# Open-Source_Control_V3_R0.net
KiCad netlist of a schematic drawn in EAGLE
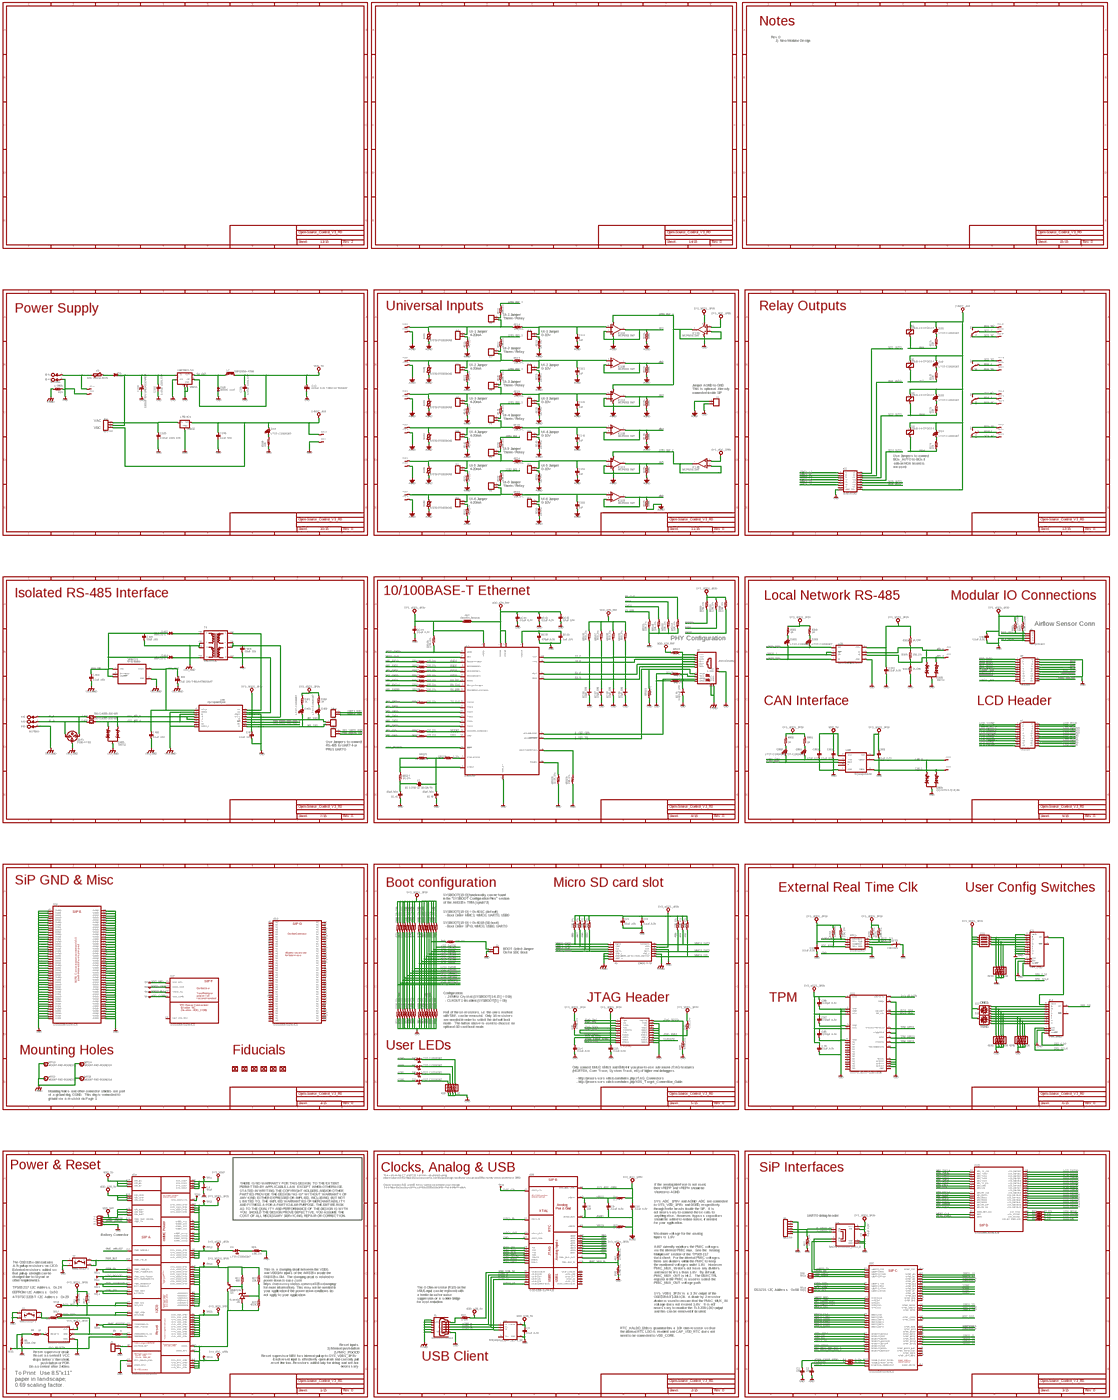
[diagram p0: schematic, sheet 1, overview]
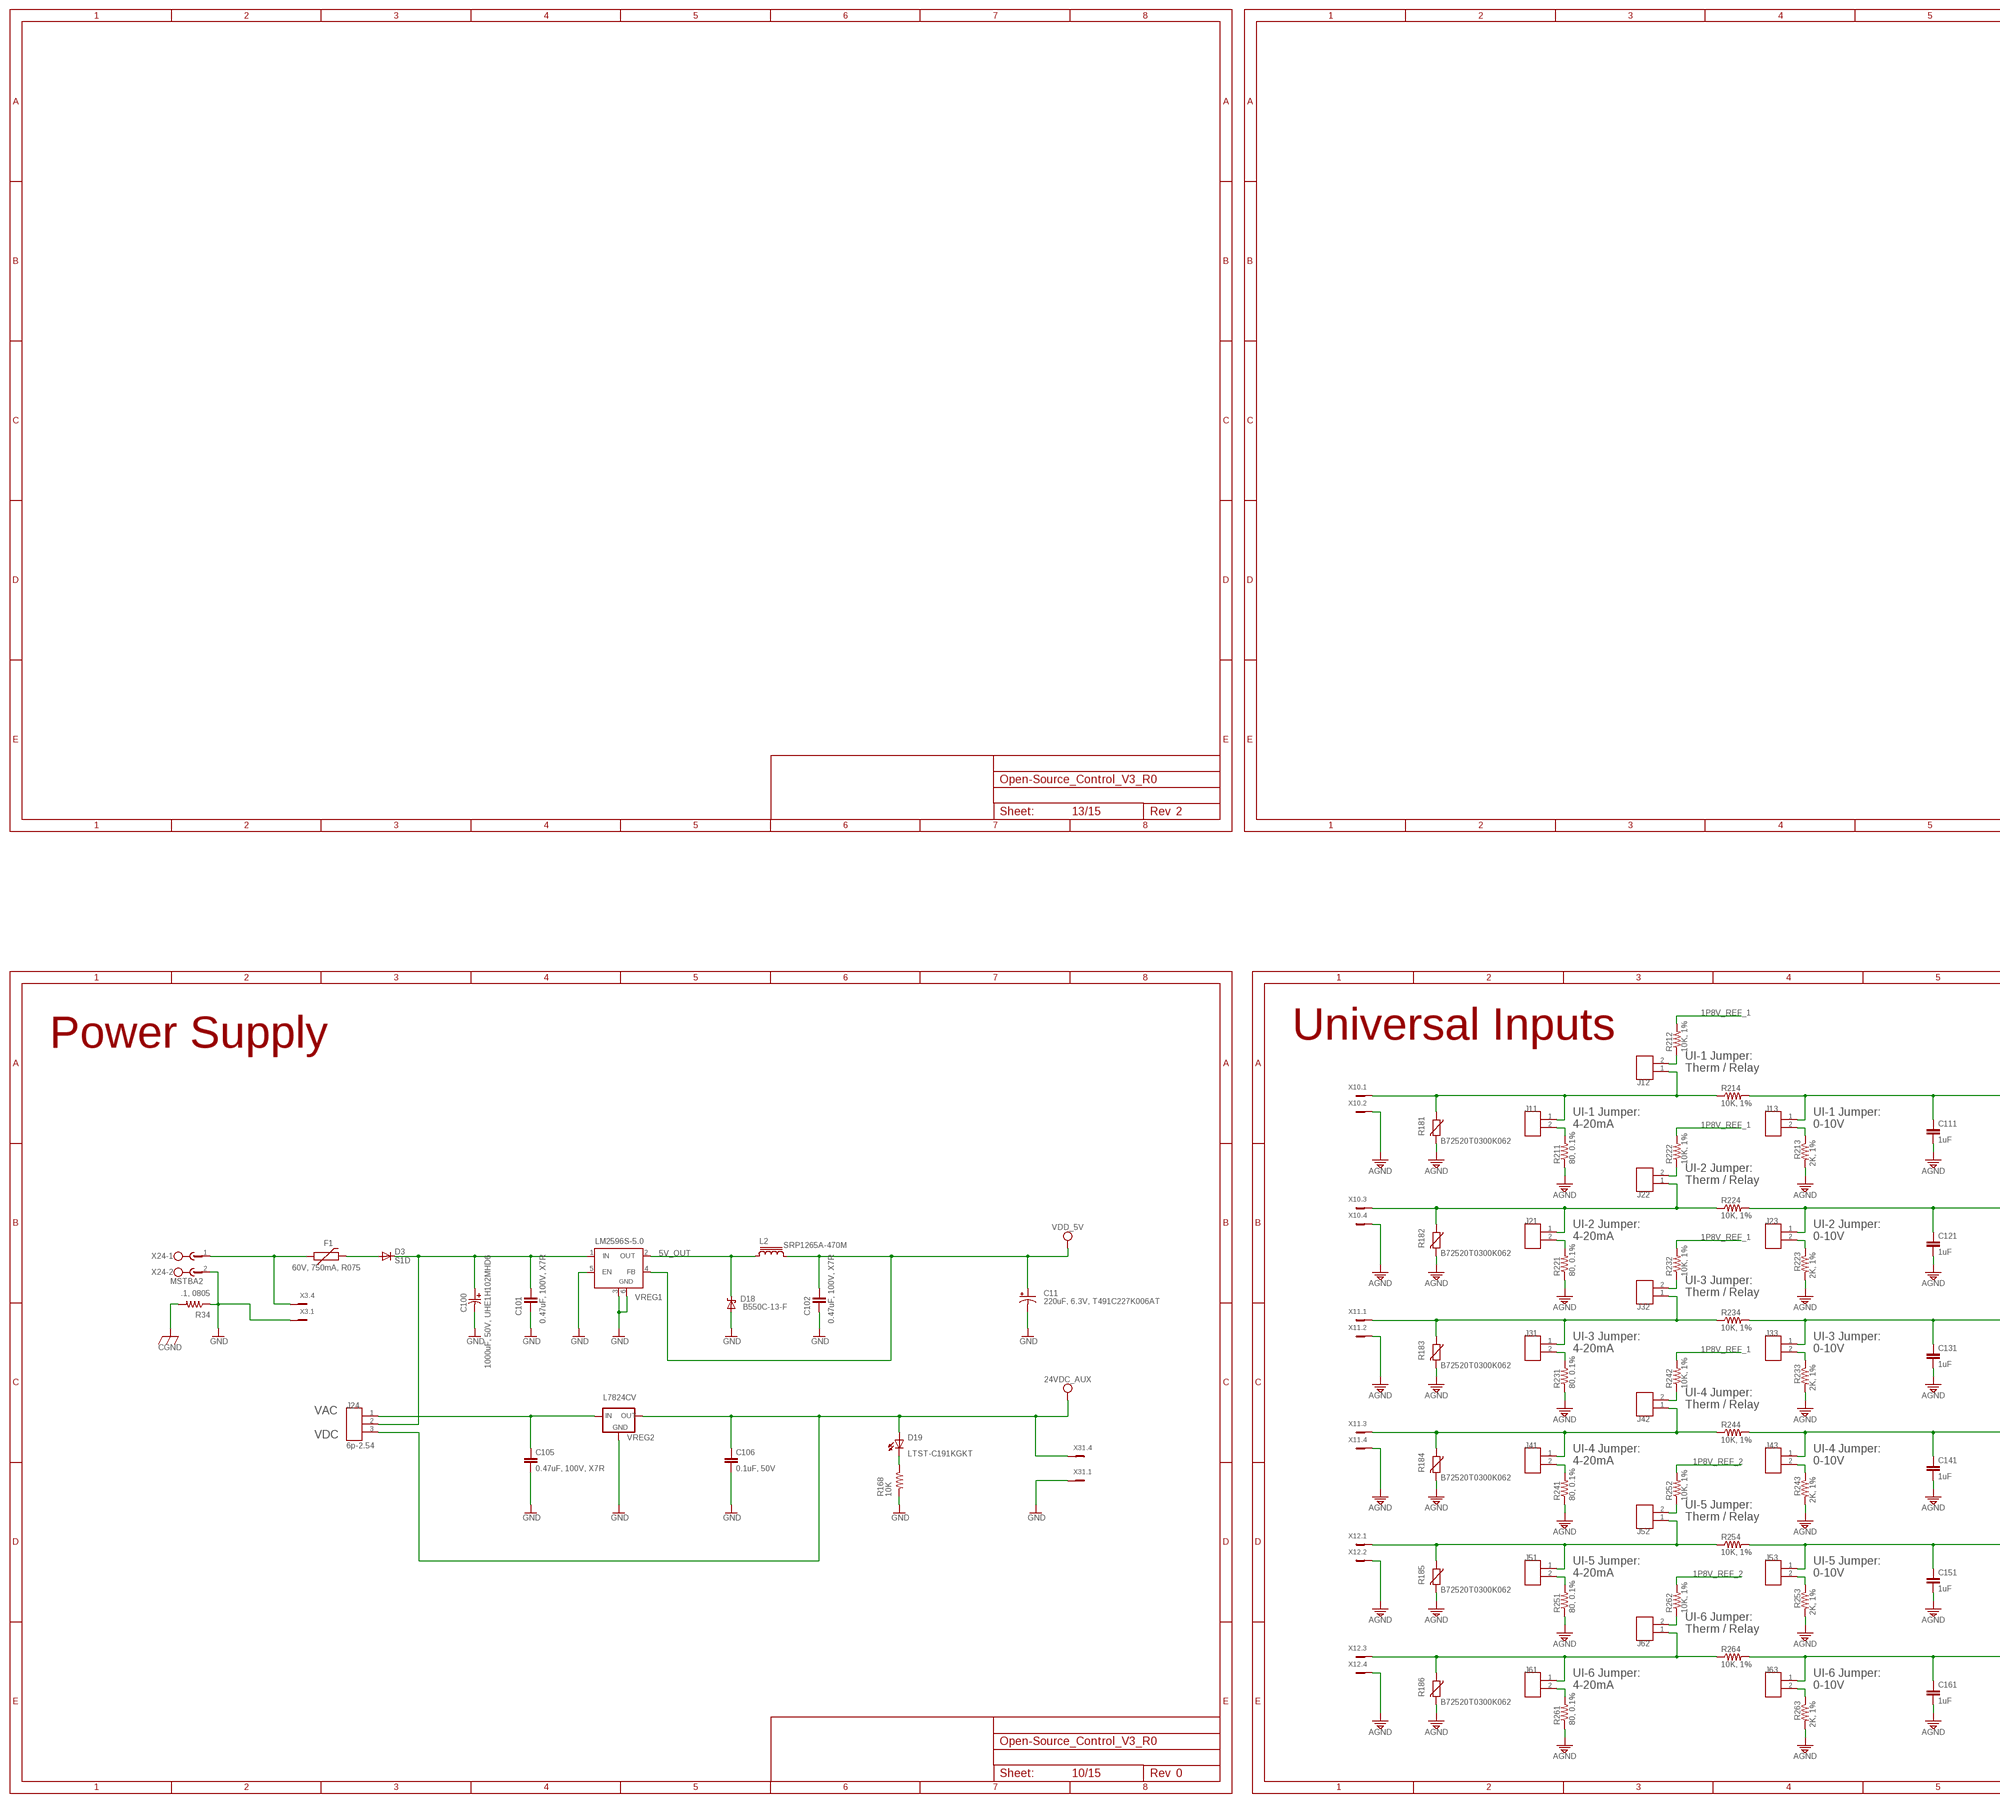
[diagram p1: schematic, sheet 1, part 1 of 6]
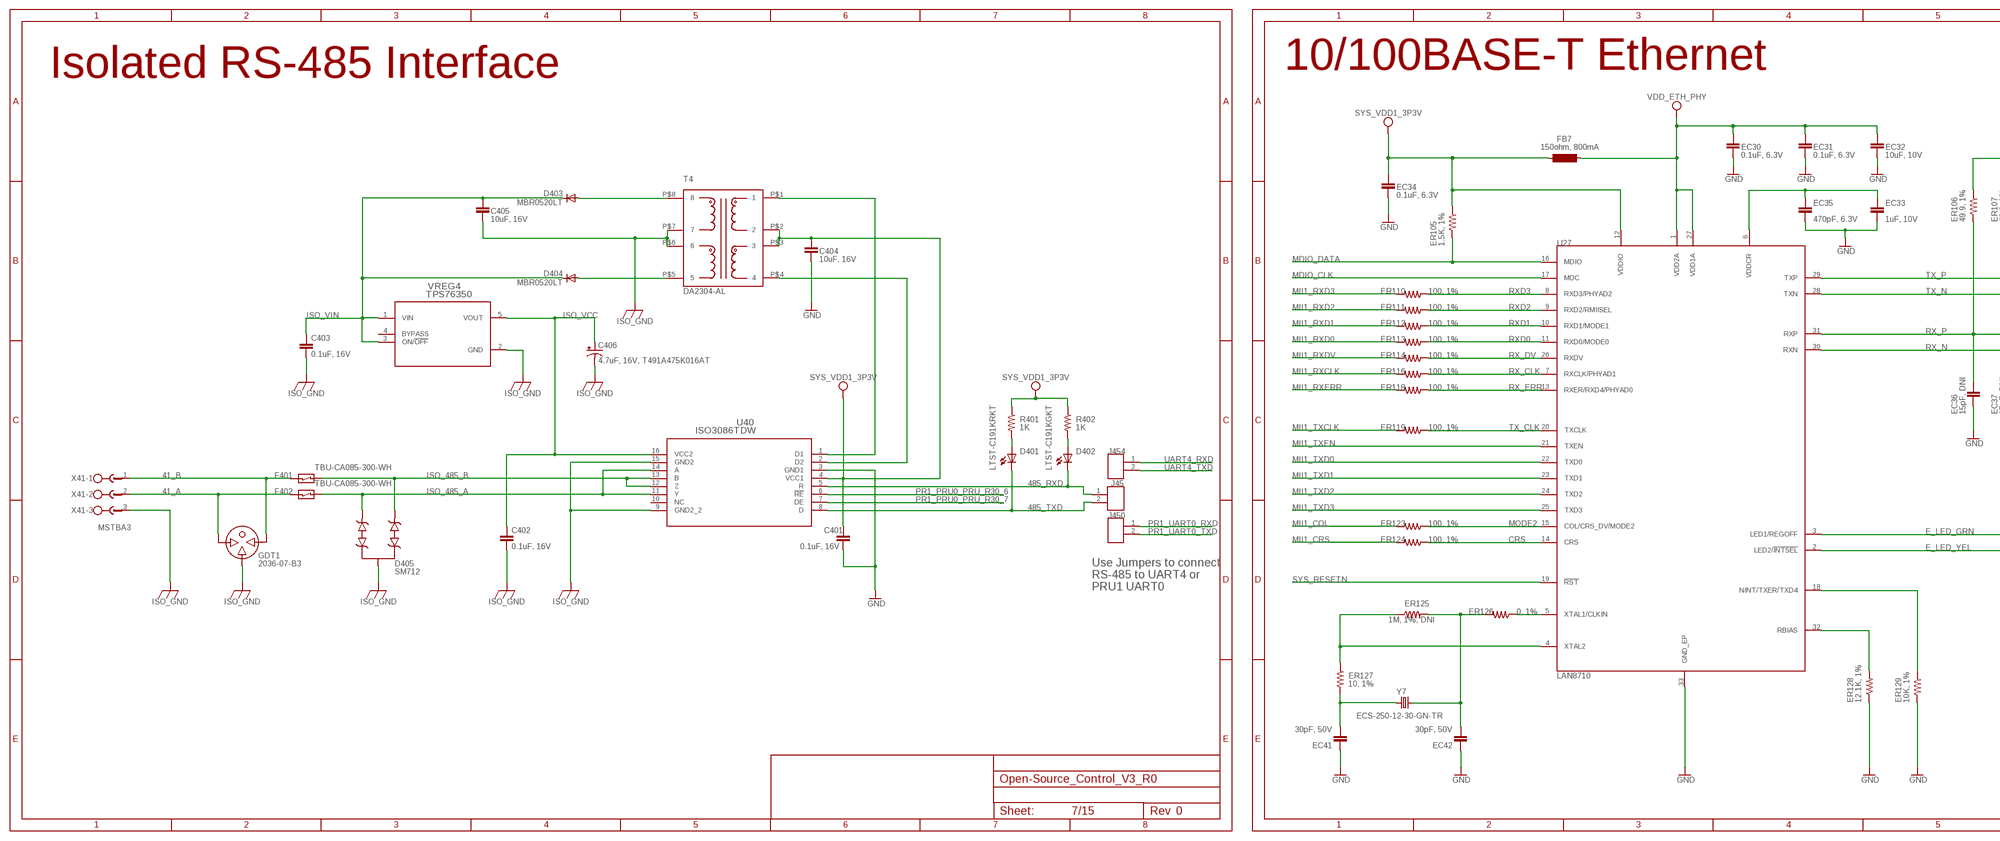
[diagram p2: schematic, sheet 1, part 2 of 6]
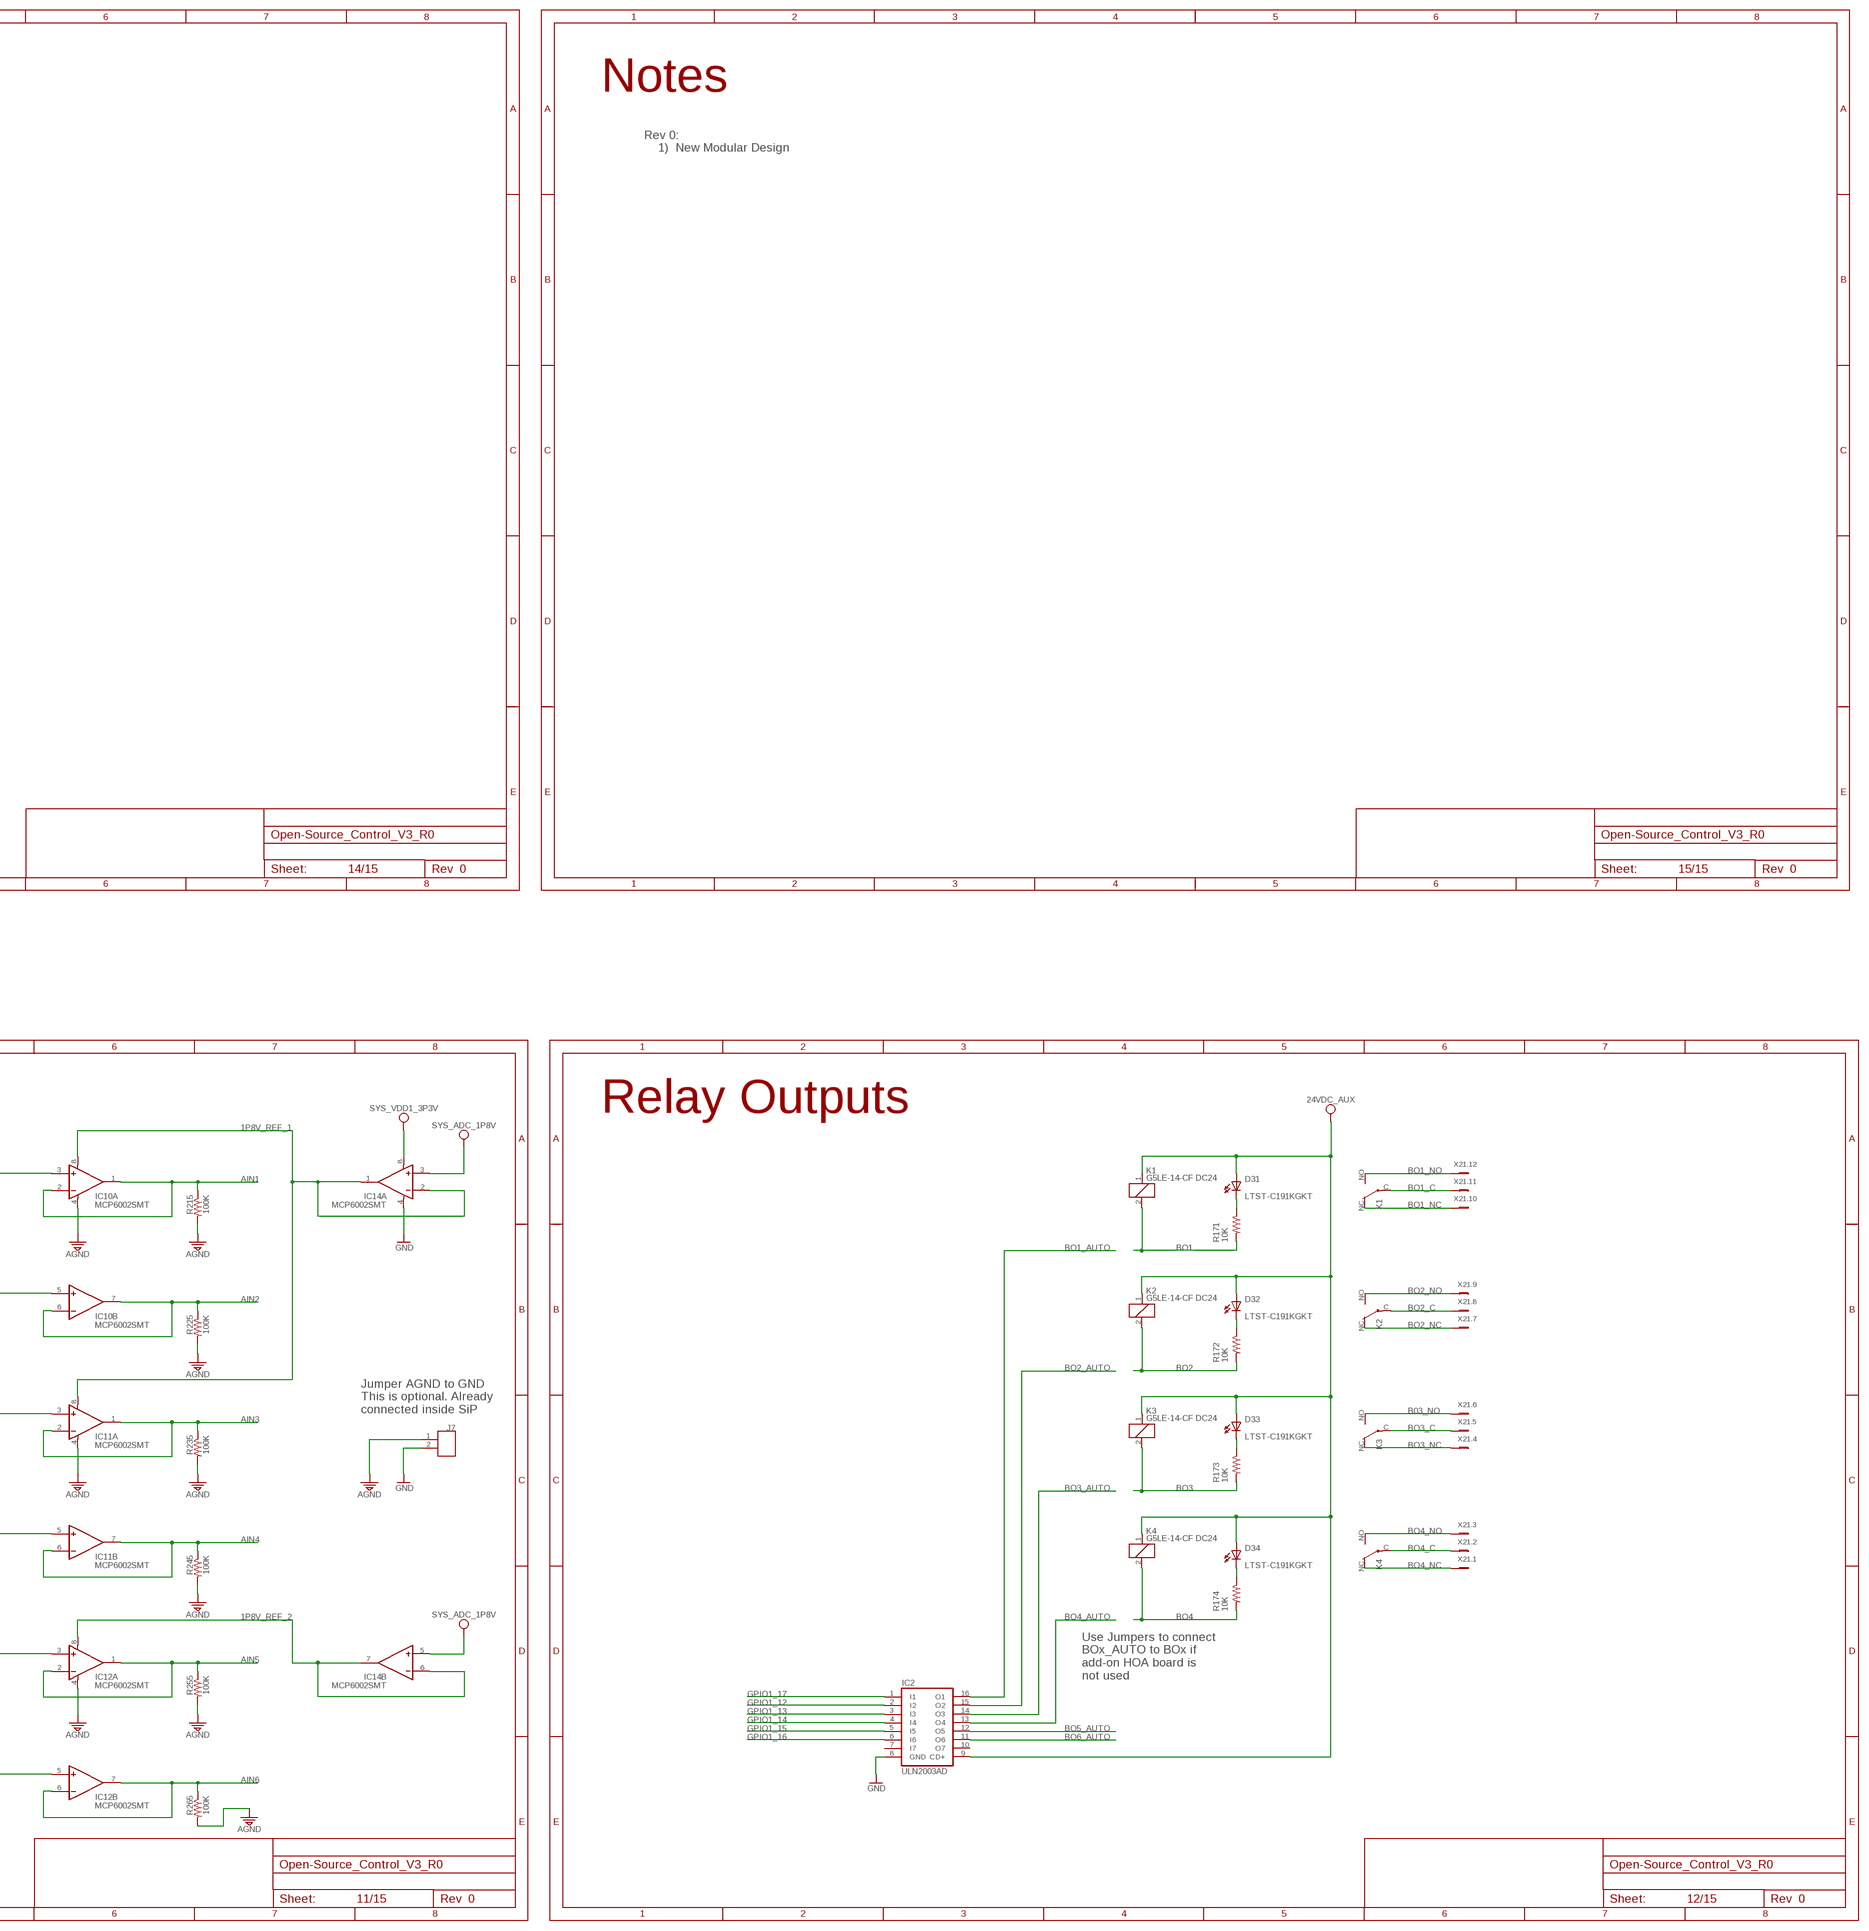
[diagram p3: schematic, sheet 1, part 3 of 6]
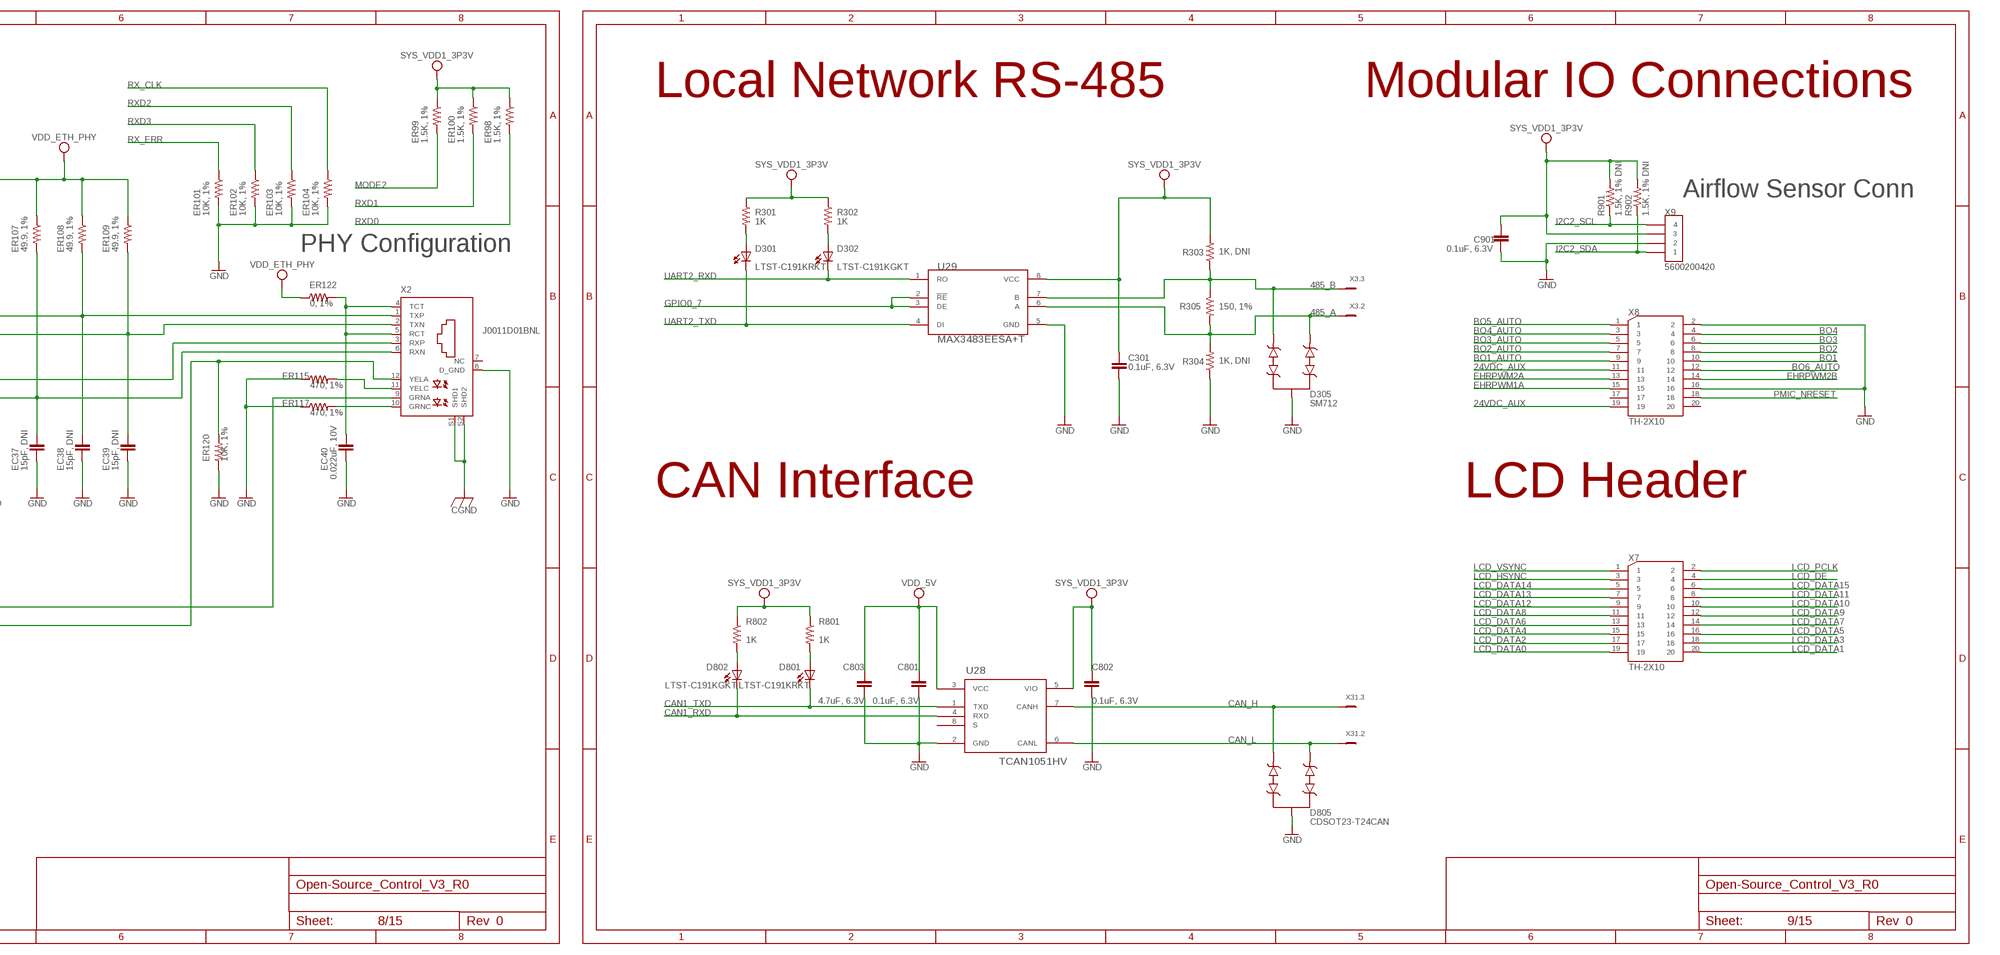
[diagram p4: schematic, sheet 1, part 4 of 6]
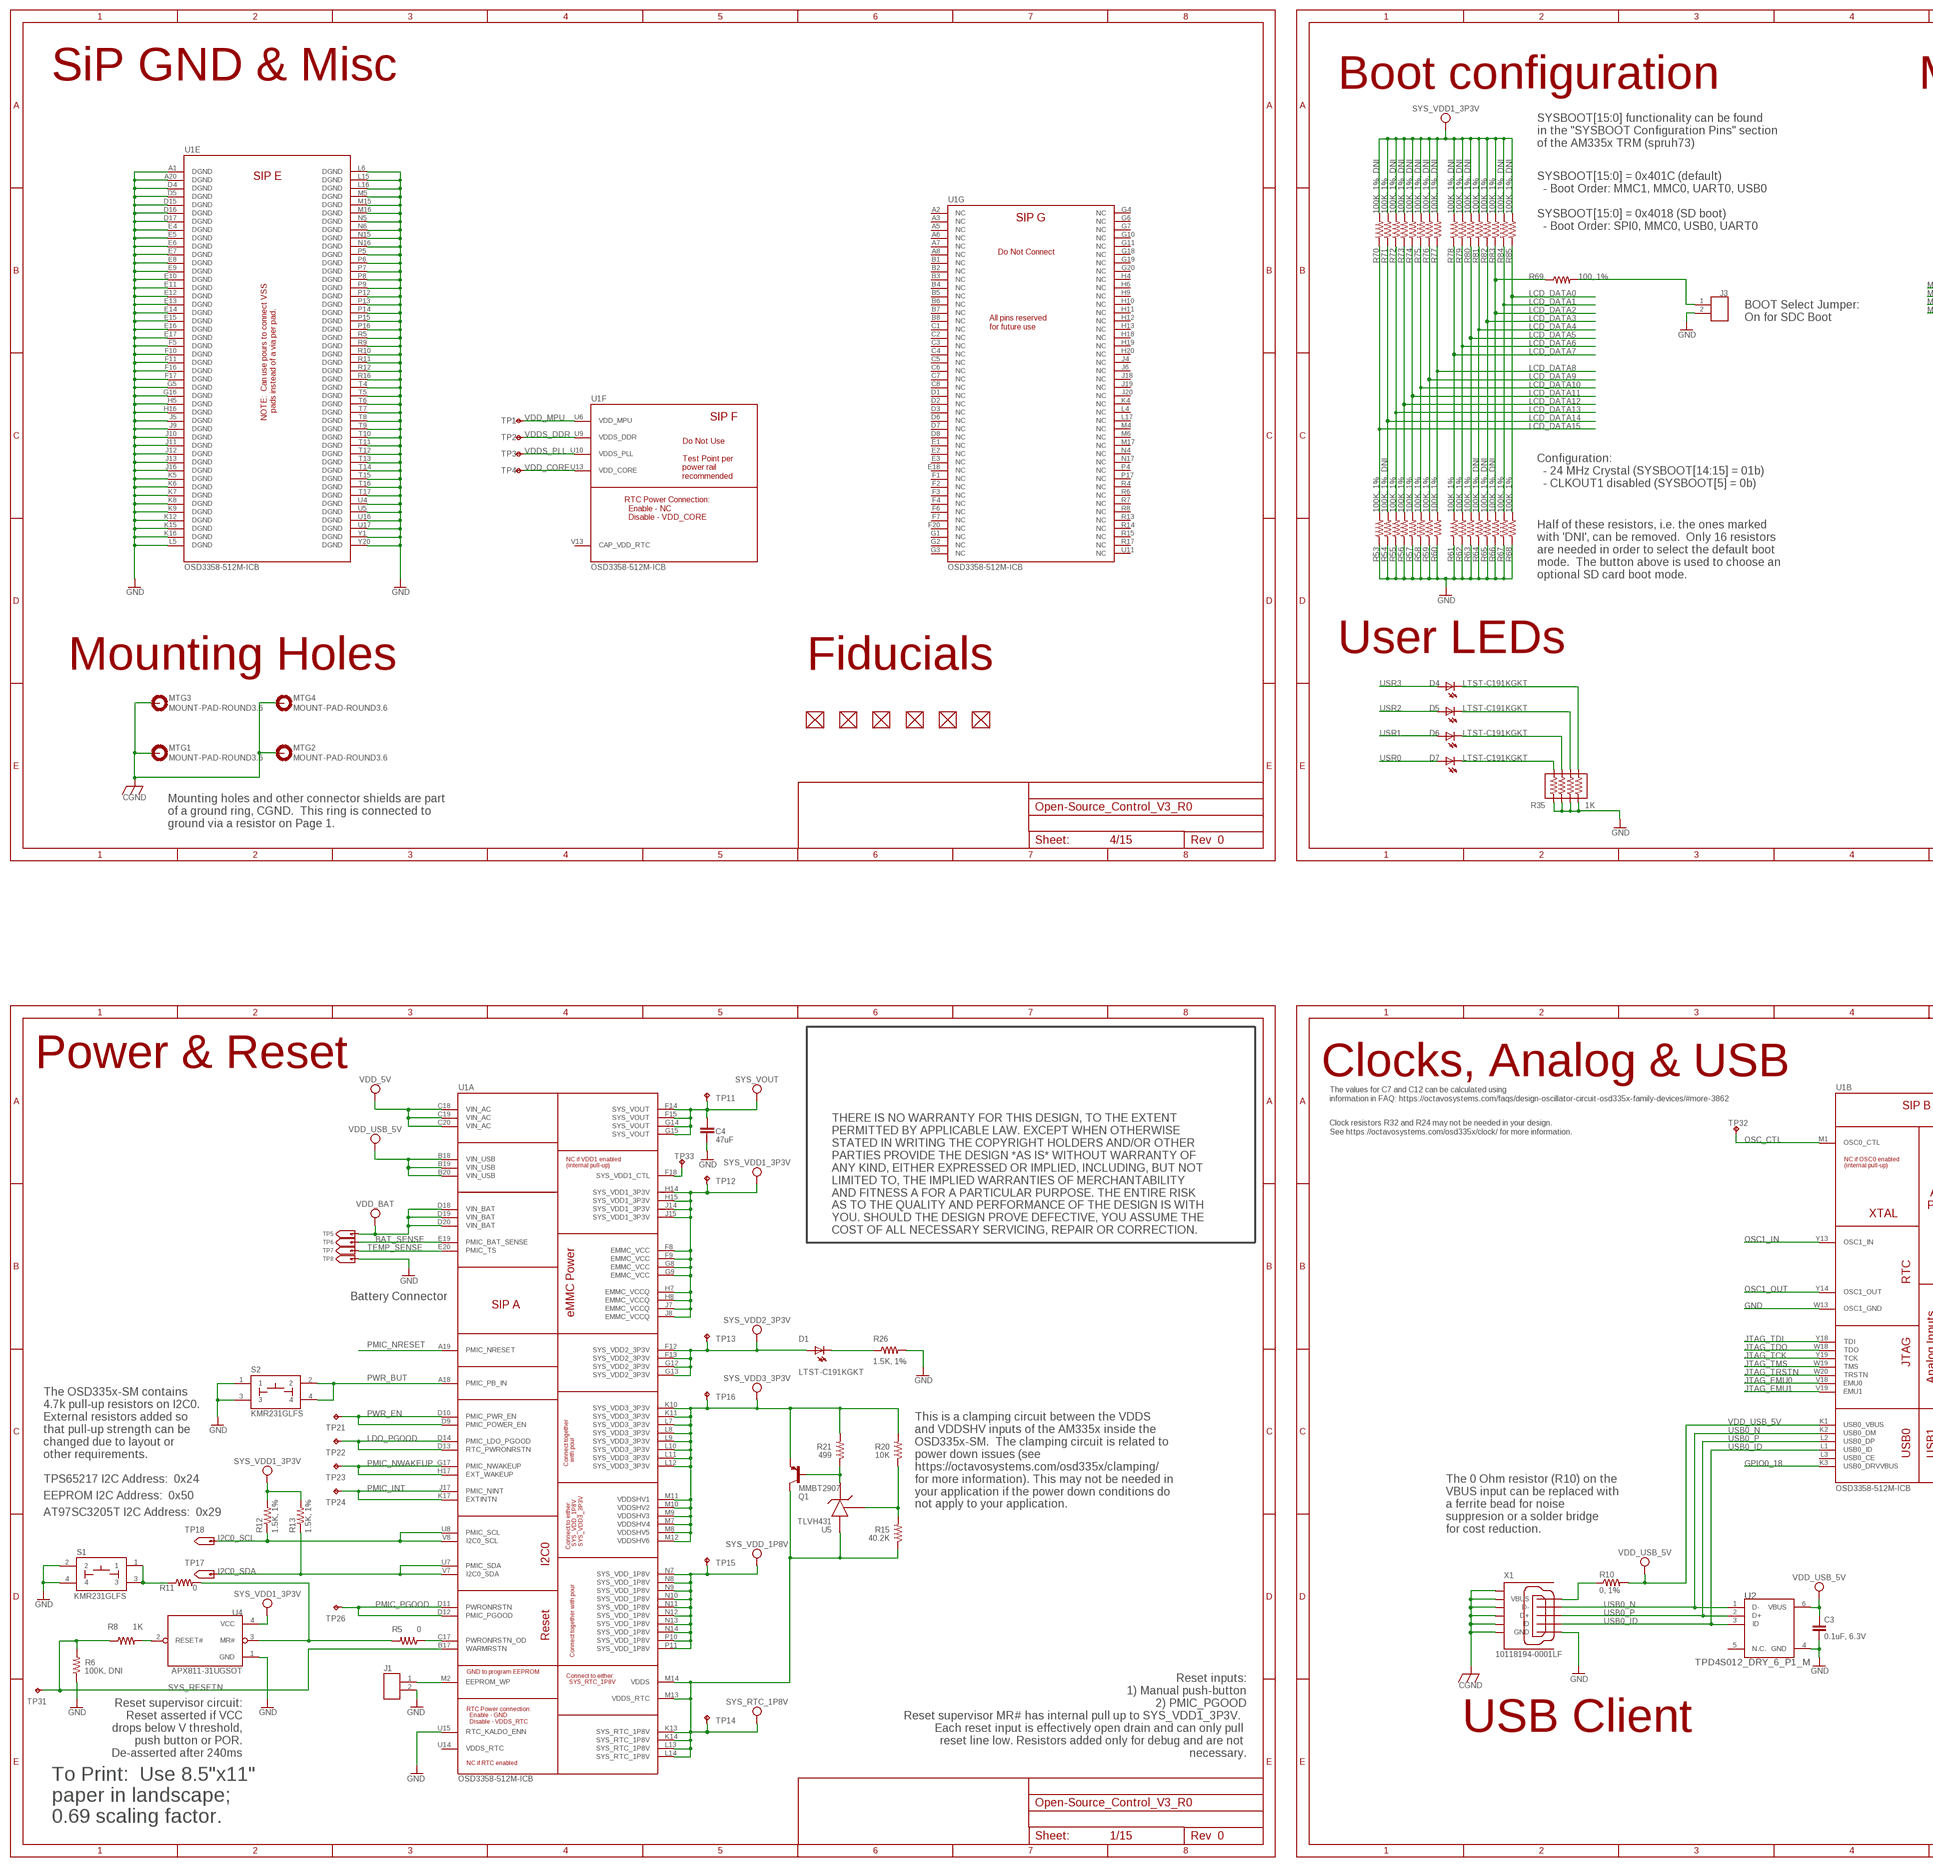
[diagram p5: schematic, sheet 1, part 5 of 6]
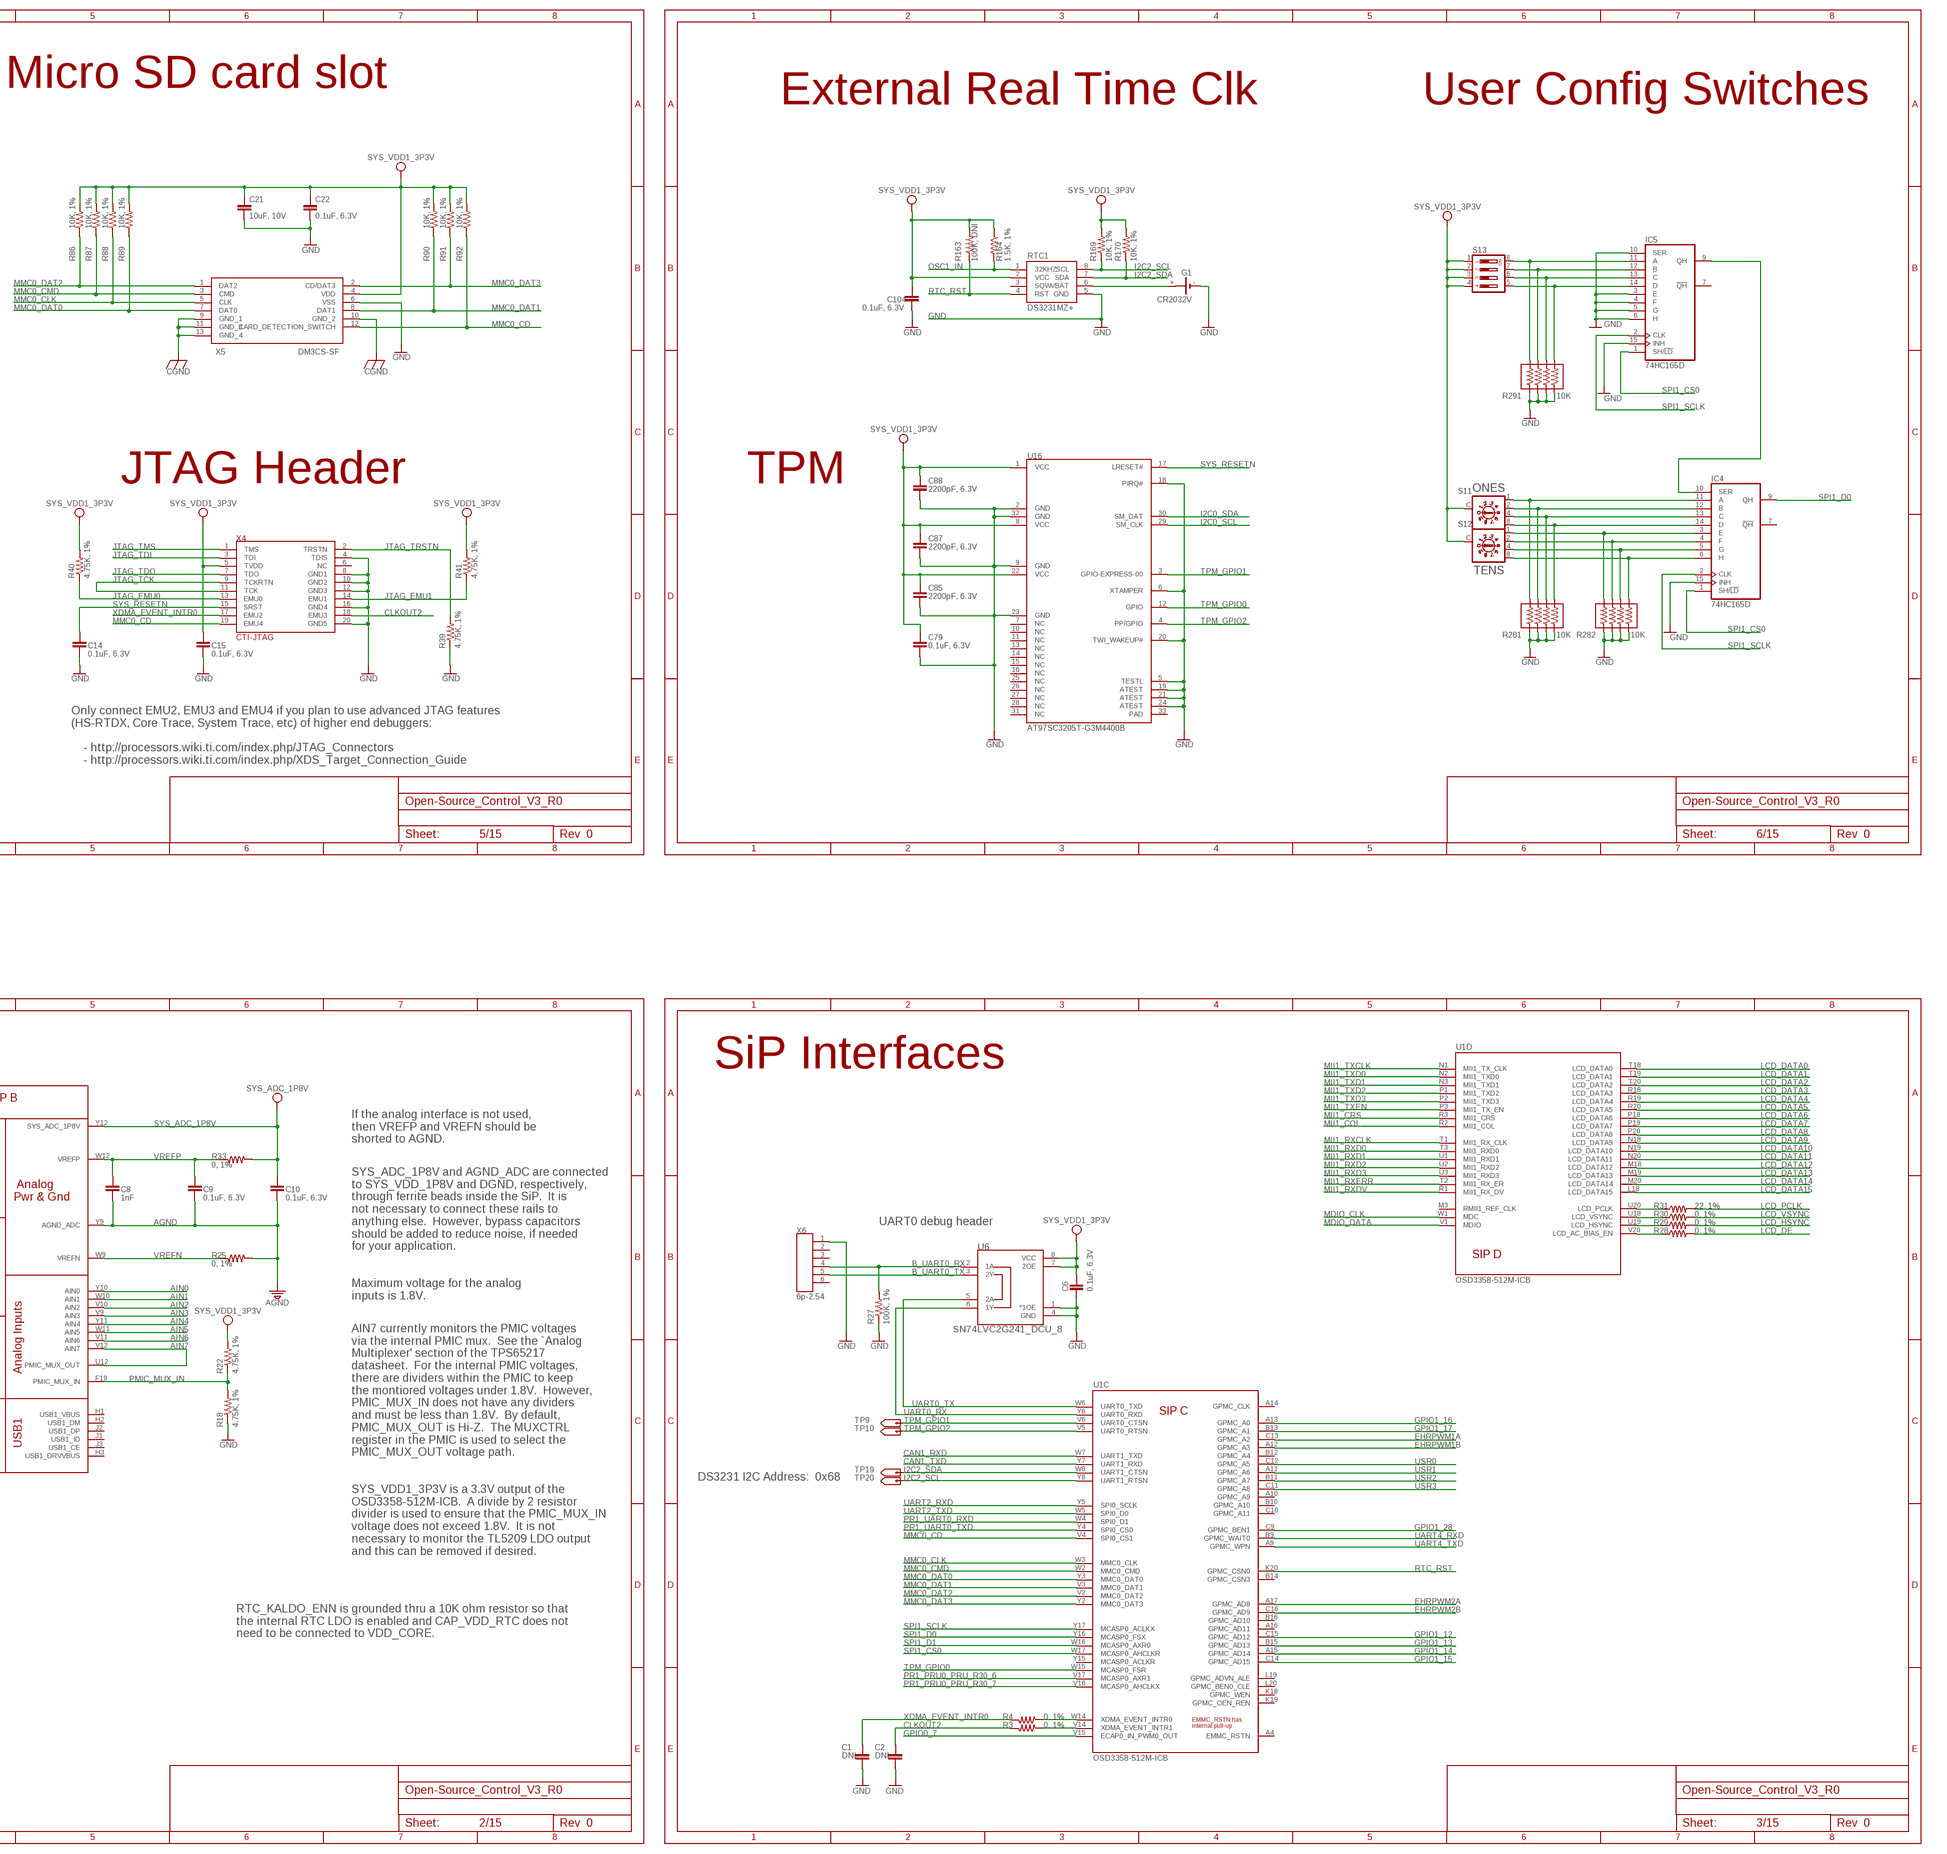
[diagram p6: schematic, sheet 1, part 6 of 6]

(export (version "E")
  (design (tool "Eeschema 10.0.6"))
  (components
    (comp (ref "C1")
      (value "DNI")
      (footprint "eagle-import:C0603")
      (libsource (lib "eagle-import") (part "CC0603"))
    )
    (comp (ref "C2")
      (value "DNI")
      (footprint "eagle-import:C0603")
      (libsource (lib "eagle-import") (part "CC0603"))
    )
    (comp (ref "C3")
      (value "0.1uF, 6.3V")
      (footprint "eagle-import:C0402")
      (libsource (lib "eagle-import") (part "CC0402"))
    )
    (comp (ref "C4")
      (value "47uF")
      (footprint "eagle-import:C0805")
      (libsource (lib "eagle-import") (part "CC0805"))
    )
    (comp (ref "C6")
      (value "0.1uF, 6.3V")
      (footprint "eagle-import:C0402")
      (libsource (lib "eagle-import") (part "CC0402"))
    )
    (comp (ref "C8")
      (value "1nF")
      (footprint "eagle-import:C0402")
      (libsource (lib "eagle-import") (part "CC0402"))
    )
    (comp (ref "C9")
      (value "0.1uF, 6.3V")
      (footprint "eagle-import:C0402")
      (libsource (lib "eagle-import") (part "CC0402"))
    )
    (comp (ref "C10")
      (value "0.1uF, 6.3V")
      (footprint "eagle-import:C0402")
      (libsource (lib "eagle-import") (part "CC0402"))
    )
    (comp (ref "C11")
      (value "220uF, 6.3V, T491C227K006AT")
      (footprint "eagle-import:C_6032-28R")
      (libsource (lib "eagle-import") (part "CPOL-USC/6032-28R"))
    )
    (comp (ref "C14")
      (value "0.1uF, 6.3V")
      (footprint "eagle-import:C0402")
      (libsource (lib "eagle-import") (part "CC0402"))
    )
    (comp (ref "C15")
      (value "0.1uF, 6.3V")
      (footprint "eagle-import:C0402")
      (libsource (lib "eagle-import") (part "CC0402"))
    )
    (comp (ref "C21")
      (value "10uF, 10V")
      (footprint "eagle-import:C0805")
      (libsource (lib "eagle-import") (part "CC0805"))
    )
    (comp (ref "C22")
      (value "0.1uF, 6.3V")
      (footprint "eagle-import:C0402")
      (libsource (lib "eagle-import") (part "CC0402"))
    )
    (comp (ref "C79")
      (value "0.1uF, 6.3V")
      (footprint "eagle-import:C0402")
      (libsource (lib "eagle-import") (part "CC0402"))
    )
    (comp (ref "C85")
      (value "2200pF, 6.3V")
      (footprint "eagle-import:C0402")
      (libsource (lib "eagle-import") (part "CC0402"))
    )
    (comp (ref "C87")
      (value "2200pF, 6.3V")
      (footprint "eagle-import:C0402")
      (libsource (lib "eagle-import") (part "CC0402"))
    )
    (comp (ref "C88")
      (value "2200pF, 6.3V")
      (footprint "eagle-import:C0402")
      (libsource (lib "eagle-import") (part "CC0402"))
    )
    (comp (ref "C100")
      (value "1000uF, 50V, UHE1H102MHD6")
      (footprint "eagle-import:PCAP_16X25-THRU-ELECT")
      (fields (field (name "MANUFACTURER_PART_NUMBER") "UHE1H102MHD6"))
      (libsource (lib "eagle-import") (part "UHE1H102MHD6"))
    )
    (comp (ref "C101")
      (value "0.47uF, 100V, X7R")
      (footprint "eagle-import:1206")
      (libsource (lib "eagle-import") (part "4.7UF-1206-16V-(+80/-20%)"))
    )
    (comp (ref "C102")
      (value "0.47uF, 100V, X7R")
      (footprint "eagle-import:1206")
      (libsource (lib "eagle-import") (part "4.7UF-1206-16V-(+80/-20%)"))
    )
    (comp (ref "C104")
      (value "0.1uF, 6.3V")
      (footprint "eagle-import:C0402")
      (libsource (lib "eagle-import") (part "CC0402"))
    )
    (comp (ref "C105")
      (value "0.47uF, 100V, X7R")
      (footprint "eagle-import:1206")
      (libsource (lib "eagle-import") (part "4.7UF-1206-16V-(+80/-20%)"))
    )
    (comp (ref "C106")
      (value "0.1uF, 50V")
      (footprint "eagle-import:1206")
      (libsource (lib "eagle-import") (part "4.7UF-1206-16V-(+80/-20%)"))
    )
    (comp (ref "C111")
      (value "1uF")
      (footprint "eagle-import:C0805")
      (libsource (lib "eagle-import") (part "CC0805"))
    )
    (comp (ref "C121")
      (value "1uF")
      (footprint "eagle-import:C0805")
      (libsource (lib "eagle-import") (part "CC0805"))
    )
    (comp (ref "C131")
      (value "1uF")
      (footprint "eagle-import:C0805")
      (libsource (lib "eagle-import") (part "CC0805"))
    )
    (comp (ref "C141")
      (value "1uF")
      (footprint "eagle-import:C0805")
      (libsource (lib "eagle-import") (part "CC0805"))
    )
    (comp (ref "C151")
      (value "1uF")
      (footprint "eagle-import:C0805")
      (libsource (lib "eagle-import") (part "CC0805"))
    )
    (comp (ref "C161")
      (value "1uF")
      (footprint "eagle-import:C0805")
      (libsource (lib "eagle-import") (part "CC0805"))
    )
    (comp (ref "C301")
      (value "0.1uF, 6.3V")
      (footprint "eagle-import:C0402")
      (libsource (lib "eagle-import") (part "CC0402"))
    )
    (comp (ref "C401")
      (value "0.1uF, 16V")
      (footprint "eagle-import:C0402")
      (libsource (lib "eagle-import") (part "CC0402"))
    )
    (comp (ref "C402")
      (value "0.1uF, 16V")
      (footprint "eagle-import:C0402")
      (libsource (lib "eagle-import") (part "CC0402"))
    )
    (comp (ref "C403")
      (value "0.1uF, 16V")
      (footprint "eagle-import:C0402")
      (libsource (lib "eagle-import") (part "CC0402"))
    )
    (comp (ref "C404")
      (value "10uF, 16V")
      (footprint "eagle-import:C0805")
      (libsource (lib "eagle-import") (part "CC0805"))
    )
    (comp (ref "C405")
      (value "10uF, 16V")
      (footprint "eagle-import:C0805")
      (libsource (lib "eagle-import") (part "CC0805"))
    )
    (comp (ref "C406")
      (value "4.7uF, 16V, T491A475K016AT")
      (footprint "eagle-import:A_3216-18R")
      (libsource (lib "eagle-import") (part "CPOL-USA/3216-18R"))
    )
    (comp (ref "C801")
      (value "0.1uF, 6.3V")
      (footprint "eagle-import:C0402")
      (libsource (lib "eagle-import") (part "CC0402"))
    )
    (comp (ref "C802")
      (value "0.1uF, 6.3V")
      (footprint "eagle-import:C0402")
      (libsource (lib "eagle-import") (part "CC0402"))
    )
    (comp (ref "C803")
      (value "4.7uF, 6.3V")
      (footprint "eagle-import:C0402")
      (libsource (lib "eagle-import") (part "CC0402"))
    )
    (comp (ref "C901")
      (value "0.1uF, 6.3V")
      (footprint "eagle-import:C0402")
      (libsource (lib "eagle-import") (part "CC0402"))
    )
    (comp (ref "D1")
      (value "LTST-C191KGKT")
      (footprint "eagle-import:EIA-STD")
      (libsource (lib "eagle-import") (part "Open-Source_Control_V2_R2_LTST-C191KGKTLED_EIA-STD"))
    )
    (comp (ref "D3")
      (value "S1D")
      (footprint "eagle-import:SMA")
      (libsource (lib "eagle-import") (part "S1M"))
    )
    (comp (ref "D4")
      (value "LTST-C191KGKT")
      (footprint "eagle-import:EIA-STD")
      (libsource (lib "eagle-import") (part "LTST-C191KGKTLED_EIA-STD"))
    )
    (comp (ref "D5")
      (value "LTST-C191KGKT")
      (footprint "eagle-import:EIA-STD")
      (libsource (lib "eagle-import") (part "LTST-C191KGKTLED_EIA-STD"))
    )
    (comp (ref "D6")
      (value "LTST-C191KGKT")
      (footprint "eagle-import:EIA-STD")
      (libsource (lib "eagle-import") (part "LTST-C191KGKTLED_EIA-STD"))
    )
    (comp (ref "D7")
      (value "LTST-C191KGKT")
      (footprint "eagle-import:EIA-STD")
      (libsource (lib "eagle-import") (part "LTST-C191KGKTLED_EIA-STD"))
    )
    (comp (ref "D18")
      (value "B550C-13-F")
      (footprint "eagle-import:SMC")
      (libsource (lib "eagle-import") (part "B520C-13-F"))
    )
    (comp (ref "D19")
      (value "LTST-C191KGKT")
      (footprint "eagle-import:EIA-STD")
      (libsource (lib "eagle-import") (part "Open-Source_Control_V2_R2_LTST-C191KGKTLED_EIA-STD"))
    )
    (comp (ref "D31")
      (value "LTST-C191KGKT")
      (footprint "eagle-import:EIA-STD")
      (libsource (lib "eagle-import") (part "LTST-C191KGKTLED_EIA-STD"))
    )
    (comp (ref "D32")
      (value "LTST-C191KGKT")
      (footprint "eagle-import:EIA-STD")
      (libsource (lib "eagle-import") (part "LTST-C191KGKTLED_EIA-STD"))
    )
    (comp (ref "D33")
      (value "LTST-C191KGKT")
      (footprint "eagle-import:EIA-STD")
      (libsource (lib "eagle-import") (part "LTST-C191KGKTLED_EIA-STD"))
    )
    (comp (ref "D34")
      (value "LTST-C191KGKT")
      (footprint "eagle-import:EIA-STD")
      (libsource (lib "eagle-import") (part "LTST-C191KGKTLED_EIA-STD"))
    )
    (comp (ref "D301")
      (value "LTST-C191KRKT")
      (footprint "eagle-import:EIA-STD")
      (libsource (lib "eagle-import") (part "LTST-C191KGKTLED_EIA-STD"))
    )
    (comp (ref "D302")
      (value "LTST-C191KGKT")
      (footprint "eagle-import:EIA-STD")
      (libsource (lib "eagle-import") (part "LTST-C191KRKTLED_EIA-STD"))
    )
    (comp (ref "D305")
      (value "SM712")
      (footprint "eagle-import:SOT23-3")
      (libsource (lib "eagle-import") (part "SM712"))
    )
    (comp (ref "D401")
      (value "LTST-C191KRKT")
      (footprint "eagle-import:EIA-STD")
      (libsource (lib "eagle-import") (part "LTST-C191KRKTLED_EIA-STD"))
    )
    (comp (ref "D402")
      (value "LTST-C191KGKT")
      (footprint "eagle-import:EIA-STD")
      (libsource (lib "eagle-import") (part "LTST-C191KGKTLED_EIA-STD"))
    )
    (comp (ref "D403")
      (value "MBR0520LT")
      (footprint "eagle-import:SOD123")
      (libsource (lib "eagle-import") (part "MBR0520LT"))
    )
    (comp (ref "D404")
      (value "MBR0520LT")
      (footprint "eagle-import:SOD123")
      (libsource (lib "eagle-import") (part "MBR0520LT"))
    )
    (comp (ref "D405")
      (value "SM712")
      (footprint "eagle-import:SOT23-3")
      (libsource (lib "eagle-import") (part "SM712"))
    )
    (comp (ref "D801")
      (value "LTST-C191KRKT")
      (footprint "eagle-import:EIA-STD")
      (libsource (lib "eagle-import") (part "LTST-C191KRKTLED_EIA-STD"))
    )
    (comp (ref "D802")
      (value "LTST-C191KGKT")
      (footprint "eagle-import:EIA-STD")
      (libsource (lib "eagle-import") (part "LTST-C191KGKTLED_EIA-STD"))
    )
    (comp (ref "D805")
      (value "CDSOT23-T24CAN")
      (footprint "eagle-import:SOT23-3")
      (libsource (lib "eagle-import") (part "CDSOT23-T24CAN"))
    )
    (comp (ref "EC30")
      (value "0.1uF, 6.3V")
      (footprint "eagle-import:C0402")
      (libsource (lib "eagle-import") (part "CC0402"))
    )
    (comp (ref "EC31")
      (value "0.1uF, 6.3V")
      (footprint "eagle-import:C0402")
      (libsource (lib "eagle-import") (part "CC0402"))
    )
    (comp (ref "EC32")
      (value "10uF, 10V")
      (footprint "eagle-import:C0805")
      (libsource (lib "eagle-import") (part "CC0805"))
    )
    (comp (ref "EC33")
      (value "1uF, 10V")
      (footprint "eagle-import:C0402")
      (libsource (lib "eagle-import") (part "CC0402"))
    )
    (comp (ref "EC34")
      (value "0.1uF, 6.3V")
      (footprint "eagle-import:C0402")
      (libsource (lib "eagle-import") (part "CC0402"))
    )
    (comp (ref "EC35")
      (value "470pF, 6.3V")
      (footprint "eagle-import:C0402")
      (libsource (lib "eagle-import") (part "CC0402"))
    )
    (comp (ref "EC36")
      (value "15pF, DNI")
      (footprint "eagle-import:C0402")
      (libsource (lib "eagle-import") (part "CC0402"))
    )
    (comp (ref "EC37")
      (value "15pF, DNI")
      (footprint "eagle-import:C0402")
      (libsource (lib "eagle-import") (part "CC0402"))
    )
    (comp (ref "EC38")
      (value "15pF, DNI")
      (footprint "eagle-import:C0402")
      (libsource (lib "eagle-import") (part "CC0402"))
    )
    (comp (ref "EC39")
      (value "15pF, DNI")
      (footprint "eagle-import:C0402")
      (libsource (lib "eagle-import") (part "CC0402"))
    )
    (comp (ref "EC40")
      (value "0.022uF, 10V")
      (footprint "eagle-import:C0402")
      (libsource (lib "eagle-import") (part "CC0402"))
    )
    (comp (ref "EC41")
      (value "30pF, 50V")
      (footprint "eagle-import:C0402")
      (libsource (lib "eagle-import") (part "CC0402"))
    )
    (comp (ref "EC42")
      (value "30pF, 50V")
      (footprint "eagle-import:C0402")
      (libsource (lib "eagle-import") (part "CC0402"))
    )
    (comp (ref "ER98")
      (value "1.5K, 1%")
      (footprint "eagle-import:R0402")
      (libsource (lib "eagle-import") (part "OSD3358-SM-RED Platform_R-US_R0402"))
    )
    (comp (ref "ER99")
      (value "1.5K, 1%")
      (footprint "eagle-import:R0402")
      (libsource (lib "eagle-import") (part "OSD3358-SM-RED Platform_R-US_R0402"))
    )
    (comp (ref "ER100")
      (value "1.5K, 1%")
      (footprint "eagle-import:R0402")
      (libsource (lib "eagle-import") (part "OSD3358-SM-RED Platform_R-US_R0402"))
    )
    (comp (ref "ER101")
      (value "10K, 1%")
      (footprint "eagle-import:R0402")
      (libsource (lib "eagle-import") (part "OSD3358-SM-RED Platform_R-US_R0402"))
    )
    (comp (ref "ER102")
      (value "10K, 1%")
      (footprint "eagle-import:R0402")
      (libsource (lib "eagle-import") (part "OSD3358-SM-RED Platform_R-US_R0402"))
    )
    (comp (ref "ER103")
      (value "10K, 1%")
      (footprint "eagle-import:R0402")
      (libsource (lib "eagle-import") (part "OSD3358-SM-RED Platform_R-US_R0402"))
    )
    (comp (ref "ER104")
      (value "10K, 1%")
      (footprint "eagle-import:R0402")
      (libsource (lib "eagle-import") (part "OSD3358-SM-RED Platform_R-US_R0402"))
    )
    (comp (ref "ER105")
      (value "1.5K, 1%")
      (footprint "eagle-import:R0402")
      (libsource (lib "eagle-import") (part "OSD3358-SM-RED Platform_R-US_R0402"))
    )
    (comp (ref "ER106")
      (value "49.9, 1%")
      (footprint "eagle-import:R0402")
      (libsource (lib "eagle-import") (part "OSD3358-SM-RED Platform_R-US_R0402"))
    )
    (comp (ref "ER107")
      (value "49.9, 1%")
      (footprint "eagle-import:R0402")
      (libsource (lib "eagle-import") (part "OSD3358-SM-RED Platform_R-US_R0402"))
    )
    (comp (ref "ER108")
      (value "49.9, 1%")
      (footprint "eagle-import:R0402")
      (libsource (lib "eagle-import") (part "OSD3358-SM-RED Platform_R-US_R0402"))
    )
    (comp (ref "ER109")
      (value "49.9, 1%")
      (footprint "eagle-import:R0402")
      (libsource (lib "eagle-import") (part "OSD3358-SM-RED Platform_R-US_R0402"))
    )
    (comp (ref "ER110")
      (value "100, 1%")
      (footprint "eagle-import:R0402")
      (libsource (lib "eagle-import") (part "OSD3358-SM-RED Platform_R-US_R0402"))
    )
    (comp (ref "ER111")
      (value "100, 1%")
      (footprint "eagle-import:R0402")
      (libsource (lib "eagle-import") (part "OSD3358-SM-RED Platform_R-US_R0402"))
    )
    (comp (ref "ER112")
      (value "100, 1%")
      (footprint "eagle-import:R0402")
      (libsource (lib "eagle-import") (part "OSD3358-SM-RED Platform_R-US_R0402"))
    )
    (comp (ref "ER113")
      (value "100, 1%")
      (footprint "eagle-import:R0402")
      (libsource (lib "eagle-import") (part "OSD3358-SM-RED Platform_R-US_R0402"))
    )
    (comp (ref "ER114")
      (value "100, 1%")
      (footprint "eagle-import:R0402")
      (libsource (lib "eagle-import") (part "OSD3358-SM-RED Platform_R-US_R0402"))
    )
    (comp (ref "ER115")
      (value "470, 1%")
      (footprint "eagle-import:R0402")
      (libsource (lib "eagle-import") (part "OSD3358-SM-RED Platform_R-US_R0402"))
    )
    (comp (ref "ER116")
      (value "100, 1%")
      (footprint "eagle-import:R0402")
      (libsource (lib "eagle-import") (part "OSD3358-SM-RED Platform_R-US_R0402"))
    )
    (comp (ref "ER117")
      (value "470, 1%")
      (footprint "eagle-import:R0402")
      (libsource (lib "eagle-import") (part "OSD3358-SM-RED Platform_R-US_R0402"))
    )
    (comp (ref "ER118")
      (value "100, 1%")
      (footprint "eagle-import:R0402")
      (libsource (lib "eagle-import") (part "OSD3358-SM-RED Platform_R-US_R0402"))
    )
    (comp (ref "ER119")
      (value "100, 1%")
      (footprint "eagle-import:R0402")
      (libsource (lib "eagle-import") (part "OSD3358-SM-RED Platform_R-US_R0402"))
    )
    (comp (ref "ER120")
      (value "10K, 1%")
      (footprint "eagle-import:R0402")
      (libsource (lib "eagle-import") (part "OSD3358-SM-RED Platform_R-US_R0402"))
    )
    (comp (ref "ER122")
      (value "0, 1%")
      (footprint "eagle-import:R0402")
      (libsource (lib "eagle-import") (part "OSD3358-SM-RED Platform_R-US_R0402"))
    )
    (comp (ref "ER123")
      (value "100, 1%")
      (footprint "eagle-import:R0402")
      (libsource (lib "eagle-import") (part "OSD3358-SM-RED Platform_R-US_R0402"))
    )
    (comp (ref "ER124")
      (value "100, 1%")
      (footprint "eagle-import:R0402")
      (libsource (lib "eagle-import") (part "OSD3358-SM-RED Platform_R-US_R0402"))
    )
    (comp (ref "ER125")
      (value "1M, 1%, DNI")
      (footprint "eagle-import:R0402")
      (libsource (lib "eagle-import") (part "OSD3358-SM-RED Platform_R-US_R0402"))
    )
    (comp (ref "ER126")
      (value "0, 1%")
      (footprint "eagle-import:R0402")
      (libsource (lib "eagle-import") (part "OSD3358-SM-RED Platform_R-US_R0402"))
    )
    (comp (ref "ER127")
      (value "10, 1%")
      (footprint "eagle-import:R0402")
      (libsource (lib "eagle-import") (part "OSD3358-SM-RED Platform_R-US_R0402"))
    )
    (comp (ref "ER128")
      (value "12.1K, 1%")
      (footprint "eagle-import:R0402")
      (libsource (lib "eagle-import") (part "OSD3358-SM-RED Platform_R-US_R0402"))
    )
    (comp (ref "ER129")
      (value "10K, 1%")
      (footprint "eagle-import:R0402")
      (libsource (lib "eagle-import") (part "OSD3358-SM-RED Platform_R-US_R0402"))
    )
    (comp (ref "F1")
      (value "60V, 750mA, R075")
      (footprint "eagle-import:PTH")
      (libsource (lib "eagle-import") (part "PPTC_PTH"))
    )
    (comp (ref "F401")
      (value "TBU-CA085-300-WH")
      (footprint "eagle-import:TBU-CA")
      (libsource (lib "eagle-import") (part "TBU-CA085-300-WH"))
    )
    (comp (ref "F402")
      (value "TBU-CA085-300-WH")
      (footprint "eagle-import:TBU-CA")
      (libsource (lib "eagle-import") (part "TBU-CA085-300-WH"))
    )
    (comp (ref "FB7")
      (value "150ohm, 800mA")
      (footprint "eagle-import:C0805")
      (libsource (lib "eagle-import") (part "BLM21AG151SN1DFB_0805"))
    )
    (comp (ref "FUD1")
      (value "FIDUCIAL")
      (footprint "eagle-import:FIDUCIAL_40MIL")
      (libsource (lib "eagle-import") (part "FIDUCIAL"))
    )
    (comp (ref "FUD2")
      (value "FIDUCIAL")
      (footprint "eagle-import:FIDUCIAL_40MIL")
      (libsource (lib "eagle-import") (part "FIDUCIAL"))
    )
    (comp (ref "FUD3")
      (value "FIDUCIAL")
      (footprint "eagle-import:FIDUCIAL_40MIL")
      (libsource (lib "eagle-import") (part "FIDUCIAL"))
    )
    (comp (ref "FUD4")
      (value "FIDUCIAL")
      (footprint "eagle-import:FIDUCIAL_40MIL")
      (libsource (lib "eagle-import") (part "FIDUCIAL"))
    )
    (comp (ref "FUD5")
      (value "FIDUCIAL")
      (footprint "eagle-import:FIDUCIAL_40MIL")
      (libsource (lib "eagle-import") (part "FIDUCIAL"))
    )
    (comp (ref "FUD6")
      (value "FIDUCIAL")
      (footprint "eagle-import:FIDUCIAL_40MIL")
      (libsource (lib "eagle-import") (part "FIDUCIAL"))
    )
    (comp (ref "G1")
      (value "CR2032V")
      (footprint "eagle-import:CR2032V")
      (libsource (lib "eagle-import") (part "CR2032V"))
    )
    (comp (ref "GDT1")
      (value "2036-07-B3")
      (footprint "eagle-import:2036-XX-B3")
      (libsource (lib "eagle-import") (part "2036-09-B3"))
    )
    (comp (ref "IC2")
      (value "ULN2003AD")
      (footprint "eagle-import:SO16")
      (libsource (lib "eagle-import") (part "ULN2003AD"))
    )
    (comp (ref "IC4")
      (value "74HC165D")
      (footprint "eagle-import:SO16")
      (libsource (lib "eagle-import") (part "74165DHC"))
    )
    (comp (ref "IC5")
      (value "74HC165D")
      (footprint "eagle-import:SO16")
      (libsource (lib "eagle-import") (part "74165DHC"))
    )
    (comp (ref "IC10")
      (value "MCP6002SMT")
      (footprint "eagle-import:SOIC8")
      (libsource (lib "eagle-import") (part "MCP6002SMT"))
    )
    (comp (ref "IC11")
      (value "MCP6002SMT")
      (footprint "eagle-import:SOIC8")
      (libsource (lib "eagle-import") (part "MCP6002SMT"))
    )
    (comp (ref "IC12")
      (value "MCP6002SMT")
      (footprint "eagle-import:SOIC8")
      (libsource (lib "eagle-import") (part "MCP6002SMT"))
    )
    (comp (ref "IC14")
      (value "MCP6002SMT")
      (footprint "eagle-import:SOIC8")
      (libsource (lib "eagle-import") (part "MCP6002SMT"))
    )
    (comp (ref "J1")
      (value "826646-2")
      (footprint "eagle-import:H2-2.54")
      (libsource (lib "eagle-import") (part "826646-2"))
    )
    (comp (ref "J3")
      (value "826646-2")
      (footprint "eagle-import:H2-2.54")
      (libsource (lib "eagle-import") (part "OSD3358-SM-RED Platform_826646-2"))
    )
    (comp (ref "J7")
      (value "826646-2")
      (footprint "eagle-import:H2-2.54")
      (libsource (lib "eagle-import") (part "OSD3358-SM-RED Platform_826646-2"))
    )
    (comp (ref "J11")
      (value "826646-2")
      (footprint "eagle-import:H2-2.54")
      (libsource (lib "eagle-import") (part "OSD3358-SM-RED Platform_826646-2"))
    )
    (comp (ref "J12")
      (value "826646-2")
      (footprint "eagle-import:H2-2.54")
      (libsource (lib "eagle-import") (part "OSD3358-SM-RED Platform_826646-2"))
    )
    (comp (ref "J13")
      (value "826646-2")
      (footprint "eagle-import:H2-2.54")
      (libsource (lib "eagle-import") (part "OSD3358-SM-RED Platform_826646-2"))
    )
    (comp (ref "J21")
      (value "826646-2")
      (footprint "eagle-import:H2-2.54")
      (libsource (lib "eagle-import") (part "OSD3358-SM-RED Platform_826646-2"))
    )
    (comp (ref "J22")
      (value "826646-2")
      (footprint "eagle-import:H2-2.54")
      (libsource (lib "eagle-import") (part "OSD3358-SM-RED Platform_826646-2"))
    )
    (comp (ref "J23")
      (value "826646-2")
      (footprint "eagle-import:H2-2.54")
      (libsource (lib "eagle-import") (part "OSD3358-SM-RED Platform_826646-2"))
    )
    (comp (ref "J24")
      (value "6p-2.54")
      (footprint "eagle-import:H3-2.54")
      (fields (field (name "MPN") "P125-1106A1BS116A1"))
      (libsource (lib "eagle-import") (part "826646-3"))
    )
    (comp (ref "J31")
      (value "826646-2")
      (footprint "eagle-import:H2-2.54")
      (libsource (lib "eagle-import") (part "OSD3358-SM-RED Platform_826646-2"))
    )
    (comp (ref "J32")
      (value "826646-2")
      (footprint "eagle-import:H2-2.54")
      (libsource (lib "eagle-import") (part "OSD3358-SM-RED Platform_826646-2"))
    )
    (comp (ref "J33")
      (value "826646-2")
      (footprint "eagle-import:H2-2.54")
      (libsource (lib "eagle-import") (part "OSD3358-SM-RED Platform_826646-2"))
    )
    (comp (ref "J41")
      (value "826646-2")
      (footprint "eagle-import:H2-2.54")
      (libsource (lib "eagle-import") (part "OSD3358-SM-RED Platform_826646-2"))
    )
    (comp (ref "J42")
      (value "826646-2")
      (footprint "eagle-import:H2-2.54")
      (libsource (lib "eagle-import") (part "OSD3358-SM-RED Platform_826646-2"))
    )
    (comp (ref "J43")
      (value "826646-2")
      (footprint "eagle-import:H2-2.54")
      (libsource (lib "eagle-import") (part "OSD3358-SM-RED Platform_826646-2"))
    )
    (comp (ref "J45")
      (value "826646-2")
      (footprint "eagle-import:H2-2.54")
      (libsource (lib "eagle-import") (part "OSD3358-SM-RED Platform_826646-2"))
    )
    (comp (ref "J51")
      (value "826646-2")
      (footprint "eagle-import:H2-2.54")
      (libsource (lib "eagle-import") (part "OSD3358-SM-RED Platform_826646-2"))
    )
    (comp (ref "J52")
      (value "826646-2")
      (footprint "eagle-import:H2-2.54")
      (libsource (lib "eagle-import") (part "OSD3358-SM-RED Platform_826646-2"))
    )
    (comp (ref "J53")
      (value "826646-2")
      (footprint "eagle-import:H2-2.54")
      (libsource (lib "eagle-import") (part "OSD3358-SM-RED Platform_826646-2"))
    )
    (comp (ref "J61")
      (value "826646-2")
      (footprint "eagle-import:H2-2.54")
      (libsource (lib "eagle-import") (part "OSD3358-SM-RED Platform_826646-2"))
    )
    (comp (ref "J62")
      (value "826646-2")
      (footprint "eagle-import:H2-2.54")
      (libsource (lib "eagle-import") (part "OSD3358-SM-RED Platform_826646-2"))
    )
    (comp (ref "J63")
      (value "826646-2")
      (footprint "eagle-import:H2-2.54")
      (libsource (lib "eagle-import") (part "OSD3358-SM-RED Platform_826646-2"))
    )
    (comp (ref "J450")
      (value "826646-2")
      (footprint "eagle-import:H2-2.54")
      (libsource (lib "eagle-import") (part "OSD3358-SM-RED Platform_826646-2"))
    )
    (comp (ref "J454")
      (value "826646-2")
      (footprint "eagle-import:H2-2.54")
      (libsource (lib "eagle-import") (part "OSD3358-SM-RED Platform_826646-2"))
    )
    (comp (ref "K1")
      (value "G5LE-14-CF DC24")
      (footprint "eagle-import:JS-M")
      (libsource (lib "eagle-import") (part "G5LE-14-CF"))
    )
    (comp (ref "K2")
      (value "G5LE-14-CF DC24")
      (footprint "eagle-import:JS-M")
      (libsource (lib "eagle-import") (part "G5LE-14-CF"))
    )
    (comp (ref "K3")
      (value "G5LE-14-CF DC24")
      (footprint "eagle-import:JS-M")
      (libsource (lib "eagle-import") (part "G5LE-14-CF"))
    )
    (comp (ref "K4")
      (value "G5LE-14-CF DC24")
      (footprint "eagle-import:JS-M")
      (libsource (lib "eagle-import") (part "G5LE-14-CF"))
    )
    (comp (ref "L2")
      (value "SRP1265A-470M")
      (footprint "eagle-import:SRP1265")
      (libsource (lib "eagle-import") (part "SRP1265"))
    )
    (comp (ref "MTG1")
      (value "MOUNT-PAD-ROUND3.6")
      (footprint "eagle-import:3,6-PAD")
      (libsource (lib "eagle-import") (part "MOUNT-PAD-ROUND3.6"))
    )
    (comp (ref "MTG2")
      (value "MOUNT-PAD-ROUND3.6")
      (footprint "eagle-import:3,6-PAD")
      (libsource (lib "eagle-import") (part "MOUNT-PAD-ROUND3.6"))
    )
    (comp (ref "MTG3")
      (value "MOUNT-PAD-ROUND3.6")
      (footprint "eagle-import:3,6-PAD")
      (libsource (lib "eagle-import") (part "MOUNT-PAD-ROUND3.6"))
    )
    (comp (ref "MTG4")
      (value "MOUNT-PAD-ROUND3.6")
      (footprint "eagle-import:3,6-PAD")
      (libsource (lib "eagle-import") (part "MOUNT-PAD-ROUND3.6"))
    )
    (comp (ref "Q1")
      (value "MMBT2907")
      (footprint "eagle-import:SOT23-BEC")
      (libsource (lib "eagle-import") (part "MMBT2907SMD"))
    )
    (comp (ref "R3")
      (value "0, 1%")
      (footprint "eagle-import:R0402")
      (libsource (lib "eagle-import") (part "OSD3358-SM-RED Platform_R-US_R0402"))
    )
    (comp (ref "R4")
      (value "0, 1%")
      (footprint "eagle-import:R0402")
      (libsource (lib "eagle-import") (part "OSD3358-SM-RED Platform_R-US_R0402"))
    )
    (comp (ref "R5")
      (value "0")
      (footprint "eagle-import:R0402")
      (libsource (lib "eagle-import") (part "R-US_R0402"))
    )
    (comp (ref "R6")
      (value "100K, DNI")
      (footprint "eagle-import:R0402")
      (libsource (lib "eagle-import") (part "R-US_R0402"))
    )
    (comp (ref "R8")
      (value "1K")
      (footprint "eagle-import:R0402")
      (libsource (lib "eagle-import") (part "R-US_R0402"))
    )
    (comp (ref "R10")
      (value "0, 1%")
      (footprint "eagle-import:R0805")
      (libsource (lib "eagle-import") (part "OSD3358-SM-RED Platform_R-US_R0805"))
    )
    (comp (ref "R11")
      (value "0")
      (footprint "eagle-import:R0402")
      (libsource (lib "eagle-import") (part "R-US_R0402"))
    )
    (comp (ref "R12")
      (value "1.5K, 1%")
      (footprint "eagle-import:R0402")
      (libsource (lib "eagle-import") (part "OSD3358-SM-RED Platform_R-US_R0402"))
    )
    (comp (ref "R13")
      (value "1.5K, 1%")
      (footprint "eagle-import:R0402")
      (libsource (lib "eagle-import") (part "OSD3358-SM-RED Platform_R-US_R0402"))
    )
    (comp (ref "R15")
      (value "40.2K")
      (footprint "eagle-import:R0402")
      (libsource (lib "eagle-import") (part "R-US_R0402"))
    )
    (comp (ref "R18")
      (value "4.75K, 1%")
      (footprint "eagle-import:R0402")
      (libsource (lib "eagle-import") (part "OSD3358-SM-RED Platform_R-US_R0402"))
    )
    (comp (ref "R20")
      (value "10K")
      (footprint "eagle-import:R0402")
      (libsource (lib "eagle-import") (part "R-US_R0402"))
    )
    (comp (ref "R21")
      (value "499")
      (footprint "eagle-import:R0402")
      (libsource (lib "eagle-import") (part "R-US_R0402"))
    )
    (comp (ref "R22")
      (value "4.75K, 1%")
      (footprint "eagle-import:R0402")
      (libsource (lib "eagle-import") (part "OSD3358-SM-RED Platform_R-US_R0402"))
    )
    (comp (ref "R25")
      (value "0, 1%")
      (footprint "eagle-import:R0402")
      (libsource (lib "eagle-import") (part "OSD3358-SM-RED Platform_R-US_R0402"))
    )
    (comp (ref "R26")
      (value "1.5K, 1%")
      (footprint "eagle-import:R0402")
      (libsource (lib "eagle-import") (part "OSD3358-SM-RED Platform_R-US_R0402"))
    )
    (comp (ref "R27")
      (value "100K, 1%")
      (footprint "eagle-import:R0402")
      (libsource (lib "eagle-import") (part "OSD3358-SM-RED Platform_R-US_R0402"))
    )
    (comp (ref "R28")
      (value "0, 1%")
      (footprint "eagle-import:R0402")
      (libsource (lib "eagle-import") (part "OSD3358-SM-RED Platform_R-US_R0402"))
    )
    (comp (ref "R29")
      (value "0, 1%")
      (footprint "eagle-import:R0402")
      (libsource (lib "eagle-import") (part "OSD3358-SM-RED Platform_R-US_R0402"))
    )
    (comp (ref "R30")
      (value "0, 1%")
      (footprint "eagle-import:R0402")
      (libsource (lib "eagle-import") (part "OSD3358-SM-RED Platform_R-US_R0402"))
    )
    (comp (ref "R31")
      (value "22, 1%")
      (footprint "eagle-import:R0402")
      (libsource (lib "eagle-import") (part "OSD3358-SM-RED Platform_R-US_R0402"))
    )
    (comp (ref "R33")
      (value "0, 1%")
      (footprint "eagle-import:R0402")
      (libsource (lib "eagle-import") (part "OSD3358-SM-RED Platform_R-US_R0402"))
    )
    (comp (ref "R34")
      (value ".1, 0805")
      (footprint "eagle-import:R0805")
      (libsource (lib "eagle-import") (part "OSD3358-SM-RED Platform_R-US_R0805"))
    )
    (comp (ref "R35")
      (value "1K")
      (footprint "eagle-import:RN0804")
      (libsource (lib "eagle-import") (part "RESISTOR.NETWORK-(4)"))
    )
    (comp (ref "R39")
      (value "4.75K, 1%")
      (footprint "eagle-import:R0402")
      (libsource (lib "eagle-import") (part "OSD3358-SM-RED Platform_R-US_R0402"))
    )
    (comp (ref "R40")
      (value "4.75K, 1%")
      (footprint "eagle-import:R0402")
      (libsource (lib "eagle-import") (part "OSD3358-SM-RED Platform_R-US_R0402"))
    )
    (comp (ref "R41")
      (value "4.75K, 1%")
      (footprint "eagle-import:R0402")
      (libsource (lib "eagle-import") (part "OSD3358-SM-RED Platform_R-US_R0402"))
    )
    (comp (ref "R53")
      (value "100K, 1%")
      (footprint "eagle-import:R0402")
      (libsource (lib "eagle-import") (part "OSD3358-SM-RED Platform_R-US_R0402"))
    )
    (comp (ref "R54")
      (value "100K, 1%, DNI")
      (footprint "eagle-import:R0402")
      (libsource (lib "eagle-import") (part "OSD3358-SM-RED Platform_R-US_R0402"))
    )
    (comp (ref "R55")
      (value "100K, 1%")
      (footprint "eagle-import:R0402")
      (libsource (lib "eagle-import") (part "OSD3358-SM-RED Platform_R-US_R0402"))
    )
    (comp (ref "R56")
      (value "100K, 1%")
      (footprint "eagle-import:R0402")
      (libsource (lib "eagle-import") (part "OSD3358-SM-RED Platform_R-US_R0402"))
    )
    (comp (ref "R57")
      (value "100K, 1%")
      (footprint "eagle-import:R0402")
      (libsource (lib "eagle-import") (part "OSD3358-SM-RED Platform_R-US_R0402"))
    )
    (comp (ref "R58")
      (value "100K, 1%")
      (footprint "eagle-import:R0402")
      (libsource (lib "eagle-import") (part "OSD3358-SM-RED Platform_R-US_R0402"))
    )
    (comp (ref "R59")
      (value "100K, 1%")
      (footprint "eagle-import:R0402")
      (libsource (lib "eagle-import") (part "OSD3358-SM-RED Platform_R-US_R0402"))
    )
    (comp (ref "R60")
      (value "100K, 1%")
      (footprint "eagle-import:R0402")
      (libsource (lib "eagle-import") (part "OSD3358-SM-RED Platform_R-US_R0402"))
    )
    (comp (ref "R61")
      (value "100K, 1%")
      (footprint "eagle-import:R0402")
      (libsource (lib "eagle-import") (part "OSD3358-SM-RED Platform_R-US_R0402"))
    )
    (comp (ref "R62")
      (value "100K, 1%")
      (footprint "eagle-import:R0402")
      (libsource (lib "eagle-import") (part "OSD3358-SM-RED Platform_R-US_R0402"))
    )
    (comp (ref "R63")
      (value "100K, 1%")
      (footprint "eagle-import:R0402")
      (libsource (lib "eagle-import") (part "OSD3358-SM-RED Platform_R-US_R0402"))
    )
    (comp (ref "R64")
      (value "100K, 1%, DNI")
      (footprint "eagle-import:R0402")
      (libsource (lib "eagle-import") (part "OSD3358-SM-RED Platform_R-US_R0402"))
    )
    (comp (ref "R65")
      (value "100K, 1%, DNI")
      (footprint "eagle-import:R0402")
      (libsource (lib "eagle-import") (part "OSD3358-SM-RED Platform_R-US_R0402"))
    )
    (comp (ref "R66")
      (value "100K, 1%, DNI")
      (footprint "eagle-import:R0402")
      (libsource (lib "eagle-import") (part "OSD3358-SM-RED Platform_R-US_R0402"))
    )
    (comp (ref "R67")
      (value "100K, 1%")
      (footprint "eagle-import:R0402")
      (libsource (lib "eagle-import") (part "OSD3358-SM-RED Platform_R-US_R0402"))
    )
    (comp (ref "R68")
      (value "100K, 1%")
      (footprint "eagle-import:R0402")
      (libsource (lib "eagle-import") (part "OSD3358-SM-RED Platform_R-US_R0402"))
    )
    (comp (ref "R69")
      (value "100, 1%")
      (footprint "eagle-import:R0402")
      (libsource (lib "eagle-import") (part "OSD3358-SM-RED Platform_R-US_R0402"))
    )
    (comp (ref "R70")
      (value "100K, 1%, DNI")
      (footprint "eagle-import:R0402")
      (libsource (lib "eagle-import") (part "OSD3358-SM-RED Platform_R-US_R0402"))
    )
    (comp (ref "R71")
      (value "100K, 1%")
      (footprint "eagle-import:R0402")
      (libsource (lib "eagle-import") (part "OSD3358-SM-RED Platform_R-US_R0402"))
    )
    (comp (ref "R72")
      (value "100K, 1%, DNI")
      (footprint "eagle-import:R0402")
      (libsource (lib "eagle-import") (part "OSD3358-SM-RED Platform_R-US_R0402"))
    )
    (comp (ref "R73")
      (value "100K, 1%, DNI")
      (footprint "eagle-import:R0402")
      (libsource (lib "eagle-import") (part "OSD3358-SM-RED Platform_R-US_R0402"))
    )
    (comp (ref "R74")
      (value "100K, 1%, DNI")
      (footprint "eagle-import:R0402")
      (libsource (lib "eagle-import") (part "OSD3358-SM-RED Platform_R-US_R0402"))
    )
    (comp (ref "R75")
      (value "100K, 1%, DNI")
      (footprint "eagle-import:R0402")
      (libsource (lib "eagle-import") (part "OSD3358-SM-RED Platform_R-US_R0402"))
    )
    (comp (ref "R76")
      (value "100K, 1%, DNI")
      (footprint "eagle-import:R0402")
      (libsource (lib "eagle-import") (part "OSD3358-SM-RED Platform_R-US_R0402"))
    )
    (comp (ref "R77")
      (value "100K, 1%, DNI")
      (footprint "eagle-import:R0402")
      (libsource (lib "eagle-import") (part "OSD3358-SM-RED Platform_R-US_R0402"))
    )
    (comp (ref "R78")
      (value "100K, 1%, DNI")
      (footprint "eagle-import:R0402")
      (libsource (lib "eagle-import") (part "OSD3358-SM-RED Platform_R-US_R0402"))
    )
    (comp (ref "R79")
      (value "100K, 1%, DNI")
      (footprint "eagle-import:R0402")
      (libsource (lib "eagle-import") (part "OSD3358-SM-RED Platform_R-US_R0402"))
    )
    (comp (ref "R80")
      (value "100K, 1%, DNI")
      (footprint "eagle-import:R0402")
      (libsource (lib "eagle-import") (part "OSD3358-SM-RED Platform_R-US_R0402"))
    )
    (comp (ref "R81")
      (value "100K, 1%")
      (footprint "eagle-import:R0402")
      (libsource (lib "eagle-import") (part "OSD3358-SM-RED Platform_R-US_R0402"))
    )
    (comp (ref "R82")
      (value "100K, 1%")
      (footprint "eagle-import:R0402")
      (libsource (lib "eagle-import") (part "OSD3358-SM-RED Platform_R-US_R0402"))
    )
    (comp (ref "R83")
      (value "100K, 1%")
      (footprint "eagle-import:R0402")
      (libsource (lib "eagle-import") (part "OSD3358-SM-RED Platform_R-US_R0402"))
    )
    (comp (ref "R84")
      (value "100K, 1%, DNI")
      (footprint "eagle-import:R0402")
      (libsource (lib "eagle-import") (part "OSD3358-SM-RED Platform_R-US_R0402"))
    )
    (comp (ref "R85")
      (value "100K, 1%, DNI")
      (footprint "eagle-import:R0402")
      (libsource (lib "eagle-import") (part "OSD3358-SM-RED Platform_R-US_R0402"))
    )
    (comp (ref "R86")
      (value "10K, 1%")
      (footprint "eagle-import:R0402")
      (libsource (lib "eagle-import") (part "OSD3358-SM-RED Platform_R-US_R0402"))
    )
    (comp (ref "R87")
      (value "10K, 1%")
      (footprint "eagle-import:R0402")
      (libsource (lib "eagle-import") (part "OSD3358-SM-RED Platform_R-US_R0402"))
    )
    (comp (ref "R88")
      (value "10K, 1%")
      (footprint "eagle-import:R0402")
      (libsource (lib "eagle-import") (part "OSD3358-SM-RED Platform_R-US_R0402"))
    )
    (comp (ref "R89")
      (value "10K, 1%")
      (footprint "eagle-import:R0402")
      (libsource (lib "eagle-import") (part "OSD3358-SM-RED Platform_R-US_R0402"))
    )
    (comp (ref "R90")
      (value "10K, 1%")
      (footprint "eagle-import:R0402")
      (libsource (lib "eagle-import") (part "OSD3358-SM-RED Platform_R-US_R0402"))
    )
    (comp (ref "R91")
      (value "10K, 1%")
      (footprint "eagle-import:R0402")
      (libsource (lib "eagle-import") (part "OSD3358-SM-RED Platform_R-US_R0402"))
    )
    (comp (ref "R92")
      (value "10K, 1%")
      (footprint "eagle-import:R0402")
      (libsource (lib "eagle-import") (part "OSD3358-SM-RED Platform_R-US_R0402"))
    )
    (comp (ref "R163")
      (value "100K, DNI")
      (footprint "eagle-import:R0402")
      (libsource (lib "eagle-import") (part "OSD3358-SM-RED Platform_R-US_R0402"))
    )
    (comp (ref "R164")
      (value "1.5K, 1%")
      (footprint "eagle-import:R0402")
      (libsource (lib "eagle-import") (part "OSD3358-SM-RED Platform_R-US_R0402"))
    )
    (comp (ref "R168")
      (value "10K")
      (footprint "eagle-import:R0402")
      (libsource (lib "eagle-import") (part "OSD3358-SM-RED Platform_R-US_R0402"))
    )
    (comp (ref "R169")
      (value "10K, 1%")
      (footprint "eagle-import:R0402")
      (libsource (lib "eagle-import") (part "OSD3358-SM-RED Platform_R-US_R0402"))
    )
    (comp (ref "R170")
      (value "10K, 1%")
      (footprint "eagle-import:R0402")
      (libsource (lib "eagle-import") (part "OSD3358-SM-RED Platform_R-US_R0402"))
    )
    (comp (ref "R171")
      (value "10K")
      (footprint "eagle-import:R0402")
      (libsource (lib "eagle-import") (part "OSD3358-SM-RED Platform_R-US_R0402"))
    )
    (comp (ref "R172")
      (value "10K")
      (footprint "eagle-import:R0402")
      (libsource (lib "eagle-import") (part "OSD3358-SM-RED Platform_R-US_R0402"))
    )
    (comp (ref "R173")
      (value "10K")
      (footprint "eagle-import:R0402")
      (libsource (lib "eagle-import") (part "OSD3358-SM-RED Platform_R-US_R0402"))
    )
    (comp (ref "R174")
      (value "10K")
      (footprint "eagle-import:R0402")
      (libsource (lib "eagle-import") (part "OSD3358-SM-RED Platform_R-US_R0402"))
    )
    (comp (ref "R181")
      (value "B72520T0300K062")
      (footprint "eagle-import:CT_CN1206")
      (libsource (lib "eagle-import") (part "VARISTORCN1206"))
    )
    (comp (ref "R182")
      (value "B72520T0300K062")
      (footprint "eagle-import:CT_CN1206")
      (libsource (lib "eagle-import") (part "VARISTORCN1206"))
    )
    (comp (ref "R183")
      (value "B72520T0300K062")
      (footprint "eagle-import:CT_CN1206")
      (libsource (lib "eagle-import") (part "VARISTORCN1206"))
    )
    (comp (ref "R184")
      (value "B72520T0300K062")
      (footprint "eagle-import:CT_CN1206")
      (libsource (lib "eagle-import") (part "VARISTORCN1206"))
    )
    (comp (ref "R185")
      (value "B72520T0300K062")
      (footprint "eagle-import:CT_CN1206")
      (libsource (lib "eagle-import") (part "VARISTORCN1206"))
    )
    (comp (ref "R186")
      (value "B72520T0300K062")
      (footprint "eagle-import:CT_CN1206")
      (libsource (lib "eagle-import") (part "VARISTORCN1206"))
    )
    (comp (ref "R211")
      (value "80, 0.1%")
      (footprint "eagle-import:0309_12")
      (libsource (lib "eagle-import") (part "resistor_348_R-US_0309/12"))
    )
    (comp (ref "R212")
      (value "10K, 1%")
      (footprint "eagle-import:R0805")
      (libsource (lib "eagle-import") (part "OSD3358-SM-RED Platform_R-US_R0805"))
    )
    (comp (ref "R213")
      (value "2K, 1%")
      (footprint "eagle-import:R0805")
      (libsource (lib "eagle-import") (part "OSD3358-SM-RED Platform_R-US_R0805"))
    )
    (comp (ref "R214")
      (value "10K, 1%")
      (footprint "eagle-import:R0805")
      (libsource (lib "eagle-import") (part "OSD3358-SM-RED Platform_R-US_R0805"))
    )
    (comp (ref "R215")
      (value "100K")
      (footprint "eagle-import:R0805")
      (libsource (lib "eagle-import") (part "OSD3358-SM-RED Platform_R-US_R0805"))
    )
    (comp (ref "R221")
      (value "80, 0.1%")
      (footprint "eagle-import:0309_12")
      (libsource (lib "eagle-import") (part "resistor_348_R-US_0309/12"))
    )
    (comp (ref "R222")
      (value "10K, 1%")
      (footprint "eagle-import:R0805")
      (libsource (lib "eagle-import") (part "OSD3358-SM-RED Platform_R-US_R0805"))
    )
    (comp (ref "R223")
      (value "2K, 1%")
      (footprint "eagle-import:R0805")
      (libsource (lib "eagle-import") (part "OSD3358-SM-RED Platform_R-US_R0805"))
    )
    (comp (ref "R224")
      (value "10K, 1%")
      (footprint "eagle-import:R0805")
      (libsource (lib "eagle-import") (part "OSD3358-SM-RED Platform_R-US_R0805"))
    )
    (comp (ref "R225")
      (value "100K")
      (footprint "eagle-import:R0805")
      (libsource (lib "eagle-import") (part "OSD3358-SM-RED Platform_R-US_R0805"))
    )
    (comp (ref "R231")
      (value "80, 0.1%")
      (footprint "eagle-import:0309_12")
      (libsource (lib "eagle-import") (part "resistor_348_R-US_0309/12"))
    )
    (comp (ref "R232")
      (value "10K, 1%")
      (footprint "eagle-import:R0805")
      (libsource (lib "eagle-import") (part "OSD3358-SM-RED Platform_R-US_R0805"))
    )
    (comp (ref "R233")
      (value "2K, 1%")
      (footprint "eagle-import:R0805")
      (libsource (lib "eagle-import") (part "OSD3358-SM-RED Platform_R-US_R0805"))
    )
    (comp (ref "R234")
      (value "10K, 1%")
      (footprint "eagle-import:R0805")
      (libsource (lib "eagle-import") (part "OSD3358-SM-RED Platform_R-US_R0805"))
    )
    (comp (ref "R235")
      (value "100K")
      (footprint "eagle-import:R0805")
      (libsource (lib "eagle-import") (part "OSD3358-SM-RED Platform_R-US_R0805"))
    )
    (comp (ref "R241")
      (value "80, 0.1%")
      (footprint "eagle-import:0309_12")
      (libsource (lib "eagle-import") (part "resistor_348_R-US_0309/12"))
    )
    (comp (ref "R242")
      (value "10K, 1%")
      (footprint "eagle-import:R0805")
      (libsource (lib "eagle-import") (part "OSD3358-SM-RED Platform_R-US_R0805"))
    )
    (comp (ref "R243")
      (value "2K, 1%")
      (footprint "eagle-import:R0805")
      (libsource (lib "eagle-import") (part "OSD3358-SM-RED Platform_R-US_R0805"))
    )
    (comp (ref "R244")
      (value "10K, 1%")
      (footprint "eagle-import:R0805")
      (libsource (lib "eagle-import") (part "OSD3358-SM-RED Platform_R-US_R0805"))
    )
    (comp (ref "R245")
      (value "100K")
      (footprint "eagle-import:R0805")
      (libsource (lib "eagle-import") (part "OSD3358-SM-RED Platform_R-US_R0805"))
    )
    (comp (ref "R251")
      (value "80, 0.1%")
      (footprint "eagle-import:0309_12")
      (libsource (lib "eagle-import") (part "resistor_348_R-US_0309/12"))
    )
    (comp (ref "R252")
      (value "10K, 1%")
      (footprint "eagle-import:R0805")
      (libsource (lib "eagle-import") (part "OSD3358-SM-RED Platform_R-US_R0805"))
    )
    (comp (ref "R253")
      (value "2K, 1%")
      (footprint "eagle-import:R0805")
      (libsource (lib "eagle-import") (part "OSD3358-SM-RED Platform_R-US_R0805"))
    )
    (comp (ref "R254")
      (value "10K, 1%")
      (footprint "eagle-import:R0805")
      (libsource (lib "eagle-import") (part "OSD3358-SM-RED Platform_R-US_R0805"))
    )
    (comp (ref "R255")
      (value "100K")
      (footprint "eagle-import:R0805")
      (libsource (lib "eagle-import") (part "OSD3358-SM-RED Platform_R-US_R0805"))
    )
    (comp (ref "R261")
      (value "80, 0.1%")
      (footprint "eagle-import:0309_12")
      (libsource (lib "eagle-import") (part "resistor_348_R-US_0309/12"))
    )
    (comp (ref "R262")
      (value "10K, 1%")
      (footprint "eagle-import:R0805")
      (libsource (lib "eagle-import") (part "OSD3358-SM-RED Platform_R-US_R0805"))
    )
    (comp (ref "R263")
      (value "2K, 1%")
      (footprint "eagle-import:R0805")
      (libsource (lib "eagle-import") (part "OSD3358-SM-RED Platform_R-US_R0805"))
    )
    (comp (ref "R264")
      (value "10K, 1%")
      (footprint "eagle-import:R0805")
      (libsource (lib "eagle-import") (part "OSD3358-SM-RED Platform_R-US_R0805"))
    )
    (comp (ref "R265")
      (value "100K")
      (footprint "eagle-import:R0805")
      (libsource (lib "eagle-import") (part "OSD3358-SM-RED Platform_R-US_R0805"))
    )
    (comp (ref "R281")
      (value "10K")
      (footprint "eagle-import:RN0804")
      (libsource (lib "eagle-import") (part "RESISTOR.NETWORK-(4)"))
    )
    (comp (ref "R282")
      (value "10K")
      (footprint "eagle-import:RN0804")
      (libsource (lib "eagle-import") (part "RESISTOR.NETWORK-(4)"))
    )
    (comp (ref "R291")
      (value "10K")
      (footprint "eagle-import:RN0804")
      (libsource (lib "eagle-import") (part "RESISTOR.NETWORK-(4)"))
    )
    (comp (ref "R301")
      (value "1K")
      (footprint "eagle-import:R0402")
      (libsource (lib "eagle-import") (part "OSD3358-SM-RED Platform_R-US_R0402"))
    )
    (comp (ref "R302")
      (value "1K")
      (footprint "eagle-import:R0402")
      (libsource (lib "eagle-import") (part "OSD3358-SM-RED Platform_R-US_R0402"))
    )
    (comp (ref "R303")
      (value "1K, DNI")
      (footprint "eagle-import:R0402")
      (libsource (lib "eagle-import") (part "OSD3358-SM-RED Platform_R-US_R0402"))
    )
    (comp (ref "R304")
      (value "1K, DNI")
      (footprint "eagle-import:R0402")
      (libsource (lib "eagle-import") (part "OSD3358-SM-RED Platform_R-US_R0402"))
    )
    (comp (ref "R305")
      (value "150, 1%")
      (footprint "eagle-import:R0805")
      (libsource (lib "eagle-import") (part "OSD3358-SM-RED Platform_R-US_R0805"))
    )
    (comp (ref "R401")
      (value "1K")
      (footprint "eagle-import:R0402")
      (libsource (lib "eagle-import") (part "OSD3358-SM-RED Platform_R-US_R0402"))
    )
    (comp (ref "R402")
      (value "1K")
      (footprint "eagle-import:R0402")
      (libsource (lib "eagle-import") (part "OSD3358-SM-RED Platform_R-US_R0402"))
    )
    (comp (ref "R801")
      (value "1K")
      (footprint "eagle-import:R0402")
      (libsource (lib "eagle-import") (part "OSD3358-SM-RED Platform_R-US_R0402"))
    )
    (comp (ref "R802")
      (value "1K")
      (footprint "eagle-import:R0402")
      (libsource (lib "eagle-import") (part "OSD3358-SM-RED Platform_R-US_R0402"))
    )
    (comp (ref "R901")
      (value "1.5K, 1% DNI")
      (footprint "eagle-import:R0402")
      (libsource (lib "eagle-import") (part "OSD3358-SM-RED Platform_R-US_R0402"))
    )
    (comp (ref "R902")
      (value "1.5K, 1% DNI")
      (footprint "eagle-import:R0402")
      (libsource (lib "eagle-import") (part "OSD3358-SM-RED Platform_R-US_R0402"))
    )
    (comp (ref "RTC1")
      (value "DS3231MZ+")
      (footprint "eagle-import:SO08")
      (libsource (lib "eagle-import") (part "DS3231M"))
    )
    (comp (ref "S1")
      (value "KMR231GLFS")
      (footprint "eagle-import:SW4SMD_63X161LS")
      (libsource (lib "eagle-import") (part "KMR231GLFS"))
    )
    (comp (ref "S2")
      (value "KMR231GLFS")
      (footprint "eagle-import:SW4SMD_63X161LS")
      (libsource (lib "eagle-import") (part "OSD3358-SM-RED Platform_KMR231GLFS"))
    )
    (comp (ref "S11")
      (value "P101")
      (footprint "eagle-import:P101")
      (libsource (lib "eagle-import") (part "P101"))
    )
    (comp (ref "S12")
      (value "P101")
      (footprint "eagle-import:P101")
      (libsource (lib "eagle-import") (part "P101"))
    )
    (comp (ref "S13")
      (value "DS04")
      (footprint "eagle-import:DS-04")
      (libsource (lib "eagle-import") (part "DS04"))
    )
    (comp (ref "T4")
      (value "DA2304-AL")
      (footprint "eagle-import:DA230X-AL")
      (libsource (lib "eagle-import") (part "DA2304-AL"))
    )
    (comp (ref "TP1")
      (value "TPB0,65")
      (footprint "eagle-import:TP_B0,65")
      (libsource (lib "eagle-import") (part "OSD3358-SM-RED Platform_TPB0,65"))
    )
    (comp (ref "TP2")
      (value "TPB0,65")
      (footprint "eagle-import:TP_B0,65")
      (libsource (lib "eagle-import") (part "OSD3358-SM-RED Platform_TPB0,65"))
    )
    (comp (ref "TP3")
      (value "TPB0,65")
      (footprint "eagle-import:TP_B0,65")
      (libsource (lib "eagle-import") (part "OSD3358-SM-RED Platform_TPB0,65"))
    )
    (comp (ref "TP4")
      (value "TPB0,65")
      (footprint "eagle-import:TP_B0,65")
      (libsource (lib "eagle-import") (part "OSD3358-SM-RED Platform_TPB0,65"))
    )
    (comp (ref "TP5")
      (value "TESTPAD/W_HOLE_1X1")
      (footprint "eagle-import:TESTPAD_W_HOLE_1X1")
      (libsource (lib "eagle-import") (part "TESTPAD/W_HOLE_1X1"))
    )
    (comp (ref "TP6")
      (value "TESTPAD/W_HOLE_1X1")
      (footprint "eagle-import:TESTPAD_W_HOLE_1X1")
      (libsource (lib "eagle-import") (part "TESTPAD/W_HOLE_1X1"))
    )
    (comp (ref "TP7")
      (value "TESTPAD/W_HOLE_1X1")
      (footprint "eagle-import:TESTPAD_W_HOLE_1X1")
      (libsource (lib "eagle-import") (part "TESTPAD/W_HOLE_1X1"))
    )
    (comp (ref "TP8")
      (value "TESTPAD/W_HOLE_1X1")
      (footprint "eagle-import:TESTPAD_W_HOLE_1X1")
      (libsource (lib "eagle-import") (part "TESTPAD/W_HOLE_1X1"))
    )
    (comp (ref "TP9")
      (value "TESTPAD/W_HOLE_1X1")
      (footprint "eagle-import:TESTPAD_W_HOLE_1X1")
      (libsource (lib "eagle-import") (part "TESTPAD/W_HOLE_1X1"))
    )
    (comp (ref "TP10")
      (value "TESTPAD/W_HOLE_1X1")
      (footprint "eagle-import:TESTPAD_W_HOLE_1X1")
      (libsource (lib "eagle-import") (part "TESTPAD/W_HOLE_1X1"))
    )
    (comp (ref "TP11")
      (value "TPB0,65")
      (footprint "eagle-import:TP_B0,65")
      (libsource (lib "eagle-import") (part "OSD3358-SM-RED Platform_TPB0,65"))
    )
    (comp (ref "TP12")
      (value "TPB0,65")
      (footprint "eagle-import:TP_B0,65")
      (libsource (lib "eagle-import") (part "OSD3358-SM-RED Platform_TPB0,65"))
    )
    (comp (ref "TP13")
      (value "TPB0,65")
      (footprint "eagle-import:TP_B0,65")
      (libsource (lib "eagle-import") (part "OSD3358-SM-RED Platform_TPB0,65"))
    )
    (comp (ref "TP14")
      (value "TPB0,65")
      (footprint "eagle-import:TP_B0,65")
      (libsource (lib "eagle-import") (part "OSD3358-SM-RED Platform_TPB0,65"))
    )
    (comp (ref "TP15")
      (value "TPB0,65")
      (footprint "eagle-import:TP_B0,65")
      (libsource (lib "eagle-import") (part "OSD3358-SM-RED Platform_TPB0,65"))
    )
    (comp (ref "TP16")
      (value "TPB0,65")
      (footprint "eagle-import:TP_B0,65")
      (libsource (lib "eagle-import") (part "OSD3358-SM-RED Platform_TPB0,65"))
    )
    (comp (ref "TP17")
      (value "TESTPAD/W_HOLE_1X1")
      (footprint "eagle-import:TESTPAD_W_HOLE_1X1")
      (libsource (lib "eagle-import") (part "TESTPAD/W_HOLE_1X1"))
    )
    (comp (ref "TP18")
      (value "TESTPAD/W_HOLE_1X1")
      (footprint "eagle-import:TESTPAD_W_HOLE_1X1")
      (libsource (lib "eagle-import") (part "TESTPAD/W_HOLE_1X1"))
    )
    (comp (ref "TP19")
      (value "TESTPAD/W_HOLE_1X1")
      (footprint "eagle-import:TESTPAD_W_HOLE_1X1")
      (libsource (lib "eagle-import") (part "TESTPAD/W_HOLE_1X1"))
    )
    (comp (ref "TP20")
      (value "TESTPAD/W_HOLE_1X1")
      (footprint "eagle-import:TESTPAD_W_HOLE_1X1")
      (libsource (lib "eagle-import") (part "TESTPAD/W_HOLE_1X1"))
    )
    (comp (ref "TP21")
      (value "TPB0,65")
      (footprint "eagle-import:TP_B0,65")
      (libsource (lib "eagle-import") (part "OSD3358-SM-RED Platform_TPB0,65"))
    )
    (comp (ref "TP22")
      (value "TPB0,65")
      (footprint "eagle-import:TP_B0,65")
      (libsource (lib "eagle-import") (part "OSD3358-SM-RED Platform_TPB0,65"))
    )
    (comp (ref "TP23")
      (value "TPB0,65")
      (footprint "eagle-import:TP_B0,65")
      (libsource (lib "eagle-import") (part "OSD3358-SM-RED Platform_TPB0,65"))
    )
    (comp (ref "TP24")
      (value "TPB0,65")
      (footprint "eagle-import:TP_B0,65")
      (libsource (lib "eagle-import") (part "OSD3358-SM-RED Platform_TPB0,65"))
    )
    (comp (ref "TP26")
      (value "TPB0,65")
      (footprint "eagle-import:TP_B0,65")
      (libsource (lib "eagle-import") (part "TPB0,65"))
    )
    (comp (ref "TP31")
      (value "TPB0,65")
      (footprint "eagle-import:TP_B0,65")
      (libsource (lib "eagle-import") (part "TPB0,65"))
    )
    (comp (ref "TP32")
      (value "TPB0,65")
      (footprint "eagle-import:TP_B0,65")
      (libsource (lib "eagle-import") (part "OSD3358-SM-RED Platform_TPB0,65"))
    )
    (comp (ref "TP33")
      (value "TPB0,65")
      (footprint "eagle-import:TP_B0,65")
      (libsource (lib "eagle-import") (part "OSD3358-SM-RED Platform_TPB0,65"))
    )
    (comp (ref "U1")
      (value "OSD3358-512M-ICB")
      (footprint "eagle-import:OSD335X-BGA-400")
      (libsource (lib "eagle-import") (part "OSD3358-512M-ICB"))
    )
    (comp (ref "U2")
      (value "TPD4S012_DRY_6_P1_M")
      (footprint "eagle-import:DRY6")
      (fields
        (field (name "GENERIC_PART_NUMBER") "TPD4S012")
        (field (name "MANUFACTURER") "Texas Instruments")
        (field (name "MANUFACTURER_PART_NUMBER") "tpd4s012_dry_6")
      )
      (libsource (lib "eagle-import") (part "TPD4S012_DRY_6_P1_M"))
    )
    (comp (ref "U4")
      (value "APX811-31UGSOT")
      (footprint "eagle-import:SOT143-R")
      (libsource (lib "eagle-import") (part "APX811-31UGSOT"))
    )
    (comp (ref "U5")
      (value "TLVH431")
      (footprint "eagle-import:SOT23-3")
      (libsource (lib "eagle-import") (part "TLVH431"))
    )
    (comp (ref "U6")
      (value "SN74LVC2G241_DCU_8")
      (footprint "eagle-import:DCU8")
      (fields
        (field (name "GENERIC_PART_NUMBER") "SN74LVC2G241")
        (field (name "MANUFACTURER") "Texas Instruments")
        (field (name "MANUFACTURER_PART_NUMBER") "sn74lvc2g241_dcu_8")
      )
      (libsource (lib "eagle-import") (part "SN74LVC2G241_DCU_8"))
    )
    (comp (ref "U16")
      (value "AT97SC3205T-G3M4400B")
      (footprint "eagle-import:QFN32-0.4-4X4MM")
      (libsource (lib "eagle-import") (part "AT97SC3205T-G3M4400B"))
    )
    (comp (ref "U27")
      (value "LAN8710")
      (footprint "eagle-import:LAN8710A-QFN32")
      (libsource (lib "eagle-import") (part "LAN8710"))
    )
    (comp (ref "U28")
      (value "TCAN1051HV")
      (footprint "eagle-import:BEAGLEBONE_BLUE_D8")
      (fields
        (field (name "MANUFACTURER") "Texas Instruments")
        (field (name "MANUFACTURER_PART_NUMBER") "TCAN1051HVD")
      )
      (libsource (lib "eagle-import") (part "TCAN1051HV"))
    )
    (comp (ref "U29")
      (value "MAX3483EESA+T")
      (footprint "eagle-import:21-0041B_8")
      (libsource (lib "eagle-import") (part "MAX3483EESA+T"))
    )
    (comp (ref "U40")
      (value "ISO3086TDW")
      (footprint "eagle-import:DW16")
      (libsource (lib "eagle-import") (part "ISO3086TDW"))
    )
    (comp (ref "VREG1")
      (value "LM2596S-5.0")
      (footprint "eagle-import:TO263-5")
      (libsource (lib "eagle-import") (part "LM2596S"))
    )
    (comp (ref "VREG2")
      (value "L7824CV")
      (footprint "eagle-import:78XXL")
      (libsource (lib "eagle-import") (part "78XXL"))
    )
    (comp (ref "VREG4")
      (value "TPS76350")
      (footprint "eagle-import:DBV5")
      (fields (field (name "MANUFACTURER_PART_NUMBER") "LP2985A33DBVR"))
      (libsource (lib "eagle-import") (part "LP2985A-33DBVR"))
    )
    (comp (ref "X1")
      (value "10118194-0001LF")
      (footprint "eagle-import:10118194-0001LF(MICRO-USB-B-AMPHENOL-FCI)")
      (libsource (lib "eagle-import") (part "10118194-0001LF"))
    )
    (comp (ref "X2")
      (value "J0011D01BNL")
      (footprint "eagle-import:J0011D01BNL")
      (libsource (lib "eagle-import") (part "J0011D01BNL"))
    )
    (comp (ref "X3")
      (value "MC4")
      (footprint "eagle-import:MC4")
      (libsource (lib "eagle-import") (part "MC4"))
    )
    (comp (ref "X4")
      (value "CTI-JTAG")
      (footprint "eagle-import:CTI-JTAG")
      (libsource (lib "eagle-import") (part "CTI-JTAG"))
    )
    (comp (ref "X5")
      (value "DM3CS-SF")
      (footprint "eagle-import:DM3CS-SF")
      (fields (field (name "MOUSER_PART_NUMBER") "798-DM3CSSF"))
      (libsource (lib "eagle-import") (part "DM3CS-SF"))
    )
    (comp (ref "X6")
      (value "6p-2.54")
      (footprint "eagle-import:H6-2.54")
      (fields (field (name "MPN") "P125-1106A1BS116A1"))
      (libsource (lib "eagle-import") (part "826646-6"))
    )
    (comp (ref "X7")
      (value "TH-2X10")
      (footprint "eagle-import:H2X10-2.54")
      (libsource (lib "eagle-import") (part "TH-2X10"))
    )
    (comp (ref "X8")
      (value "TH-2X10")
      (footprint "eagle-import:H2X10-2.54")
      (libsource (lib "eagle-import") (part "TH-2X10"))
    )
    (comp (ref "X9")
      (value "5600200420")
      (footprint "eagle-import:5600200420")
      (libsource (lib "eagle-import") (part "5600200420"))
    )
    (comp (ref "X10")
      (value "MC4")
      (footprint "eagle-import:MC4")
      (libsource (lib "eagle-import") (part "MC4"))
    )
    (comp (ref "X11")
      (value "MC4")
      (footprint "eagle-import:MC4")
      (libsource (lib "eagle-import") (part "MC4"))
    )
    (comp (ref "X12")
      (value "MC4")
      (footprint "eagle-import:MC4")
      (libsource (lib "eagle-import") (part "MC4"))
    )
    (comp (ref "X21")
      (value "MC12")
      (footprint "eagle-import:MC12")
      (libsource (lib "eagle-import") (part "MC12"))
    )
    (comp (ref "X24")
      (value "MSTBA2")
      (footprint "eagle-import:MSTBA2")
      (fields (field (name "MF") "FARNELL") (field (name "MPN") "1757242"))
      (libsource (lib "eagle-import") (part "MSTBA2"))
    )
    (comp (ref "X31")
      (value "MC4")
      (footprint "eagle-import:MC4")
      (libsource (lib "eagle-import") (part "MC4"))
    )
    (comp (ref "X41")
      (value "MSTBA3")
      (footprint "eagle-import:MSTBA3")
      (fields (field (name "MF") "FARNELL") (field (name "MPN") "1757255"))
      (libsource (lib "eagle-import") (part "MSTBA3"))
    )
    (comp (ref "Y7")
      (value "ECS-250-12-30-GN-TR")
      (footprint "eagle-import:XTAL_2-SMD(5X3.2MM)")
      (libsource (lib "eagle-import") (part "CRYSTAL-2-SMD"))
    )
  )
  (nets
    (net (code "1") (name "/1P8V_REF_1") (class "Default")
      (node (ref "IC10") (pin "8") (pinfunction "V+_8") (pintype "power_in"))
      (node (ref "IC11") (pin "8") (pinfunction "V+_8") (pintype "power_in"))
      (node (ref "IC14") (pin "1") (pinfunction "OUT_1") (pintype "output"))
      (node (ref "IC14") (pin "2") (pinfunction "-IN_2") (pintype "input"))
      (node (ref "R212") (pin "2") (pinfunction "2_2") (pintype "passive"))
      (node (ref "R222") (pin "2") (pinfunction "2_2") (pintype "passive"))
      (node (ref "R232") (pin "2") (pinfunction "2_2") (pintype "passive"))
      (node (ref "R242") (pin "2") (pinfunction "2_2") (pintype "passive"))
    )
    (net (code "2") (name "/1P8V_REF_2") (class "Default")
      (node (ref "IC12") (pin "8") (pinfunction "V+_8") (pintype "power_in"))
      (node (ref "IC14") (pin "6") (pinfunction "-IN_6") (pintype "input"))
      (node (ref "IC14") (pin "7") (pinfunction "OUT_7") (pintype "output"))
      (node (ref "R252") (pin "2") (pinfunction "2_2") (pintype "passive"))
      (node (ref "R262") (pin "2") (pinfunction "2_2") (pintype "passive"))
    )
    (net (code "3") (name "/5V_OUT") (class "Default")
      (node (ref "D18") (pin "C") (pinfunction "C_C") (pintype "passive"))
      (node (ref "L2") (pin "1") (pinfunction "1_1") (pintype "passive"))
      (node (ref "VREG1") (pin "2") (pinfunction "OUT_2") (pintype "output"))
    )
    (net (code "4") (name "/41_A") (class "Default")
      (node (ref "F402") (pin "1") (pinfunction "1_1") (pintype "passive"))
      (node (ref "GDT1") (pin "1") (pinfunction "1_1") (pintype "passive"))
      (node (ref "X41") (pin "2") (pinfunction "1_2") (pintype "passive"))
    )
    (net (code "5") (name "/41_B") (class "Default")
      (node (ref "F401") (pin "1") (pinfunction "1_1") (pintype "passive"))
      (node (ref "GDT1") (pin "2") (pinfunction "2_2") (pintype "passive"))
      (node (ref "X41") (pin "1") (pinfunction "1_1") (pintype "passive"))
    )
    (net (code "6") (name "/485_A") (class "Default")
      (node (ref "D305") (pin "1") (pinfunction "1_1") (pintype "passive"))
      (node (ref "R304") (pin "2") (pinfunction "2_2") (pintype "passive"))
      (node (ref "R305") (pin "2") (pinfunction "2_2") (pintype "passive"))
      (node (ref "U29") (pin "6") (pinfunction "A_6") (pintype "bidirectional"))
      (node (ref "X3") (pin "2") (pinfunction "SK_2") (pintype "passive"))
    )
    (net (code "7") (name "/485_B") (class "Default")
      (node (ref "D305") (pin "2") (pinfunction "2_2") (pintype "passive"))
      (node (ref "R303") (pin "1") (pinfunction "1_1") (pintype "passive"))
      (node (ref "R305") (pin "1") (pinfunction "1_1") (pintype "passive"))
      (node (ref "U29") (pin "7") (pinfunction "B_7") (pintype "bidirectional"))
      (node (ref "X3") (pin "3") (pinfunction "SK_3") (pintype "passive"))
    )
    (net (code "8") (name "/485_RXD") (class "Default")
      (node (ref "D402") (pin "2") (pinfunction "C_2") (pintype "passive"))
      (node (ref "J45") (pin "1") (pinfunction "1_1") (pintype "bidirectional"))
      (node (ref "U40") (pin "5") (pinfunction "R_5") (pintype "passive"))
    )
    (net (code "9") (name "/485_TXD") (class "Default")
      (node (ref "D401") (pin "2") (pinfunction "C_2") (pintype "passive"))
      (node (ref "J45") (pin "2") (pinfunction "2_2") (pintype "bidirectional"))
      (node (ref "U40") (pin "8") (pinfunction "D_8") (pintype "passive"))
    )
    (net (code "10") (name "/AIN0") (class "Default")
      (node (ref "U1") (pin "Y10") (pinfunction "AIN0_Y10") (pintype "bidirectional"))
    )
    (net (code "11") (name "/AIN1") (class "Default")
      (node (ref "IC10") (pin "1") (pinfunction "OUT_1") (pintype "output"))
      (node (ref "IC10") (pin "2") (pinfunction "-IN_2") (pintype "input"))
      (node (ref "R215") (pin "1") (pinfunction "1_1") (pintype "passive"))
      (node (ref "U1") (pin "W10") (pinfunction "AIN1_W10") (pintype "bidirectional"))
    )
    (net (code "12") (name "/AIN2") (class "Default")
      (node (ref "IC10") (pin "6") (pinfunction "-IN_6") (pintype "input"))
      (node (ref "IC10") (pin "7") (pinfunction "OUT_7") (pintype "output"))
      (node (ref "R225") (pin "1") (pinfunction "1_1") (pintype "passive"))
      (node (ref "U1") (pin "V10") (pinfunction "AIN2_V10") (pintype "bidirectional"))
    )
    (net (code "13") (name "/AIN3") (class "Default")
      (node (ref "IC11") (pin "1") (pinfunction "OUT_1") (pintype "output"))
      (node (ref "IC11") (pin "2") (pinfunction "-IN_2") (pintype "input"))
      (node (ref "R235") (pin "1") (pinfunction "1_1") (pintype "passive"))
      (node (ref "U1") (pin "V9") (pinfunction "AIN3_V9") (pintype "bidirectional"))
    )
    (net (code "14") (name "/AIN4") (class "Default")
      (node (ref "IC11") (pin "6") (pinfunction "-IN_6") (pintype "input"))
      (node (ref "IC11") (pin "7") (pinfunction "OUT_7") (pintype "output"))
      (node (ref "R245") (pin "1") (pinfunction "1_1") (pintype "passive"))
      (node (ref "U1") (pin "Y11") (pinfunction "AIN4_Y11") (pintype "bidirectional"))
    )
    (net (code "15") (name "/AIN5") (class "Default")
      (node (ref "IC12") (pin "1") (pinfunction "OUT_1") (pintype "output"))
      (node (ref "IC12") (pin "2") (pinfunction "-IN_2") (pintype "input"))
      (node (ref "R255") (pin "1") (pinfunction "1_1") (pintype "passive"))
      (node (ref "U1") (pin "W11") (pinfunction "AIN5_W11") (pintype "bidirectional"))
    )
    (net (code "16") (name "/AIN6") (class "Default")
      (node (ref "IC12") (pin "6") (pinfunction "-IN_6") (pintype "input"))
      (node (ref "IC12") (pin "7") (pinfunction "OUT_7") (pintype "output"))
      (node (ref "R265") (pin "1") (pinfunction "1_1") (pintype "passive"))
      (node (ref "U1") (pin "V11") (pinfunction "AIN6_V11") (pintype "bidirectional"))
    )
    (net (code "17") (name "/AIN7") (class "Default")
      (node (ref "U1") (pin "U12") (pinfunction "PMIC_MUX_OUT_U12") (pintype "bidirectional"))
      (node (ref "U1") (pin "V12") (pinfunction "AIN7_V12") (pintype "bidirectional"))
    )
    (net (code "18") (name "/B03_NO") (class "Default")
      (node (ref "K3") (pin "NO") (pinfunction "S_NO") (pintype "passive"))
      (node (ref "X21") (pin "6") (pinfunction "SK_6") (pintype "passive"))
    )
    (net (code "19") (name "/BAT_SENSE") (class "Default")
      (node (ref "TP6") (pin "P$1") (pinfunction "TP_P$1") (pintype "bidirectional"))
      (node (ref "U1") (pin "E19") (pinfunction "PMIC_BAT_SENSE_E19") (pintype "bidirectional"))
    )
    (net (code "20") (name "/BO1") (class "Default")
      (node (ref "K1") (pin "2") (pinfunction "2_2") (pintype "passive"))
      (node (ref "R171") (pin "2") (pinfunction "2_2") (pintype "passive"))
      (node (ref "X8") (pin "10") (pinfunction "10_10") (pintype "bidirectional"))
    )
    (net (code "21") (name "/BO1_AUTO") (class "Default")
      (node (ref "IC2") (pin "16") (pinfunction "O1_16") (pintype "open_collector"))
      (node (ref "X8") (pin "9") (pinfunction "9_9") (pintype "bidirectional"))
    )
    (net (code "22") (name "/BO1_C") (class "Default")
      (node (ref "K1") (pin "C") (pinfunction "P_C") (pintype "passive"))
      (node (ref "X21") (pin "11") (pinfunction "SK_11") (pintype "passive"))
    )
    (net (code "23") (name "/BO1_NC") (class "Default")
      (node (ref "K1") (pin "NC") (pinfunction "O_NC") (pintype "passive"))
      (node (ref "X21") (pin "10") (pinfunction "SK_10") (pintype "passive"))
    )
    (net (code "24") (name "/BO1_NO") (class "Default")
      (node (ref "K1") (pin "NO") (pinfunction "S_NO") (pintype "passive"))
      (node (ref "X21") (pin "12") (pinfunction "SK_12") (pintype "passive"))
    )
    (net (code "25") (name "/BO2") (class "Default")
      (node (ref "K2") (pin "2") (pinfunction "2_2") (pintype "passive"))
      (node (ref "R172") (pin "2") (pinfunction "2_2") (pintype "passive"))
      (node (ref "X8") (pin "8") (pinfunction "8_8") (pintype "bidirectional"))
    )
    (net (code "26") (name "/BO2_AUTO") (class "Default")
      (node (ref "IC2") (pin "15") (pinfunction "O2_15") (pintype "open_collector"))
      (node (ref "X8") (pin "7") (pinfunction "7_7") (pintype "bidirectional"))
    )
    (net (code "27") (name "/BO2_C") (class "Default")
      (node (ref "K2") (pin "C") (pinfunction "P_C") (pintype "passive"))
      (node (ref "X21") (pin "8") (pinfunction "SK_8") (pintype "passive"))
    )
    (net (code "28") (name "/BO2_NC") (class "Default")
      (node (ref "K2") (pin "NC") (pinfunction "O_NC") (pintype "passive"))
      (node (ref "X21") (pin "7") (pinfunction "SK_7") (pintype "passive"))
    )
    (net (code "29") (name "/BO2_NO") (class "Default")
      (node (ref "K2") (pin "NO") (pinfunction "S_NO") (pintype "passive"))
      (node (ref "X21") (pin "9") (pinfunction "SK_9") (pintype "passive"))
    )
    (net (code "30") (name "/BO3") (class "Default")
      (node (ref "K3") (pin "2") (pinfunction "2_2") (pintype "passive"))
      (node (ref "R173") (pin "2") (pinfunction "2_2") (pintype "passive"))
      (node (ref "X8") (pin "6") (pinfunction "6_6") (pintype "bidirectional"))
    )
    (net (code "31") (name "/BO3_AUTO") (class "Default")
      (node (ref "IC2") (pin "14") (pinfunction "O3_14") (pintype "open_collector"))
      (node (ref "X8") (pin "5") (pinfunction "5_5") (pintype "bidirectional"))
    )
    (net (code "32") (name "/BO3_C") (class "Default")
      (node (ref "K3") (pin "C") (pinfunction "P_C") (pintype "passive"))
      (node (ref "X21") (pin "5") (pinfunction "SK_5") (pintype "passive"))
    )
    (net (code "33") (name "/BO3_NC") (class "Default")
      (node (ref "K3") (pin "NC") (pinfunction "O_NC") (pintype "passive"))
      (node (ref "X21") (pin "4") (pinfunction "SK_4") (pintype "passive"))
    )
    (net (code "34") (name "/BO4") (class "Default")
      (node (ref "K4") (pin "2") (pinfunction "2_2") (pintype "passive"))
      (node (ref "R174") (pin "2") (pinfunction "2_2") (pintype "passive"))
      (node (ref "X8") (pin "4") (pinfunction "4_4") (pintype "bidirectional"))
    )
    (net (code "35") (name "/BO4_AUTO") (class "Default")
      (node (ref "IC2") (pin "13") (pinfunction "O4_13") (pintype "open_collector"))
      (node (ref "X8") (pin "3") (pinfunction "3_3") (pintype "bidirectional"))
    )
    (net (code "36") (name "/BO4_C") (class "Default")
      (node (ref "K4") (pin "C") (pinfunction "P_C") (pintype "passive"))
      (node (ref "X21") (pin "2") (pinfunction "SK_2") (pintype "passive"))
    )
    (net (code "37") (name "/BO4_NC") (class "Default")
      (node (ref "K4") (pin "NC") (pinfunction "O_NC") (pintype "passive"))
      (node (ref "X21") (pin "1") (pinfunction "SK_1") (pintype "passive"))
    )
    (net (code "38") (name "/BO4_NO") (class "Default")
      (node (ref "K4") (pin "NO") (pinfunction "S_NO") (pintype "passive"))
      (node (ref "X21") (pin "3") (pinfunction "SK_3") (pintype "passive"))
    )
    (net (code "39") (name "/BO5_AUTO") (class "Default")
      (node (ref "IC2") (pin "12") (pinfunction "O5_12") (pintype "open_collector"))
      (node (ref "X8") (pin "1") (pinfunction "1_1") (pintype "bidirectional"))
    )
    (net (code "40") (name "/BO6_AUTO") (class "Default")
      (node (ref "IC2") (pin "11") (pinfunction "O6_11") (pintype "open_collector"))
      (node (ref "X8") (pin "12") (pinfunction "12_12") (pintype "bidirectional"))
    )
    (net (code "41") (name "/B_UART0_RX") (class "Default")
      (node (ref "R27") (pin "2") (pinfunction "2_2") (pintype "passive"))
      (node (ref "U6") (pin "2") (pinfunction "1A_2") (pintype "input"))
      (node (ref "X6") (pin "4") (pinfunction "4_4") (pintype "bidirectional"))
    )
    (net (code "42") (name "/B_UART0_TX") (class "Default")
      (node (ref "U6") (pin "3") (pinfunction "2Y_3") (pintype "output"))
      (node (ref "X6") (pin "5") (pinfunction "5_5") (pintype "bidirectional"))
    )
    (net (code "43") (name "/CAN1_RXD") (class "Default")
      (node (ref "D802") (pin "2") (pinfunction "C_2") (pintype "passive"))
      (node (ref "U1") (pin "W7") (pinfunction "UART1_TXD_W7") (pintype "bidirectional"))
      (node (ref "U28") (pin "4") (pinfunction "RXD_4") (pintype "output"))
    )
    (net (code "44") (name "/CAN1_TXD") (class "Default")
      (node (ref "D801") (pin "2") (pinfunction "C_2") (pintype "passive"))
      (node (ref "U1") (pin "Y7") (pinfunction "UART1_RXD_Y7") (pintype "bidirectional"))
      (node (ref "U28") (pin "1") (pinfunction "TXD_1") (pintype "input"))
    )
    (net (code "45") (name "/CAN_H") (class "Default")
      (node (ref "D805") (pin "2") (pinfunction "2_2") (pintype "passive"))
      (node (ref "U28") (pin "7") (pinfunction "CANH_7") (pintype "bidirectional"))
      (node (ref "X31") (pin "3") (pinfunction "SK_3") (pintype "passive"))
    )
    (net (code "46") (name "/CAN_L") (class "Default")
      (node (ref "D805") (pin "1") (pinfunction "1_1") (pintype "passive"))
      (node (ref "U28") (pin "6") (pinfunction "CANL_6") (pintype "bidirectional"))
      (node (ref "X31") (pin "2") (pinfunction "SK_2") (pintype "passive"))
    )
    (net (code "47") (name "/CLKOUT2") (class "Default")
      (node (ref "C2") (pin "2") (pinfunction "2_2") (pintype "passive"))
      (node (ref "R3") (pin "2") (pinfunction "2_2") (pintype "passive"))
      (node (ref "X4") (pin "18") (pinfunction "EMU3_18") (pintype "bidirectional"))
    )
    (net (code "48") (name "/CRS") (class "Default")
      (node (ref "ER124") (pin "1") (pinfunction "1_1") (pintype "passive"))
      (node (ref "U27") (pin "14") (pinfunction "CRS_14") (pintype "bidirectional"))
    )
    (net (code "49") (name "/EHRPWM1A") (class "Default")
      (node (ref "U1") (pin "C13") (pinfunction "GPMC_A2_C13") (pintype "bidirectional"))
      (node (ref "X8") (pin "15") (pinfunction "15_15") (pintype "bidirectional"))
    )
    (net (code "50") (name "/EHRPWM1B") (class "Default")
      (node (ref "U1") (pin "A12") (pinfunction "GPMC_A3_A12") (pintype "bidirectional"))
    )
    (net (code "51") (name "/EHRPWM2A") (class "Default")
      (node (ref "U1") (pin "A17") (pinfunction "GPMC_AD8_A17") (pintype "bidirectional"))
      (node (ref "X8") (pin "13") (pinfunction "13_13") (pintype "bidirectional"))
    )
    (net (code "52") (name "/EHRPWM2B") (class "Default")
      (node (ref "U1") (pin "C16") (pinfunction "GPMC_AD9_C16") (pintype "bidirectional"))
      (node (ref "X8") (pin "14") (pinfunction "14_14") (pintype "bidirectional"))
    )
    (net (code "53") (name "/E_LED_GRN") (class "Default")
      (node (ref "U27") (pin "3") (pinfunction "LED1/REGOFF_3") (pintype "bidirectional"))
      (node (ref "X2") (pin "9") (pinfunction "GRNA_9") (pintype "passive"))
    )
    (net (code "54") (name "/E_LED_YEL") (class "Default")
      (node (ref "ER120") (pin "2") (pinfunction "2_2") (pintype "passive"))
      (node (ref "U27") (pin "2") (pinfunction "LED2/~{INTSEL}_2") (pintype "bidirectional"))
      (node (ref "X2") (pin "12") (pinfunction "YELA_12") (pintype "passive"))
    )
    (net (code "55") (name "/GPIO0_7") (class "Default")
      (node (ref "U1") (pin "V15") (pinfunction "ECAP0_IN_PWM0_OUT_V15") (pintype "bidirectional"))
      (node (ref "U29") (pin "2") (pinfunction "~{RE}_2") (pintype "input"))
      (node (ref "U29") (pin "3") (pinfunction "DE_3") (pintype "input"))
    )
    (net (code "56") (name "/GPIO0_18") (class "Default")
      (node (ref "U1") (pin "K3") (pinfunction "USB0_DRVVBUS_K3") (pintype "bidirectional"))
    )
    (net (code "57") (name "/GPIO1_12") (class "Default")
      (node (ref "IC2") (pin "2") (pinfunction "I2_2") (pintype "input"))
      (node (ref "U1") (pin "C15") (pinfunction "GPMC_AD12_C15") (pintype "bidirectional"))
    )
    (net (code "58") (name "/GPIO1_13") (class "Default")
      (node (ref "IC2") (pin "3") (pinfunction "I3_3") (pintype "input"))
      (node (ref "U1") (pin "B15") (pinfunction "GPMC_AD13_B15") (pintype "bidirectional"))
    )
    (net (code "59") (name "/GPIO1_14") (class "Default")
      (node (ref "IC2") (pin "4") (pinfunction "I4_4") (pintype "input"))
      (node (ref "U1") (pin "A15") (pinfunction "GPMC_AD14_A15") (pintype "bidirectional"))
    )
    (net (code "60") (name "/GPIO1_15") (class "Default")
      (node (ref "IC2") (pin "5") (pinfunction "I5_5") (pintype "input"))
      (node (ref "U1") (pin "C14") (pinfunction "GPMC_AD15_C14") (pintype "bidirectional"))
    )
    (net (code "61") (name "/GPIO1_16") (class "Default")
      (node (ref "IC2") (pin "6") (pinfunction "I6_6") (pintype "input"))
      (node (ref "U1") (pin "A13") (pinfunction "GPMC_A0_A13") (pintype "bidirectional"))
    )
    (net (code "62") (name "/GPIO1_17") (class "Default")
      (node (ref "IC2") (pin "1") (pinfunction "I1_1") (pintype "input"))
      (node (ref "U1") (pin "B13") (pinfunction "GPMC_A1_B13") (pintype "bidirectional"))
    )
    (net (code "63") (name "/GPIO1_28") (class "Default")
      (node (ref "U1") (pin "C9") (pinfunction "GPMC_BEN1_C9") (pintype "bidirectional"))
    )
    (net (code "64") (name "/I2C0_SCL") (class "Default")
      (node (ref "R12") (pin "1") (pinfunction "1_1") (pintype "passive"))
      (node (ref "TP18") (pin "P$1") (pinfunction "TP_P$1") (pintype "bidirectional"))
      (node (ref "U1") (pin "U8") (pinfunction "PMIC_SCL_U8") (pintype "bidirectional"))
      (node (ref "U1") (pin "V8") (pinfunction "I2C0_SCL_V8") (pintype "bidirectional"))
      (node (ref "U16") (pin "29") (pinfunction "SM_CLK_29") (pintype "bidirectional"))
    )
    (net (code "65") (name "/I2C0_SDA") (class "Default")
      (node (ref "R13") (pin "1") (pinfunction "1_1") (pintype "passive"))
      (node (ref "TP17") (pin "P$1") (pinfunction "TP_P$1") (pintype "bidirectional"))
      (node (ref "U1") (pin "U7") (pinfunction "PMIC_SDA_U7") (pintype "bidirectional"))
      (node (ref "U1") (pin "V7") (pinfunction "I2C0_SDA_V7") (pintype "bidirectional"))
      (node (ref "U16") (pin "30") (pinfunction "SM_DAT_30") (pintype "bidirectional"))
    )
    (net (code "66") (name "/I2C2_SCL") (class "Default")
      (node (ref "R169") (pin "1") (pinfunction "1_1") (pintype "passive"))
      (node (ref "R901") (pin "1") (pinfunction "1_1") (pintype "passive"))
      (node (ref "RTC1") (pin "8") (pinfunction "SCL_8") (pintype "bidirectional"))
      (node (ref "TP20") (pin "P$1") (pinfunction "TP_P$1") (pintype "bidirectional"))
      (node (ref "U1") (pin "Y8") (pinfunction "UART1_RTSN_Y8") (pintype "bidirectional"))
      (node (ref "X9") (pin "P$4") (pinfunction "4_P$4") (pintype "passive"))
    )
    (net (code "67") (name "/I2C2_SDA") (class "Default")
      (node (ref "R170") (pin "1") (pinfunction "1_1") (pintype "passive"))
      (node (ref "R902") (pin "1") (pinfunction "1_1") (pintype "passive"))
      (node (ref "RTC1") (pin "7") (pinfunction "SDA_7") (pintype "bidirectional"))
      (node (ref "TP19") (pin "P$1") (pinfunction "TP_P$1") (pintype "bidirectional"))
      (node (ref "U1") (pin "W8") (pinfunction "UART1_CTSN_W8") (pintype "bidirectional"))
      (node (ref "X9") (pin "P$1") (pinfunction "1_P$1") (pintype "passive"))
    )
    (net (code "68") (name "/ISO_485_A") (class "Default")
      (node (ref "D405") (pin "2") (pinfunction "2_2") (pintype "passive"))
      (node (ref "F402") (pin "3") (pinfunction "3_3") (pintype "passive"))
      (node (ref "U40") (pin "11") (pinfunction "Y_11") (pintype "passive"))
      (node (ref "U40") (pin "14") (pinfunction "A_14") (pintype "passive"))
    )
    (net (code "69") (name "/ISO_485_B") (class "Default")
      (node (ref "D405") (pin "1") (pinfunction "1_1") (pintype "passive"))
      (node (ref "F401") (pin "3") (pinfunction "3_3") (pintype "passive"))
      (node (ref "U40") (pin "12") (pinfunction "Z_12") (pintype "passive"))
      (node (ref "U40") (pin "13") (pinfunction "B_13") (pintype "passive"))
    )
    (net (code "70") (name "/ISO_VCC") (class "Default")
      (node (ref "C402") (pin "1") (pinfunction "1_1") (pintype "passive"))
      (node (ref "C406") (pin "+") (pinfunction "+_+") (pintype "passive"))
      (node (ref "U40") (pin "16") (pinfunction "VCC2_16") (pintype "power_in"))
      (node (ref "VREG4") (pin "5") (pinfunction "VOUT_5") (pintype "output"))
    )
    (net (code "71") (name "/ISO_VIN") (class "Default")
      (node (ref "C403") (pin "1") (pinfunction "1_1") (pintype "passive"))
      (node (ref "C405") (pin "1") (pinfunction "1_1") (pintype "passive"))
      (node (ref "D403") (pin "C") (pinfunction "C_C") (pintype "passive"))
      (node (ref "D404") (pin "C") (pinfunction "C_C") (pintype "passive"))
      (node (ref "VREG4") (pin "1") (pinfunction "VIN_1") (pintype "input"))
      (node (ref "VREG4") (pin "3") (pinfunction "ON/~{OFF}_3") (pintype "passive"))
    )
    (net (code "72") (name "/JTAG_EMU0") (class "Default")
      (node (ref "R40") (pin "1") (pinfunction "1_1") (pintype "passive"))
      (node (ref "U1") (pin "V18") (pinfunction "EMU0_V18") (pintype "bidirectional"))
      (node (ref "X4") (pin "13") (pinfunction "EMU0_13") (pintype "bidirectional"))
    )
    (net (code "73") (name "/JTAG_EMU1") (class "Default")
      (node (ref "R41") (pin "1") (pinfunction "1_1") (pintype "passive"))
      (node (ref "U1") (pin "V19") (pinfunction "EMU1_V19") (pintype "bidirectional"))
      (node (ref "X4") (pin "14") (pinfunction "EMU1_14") (pintype "bidirectional"))
    )
    (net (code "74") (name "/JTAG_TCK") (class "Default")
      (node (ref "U1") (pin "Y19") (pinfunction "TCK_Y19") (pintype "bidirectional"))
      (node (ref "X4") (pin "11") (pinfunction "TCK_11") (pintype "bidirectional"))
      (node (ref "X4") (pin "9") (pinfunction "TCKRTN_9") (pintype "bidirectional"))
    )
    (net (code "75") (name "/JTAG_TDI") (class "Default")
      (node (ref "U1") (pin "Y18") (pinfunction "TDI_Y18") (pintype "bidirectional"))
      (node (ref "X4") (pin "3") (pinfunction "TDI_3") (pintype "bidirectional"))
    )
    (net (code "76") (name "/JTAG_TDO") (class "Default")
      (node (ref "U1") (pin "W18") (pinfunction "TDO_W18") (pintype "bidirectional"))
      (node (ref "X4") (pin "7") (pinfunction "TDO_7") (pintype "bidirectional"))
    )
    (net (code "77") (name "/JTAG_TMS") (class "Default")
      (node (ref "U1") (pin "W19") (pinfunction "TMS_W19") (pintype "bidirectional"))
      (node (ref "X4") (pin "1") (pinfunction "TMS_1") (pintype "bidirectional"))
    )
    (net (code "78") (name "/JTAG_TRSTN") (class "Default")
      (node (ref "R39") (pin "2") (pinfunction "2_2") (pintype "passive"))
      (node (ref "U1") (pin "W20") (pinfunction "TRSTN_W20") (pintype "bidirectional"))
      (node (ref "X4") (pin "2") (pinfunction "TRSTN_2") (pintype "bidirectional"))
    )
    (net (code "79") (name "/LCD_DATA0") (class "Default")
      (node (ref "R68") (pin "2") (pinfunction "2_2") (pintype "passive"))
      (node (ref "R85") (pin "1") (pinfunction "1_1") (pintype "passive"))
      (node (ref "U1") (pin "T18") (pinfunction "LCD_DATA0_T18") (pintype "bidirectional"))
      (node (ref "X7") (pin "19") (pinfunction "19_19") (pintype "bidirectional"))
    )
    (net (code "80") (name "/LCD_DATA1") (class "Default")
      (node (ref "R67") (pin "2") (pinfunction "2_2") (pintype "passive"))
      (node (ref "R84") (pin "1") (pinfunction "1_1") (pintype "passive"))
      (node (ref "U1") (pin "T19") (pinfunction "LCD_DATA1_T19") (pintype "bidirectional"))
      (node (ref "X7") (pin "20") (pinfunction "20_20") (pintype "bidirectional"))
    )
    (net (code "81") (name "/LCD_DATA2") (class "Default")
      (node (ref "R66") (pin "2") (pinfunction "2_2") (pintype "passive"))
      (node (ref "R69") (pin "1") (pinfunction "1_1") (pintype "passive"))
      (node (ref "R83") (pin "1") (pinfunction "1_1") (pintype "passive"))
      (node (ref "U1") (pin "T20") (pinfunction "LCD_DATA2_T20") (pintype "bidirectional"))
      (node (ref "X7") (pin "17") (pinfunction "17_17") (pintype "bidirectional"))
    )
    (net (code "82") (name "/LCD_DATA3") (class "Default")
      (node (ref "R65") (pin "2") (pinfunction "2_2") (pintype "passive"))
      (node (ref "R82") (pin "1") (pinfunction "1_1") (pintype "passive"))
      (node (ref "U1") (pin "R18") (pinfunction "LCD_DATA3_R18") (pintype "bidirectional"))
      (node (ref "X7") (pin "18") (pinfunction "18_18") (pintype "bidirectional"))
    )
    (net (code "83") (name "/LCD_DATA4") (class "Default")
      (node (ref "R64") (pin "2") (pinfunction "2_2") (pintype "passive"))
      (node (ref "R81") (pin "1") (pinfunction "1_1") (pintype "passive"))
      (node (ref "U1") (pin "R19") (pinfunction "LCD_DATA4_R19") (pintype "bidirectional"))
      (node (ref "X7") (pin "15") (pinfunction "15_15") (pintype "bidirectional"))
    )
    (net (code "84") (name "/LCD_DATA5") (class "Default")
      (node (ref "R63") (pin "2") (pinfunction "2_2") (pintype "passive"))
      (node (ref "R80") (pin "1") (pinfunction "1_1") (pintype "passive"))
      (node (ref "U1") (pin "R20") (pinfunction "LCD_DATA5_R20") (pintype "bidirectional"))
      (node (ref "X7") (pin "16") (pinfunction "16_16") (pintype "bidirectional"))
    )
    (net (code "85") (name "/LCD_DATA6") (class "Default")
      (node (ref "R62") (pin "2") (pinfunction "2_2") (pintype "passive"))
      (node (ref "R79") (pin "1") (pinfunction "1_1") (pintype "passive"))
      (node (ref "U1") (pin "P18") (pinfunction "LCD_DATA6_P18") (pintype "bidirectional"))
      (node (ref "X7") (pin "13") (pinfunction "13_13") (pintype "bidirectional"))
    )
    (net (code "86") (name "/LCD_DATA7") (class "Default")
      (node (ref "R61") (pin "2") (pinfunction "2_2") (pintype "passive"))
      (node (ref "R78") (pin "1") (pinfunction "1_1") (pintype "passive"))
      (node (ref "U1") (pin "P19") (pinfunction "LCD_DATA7_P19") (pintype "bidirectional"))
      (node (ref "X7") (pin "14") (pinfunction "14_14") (pintype "bidirectional"))
    )
    (net (code "87") (name "/LCD_DATA8") (class "Default")
      (node (ref "R60") (pin "2") (pinfunction "2_2") (pintype "passive"))
      (node (ref "R77") (pin "1") (pinfunction "1_1") (pintype "passive"))
      (node (ref "U1") (pin "P20") (pinfunction "LCD_DATA8_P20") (pintype "bidirectional"))
      (node (ref "X7") (pin "11") (pinfunction "11_11") (pintype "bidirectional"))
    )
    (net (code "88") (name "/LCD_DATA9") (class "Default")
      (node (ref "R59") (pin "2") (pinfunction "2_2") (pintype "passive"))
      (node (ref "R76") (pin "1") (pinfunction "1_1") (pintype "passive"))
      (node (ref "U1") (pin "N18") (pinfunction "LCD_DATA9_N18") (pintype "bidirectional"))
      (node (ref "X7") (pin "12") (pinfunction "12_12") (pintype "bidirectional"))
    )
    (net (code "89") (name "/LCD_DATA10") (class "Default")
      (node (ref "R58") (pin "2") (pinfunction "2_2") (pintype "passive"))
      (node (ref "R75") (pin "1") (pinfunction "1_1") (pintype "passive"))
      (node (ref "U1") (pin "N19") (pinfunction "LCD_DATA10_N19") (pintype "bidirectional"))
      (node (ref "X7") (pin "10") (pinfunction "10_10") (pintype "bidirectional"))
    )
    (net (code "90") (name "/LCD_DATA11") (class "Default")
      (node (ref "R57") (pin "2") (pinfunction "2_2") (pintype "passive"))
      (node (ref "R74") (pin "1") (pinfunction "1_1") (pintype "passive"))
      (node (ref "U1") (pin "N20") (pinfunction "LCD_DATA11_N20") (pintype "bidirectional"))
      (node (ref "X7") (pin "8") (pinfunction "8_8") (pintype "bidirectional"))
    )
    (net (code "91") (name "/LCD_DATA12") (class "Default")
      (node (ref "R56") (pin "2") (pinfunction "2_2") (pintype "passive"))
      (node (ref "R73") (pin "1") (pinfunction "1_1") (pintype "passive"))
      (node (ref "U1") (pin "M18") (pinfunction "LCD_DATA12_M18") (pintype "bidirectional"))
      (node (ref "X7") (pin "9") (pinfunction "9_9") (pintype "bidirectional"))
    )
    (net (code "92") (name "/LCD_DATA13") (class "Default")
      (node (ref "R55") (pin "2") (pinfunction "2_2") (pintype "passive"))
      (node (ref "R72") (pin "1") (pinfunction "1_1") (pintype "passive"))
      (node (ref "U1") (pin "M19") (pinfunction "LCD_DATA13_M19") (pintype "bidirectional"))
      (node (ref "X7") (pin "7") (pinfunction "7_7") (pintype "bidirectional"))
    )
    (net (code "93") (name "/LCD_DATA14") (class "Default")
      (node (ref "R54") (pin "2") (pinfunction "2_2") (pintype "passive"))
      (node (ref "R71") (pin "1") (pinfunction "1_1") (pintype "passive"))
      (node (ref "U1") (pin "M20") (pinfunction "LCD_DATA14_M20") (pintype "bidirectional"))
      (node (ref "X7") (pin "5") (pinfunction "5_5") (pintype "bidirectional"))
    )
    (net (code "94") (name "/LCD_DATA15") (class "Default")
      (node (ref "R53") (pin "2") (pinfunction "2_2") (pintype "passive"))
      (node (ref "R70") (pin "1") (pinfunction "1_1") (pintype "passive"))
      (node (ref "U1") (pin "L18") (pinfunction "LCD_DATA15_L18") (pintype "bidirectional"))
      (node (ref "X7") (pin "6") (pinfunction "6_6") (pintype "bidirectional"))
    )
    (net (code "95") (name "/LCD_DE") (class "Default")
      (node (ref "R28") (pin "2") (pinfunction "2_2") (pintype "passive"))
      (node (ref "X7") (pin "4") (pinfunction "4_4") (pintype "bidirectional"))
    )
    (net (code "96") (name "/LCD_HSYNC") (class "Default")
      (node (ref "R29") (pin "2") (pinfunction "2_2") (pintype "passive"))
      (node (ref "X7") (pin "3") (pinfunction "3_3") (pintype "bidirectional"))
    )
    (net (code "97") (name "/LCD_PCLK") (class "Default")
      (node (ref "R31") (pin "2") (pinfunction "2_2") (pintype "passive"))
      (node (ref "X7") (pin "2") (pinfunction "2_2") (pintype "bidirectional"))
    )
    (net (code "98") (name "/LCD_VSYNC") (class "Default")
      (node (ref "R30") (pin "2") (pinfunction "2_2") (pintype "passive"))
      (node (ref "X7") (pin "1") (pinfunction "1_1") (pintype "bidirectional"))
    )
    (net (code "99") (name "/LDO_PGOOD") (class "Default")
      (node (ref "TP22") (pin "TP") (pinfunction "TP_TP") (pintype "input"))
      (node (ref "U1") (pin "D13") (pinfunction "RTC_PWRONRSTN_D13") (pintype "bidirectional"))
      (node (ref "U1") (pin "D14") (pinfunction "PMIC_LDO_PGOOD_D14") (pintype "output"))
    )
    (net (code "100") (name "/MDIO_CLK") (class "Default")
      (node (ref "U1") (pin "W1") (pinfunction "MDC_W1") (pintype "bidirectional"))
      (node (ref "U27") (pin "17") (pinfunction "MDC_17") (pintype "input"))
    )
    (net (code "101") (name "/MDIO_DATA") (class "Default")
      (node (ref "ER105") (pin "2") (pinfunction "2_2") (pintype "passive"))
      (node (ref "U1") (pin "V1") (pinfunction "MDIO_V1") (pintype "bidirectional"))
      (node (ref "U27") (pin "16") (pinfunction "MDIO_16") (pintype "bidirectional"))
    )
    (net (code "102") (name "/MII1_COL") (class "Default")
      (node (ref "ER123") (pin "2") (pinfunction "2_2") (pintype "passive"))
      (node (ref "U1") (pin "R2") (pinfunction "MII1_COL_R2") (pintype "bidirectional"))
    )
    (net (code "103") (name "/MII1_CRS") (class "Default")
      (node (ref "ER124") (pin "2") (pinfunction "2_2") (pintype "passive"))
      (node (ref "U1") (pin "R3") (pinfunction "MII1_CRS_R3") (pintype "bidirectional"))
    )
    (net (code "104") (name "/MII1_RXCLK") (class "Default")
      (node (ref "ER116") (pin "2") (pinfunction "2_2") (pintype "passive"))
      (node (ref "U1") (pin "T1") (pinfunction "MII1_RX_CLK_T1") (pintype "bidirectional"))
    )
    (net (code "105") (name "/MII1_RXD0") (class "Default")
      (node (ref "ER113") (pin "2") (pinfunction "2_2") (pintype "passive"))
      (node (ref "U1") (pin "T3") (pinfunction "MII1_RXD0_T3") (pintype "bidirectional"))
    )
    (net (code "106") (name "/MII1_RXD1") (class "Default")
      (node (ref "ER112") (pin "2") (pinfunction "2_2") (pintype "passive"))
      (node (ref "U1") (pin "U1") (pinfunction "MII1_RXD1_U1") (pintype "bidirectional"))
    )
    (net (code "107") (name "/MII1_RXD2") (class "Default")
      (node (ref "ER111") (pin "2") (pinfunction "2_2") (pintype "passive"))
      (node (ref "U1") (pin "U2") (pinfunction "MII1_RXD2_U2") (pintype "bidirectional"))
    )
    (net (code "108") (name "/MII1_RXD3") (class "Default")
      (node (ref "ER110") (pin "2") (pinfunction "2_2") (pintype "passive"))
      (node (ref "U1") (pin "U3") (pinfunction "MII1_RXD3_U3") (pintype "bidirectional"))
    )
    (net (code "109") (name "/MII1_RXDV") (class "Default")
      (node (ref "ER114") (pin "2") (pinfunction "2_2") (pintype "passive"))
      (node (ref "U1") (pin "R1") (pinfunction "MII1_RX_DV_R1") (pintype "bidirectional"))
    )
    (net (code "110") (name "/MII1_RXERR") (class "Default")
      (node (ref "ER118") (pin "2") (pinfunction "2_2") (pintype "passive"))
      (node (ref "U1") (pin "T2") (pinfunction "MII1_RX_ER_T2") (pintype "bidirectional"))
    )
    (net (code "111") (name "/MII1_TXCLK") (class "Default")
      (node (ref "ER119") (pin "2") (pinfunction "2_2") (pintype "passive"))
      (node (ref "U1") (pin "N1") (pinfunction "MII1_TX_CLK_N1") (pintype "bidirectional"))
    )
    (net (code "112") (name "/MII1_TXD0") (class "Default")
      (node (ref "U1") (pin "N2") (pinfunction "MII1_TXD0_N2") (pintype "bidirectional"))
      (node (ref "U27") (pin "22") (pinfunction "TXD0_22") (pintype "input"))
    )
    (net (code "113") (name "/MII1_TXD1") (class "Default")
      (node (ref "U1") (pin "N3") (pinfunction "MII1_TXD1_N3") (pintype "bidirectional"))
      (node (ref "U27") (pin "23") (pinfunction "TXD1_23") (pintype "input"))
    )
    (net (code "114") (name "/MII1_TXD2") (class "Default")
      (node (ref "U1") (pin "P1") (pinfunction "MII1_TXD2_P1") (pintype "bidirectional"))
      (node (ref "U27") (pin "24") (pinfunction "TXD2_24") (pintype "input"))
    )
    (net (code "115") (name "/MII1_TXD3") (class "Default")
      (node (ref "U1") (pin "P2") (pinfunction "MII1_TXD3_P2") (pintype "bidirectional"))
      (node (ref "U27") (pin "25") (pinfunction "TXD3_25") (pintype "input"))
    )
    (net (code "116") (name "/MII1_TXEN") (class "Default")
      (node (ref "U1") (pin "P3") (pinfunction "MII1_TX_EN_P3") (pintype "bidirectional"))
      (node (ref "U27") (pin "21") (pinfunction "TXEN_21") (pintype "input"))
    )
    (net (code "117") (name "/MMC0_CD") (class "Default")
      (node (ref "R92") (pin "1") (pinfunction "1_1") (pintype "passive"))
      (node (ref "U1") (pin "V4") (pinfunction "SPI0_CS1_V4") (pintype "bidirectional"))
      (node (ref "X4") (pin "19") (pinfunction "EMU4_19") (pintype "bidirectional"))
      (node (ref "X5") (pin "12") (pinfunction "CARD_DETECTION_SWITCH_12") (pintype "bidirectional"))
    )
    (net (code "118") (name "/MMC0_CLK") (class "Default")
      (node (ref "R88") (pin "1") (pinfunction "1_1") (pintype "passive"))
      (node (ref "U1") (pin "W3") (pinfunction "MMC0_CLK_W3") (pintype "bidirectional"))
      (node (ref "X5") (pin "5") (pinfunction "CLK_5") (pintype "bidirectional"))
    )
    (net (code "119") (name "/MMC0_CMD") (class "Default")
      (node (ref "R87") (pin "1") (pinfunction "1_1") (pintype "passive"))
      (node (ref "U1") (pin "W2") (pinfunction "MMC0_CMD_W2") (pintype "bidirectional"))
      (node (ref "X5") (pin "3") (pinfunction "CMD_3") (pintype "bidirectional"))
    )
    (net (code "120") (name "/MMC0_DAT0") (class "Default")
      (node (ref "R89") (pin "1") (pinfunction "1_1") (pintype "passive"))
      (node (ref "U1") (pin "Y3") (pinfunction "MMC0_DAT0_Y3") (pintype "bidirectional"))
      (node (ref "X5") (pin "7") (pinfunction "DAT0_7") (pintype "bidirectional"))
    )
    (net (code "121") (name "/MMC0_DAT1") (class "Default")
      (node (ref "R90") (pin "1") (pinfunction "1_1") (pintype "passive"))
      (node (ref "U1") (pin "V3") (pinfunction "MMC0_DAT1_V3") (pintype "bidirectional"))
      (node (ref "X5") (pin "8") (pinfunction "DAT1_8") (pintype "bidirectional"))
    )
    (net (code "122") (name "/MMC0_DAT2") (class "Default")
      (node (ref "R86") (pin "1") (pinfunction "1_1") (pintype "passive"))
      (node (ref "U1") (pin "V2") (pinfunction "MMC0_DAT2_V2") (pintype "bidirectional"))
      (node (ref "X5") (pin "1") (pinfunction "DAT2_1") (pintype "bidirectional"))
    )
    (net (code "123") (name "/MMC0_DAT3") (class "Default")
      (node (ref "R91") (pin "1") (pinfunction "1_1") (pintype "passive"))
      (node (ref "U1") (pin "Y2") (pinfunction "MMC0_DAT3_Y2") (pintype "bidirectional"))
      (node (ref "X5") (pin "2") (pinfunction "CD/DAT3_2") (pintype "bidirectional"))
    )
    (net (code "124") (name "/MODE2") (class "Default")
      (node (ref "ER123") (pin "1") (pinfunction "1_1") (pintype "passive"))
      (node (ref "ER99") (pin "2") (pinfunction "2_2") (pintype "passive"))
      (node (ref "U27") (pin "15") (pinfunction "COL/CRS_DV/MODE2_15") (pintype "bidirectional"))
    )
    (net (code "125") (name "/OSC1_IN") (class "Default")
      (node (ref "R164") (pin "2") (pinfunction "2_2") (pintype "passive"))
      (node (ref "RTC1") (pin "1") (pinfunction "32KHZ_1") (pintype "output"))
      (node (ref "U1") (pin "Y13") (pinfunction "OSC1_IN_Y13") (pintype "bidirectional"))
    )
    (net (code "126") (name "/OSC1_OUT") (class "Default")
      (node (ref "U1") (pin "Y14") (pinfunction "OSC1_OUT_Y14") (pintype "bidirectional"))
    )
    (net (code "127") (name "/OSC_CTL") (class "Default")
      (node (ref "TP32") (pin "TP") (pinfunction "TP_TP") (pintype "input"))
      (node (ref "U1") (pin "M1") (pinfunction "OSC0_CTL_M1") (pintype "bidirectional"))
    )
    (net (code "128") (name "/PMIC_INT") (class "Default")
      (node (ref "TP24") (pin "TP") (pinfunction "TP_TP") (pintype "input"))
      (node (ref "U1") (pin "J17") (pinfunction "PMIC_NINT_J17") (pintype "output"))
      (node (ref "U1") (pin "K17") (pinfunction "EXTINTN_K17") (pintype "bidirectional"))
    )
    (net (code "129") (name "/PMIC_MUX_IN") (class "Default")
      (node (ref "R18") (pin "2") (pinfunction "2_2") (pintype "passive"))
      (node (ref "R22") (pin "1") (pinfunction "1_1") (pintype "passive"))
      (node (ref "U1") (pin "F19") (pinfunction "PMIC_MUX_IN_F19") (pintype "bidirectional"))
    )
    (net (code "130") (name "/PMIC_NRESET") (class "Default")
      (node (ref "U1") (pin "A19") (pinfunction "PMIC_NRESET_A19") (pintype "bidirectional"))
      (node (ref "X8") (pin "18") (pinfunction "18_18") (pintype "bidirectional"))
    )
    (net (code "131") (name "/PMIC_NWAKEUP") (class "Default")
      (node (ref "TP23") (pin "TP") (pinfunction "TP_TP") (pintype "input"))
      (node (ref "U1") (pin "G17") (pinfunction "PMIC_NWAKEUP_G17") (pintype "output"))
      (node (ref "U1") (pin "H17") (pinfunction "EXT_WAKEUP_H17") (pintype "bidirectional"))
    )
    (net (code "132") (name "/PMIC_PGOOD") (class "Default")
      (node (ref "TP26") (pin "TP") (pinfunction "TP_TP") (pintype "input"))
      (node (ref "U1") (pin "D11") (pinfunction "PWRONRSTN_D11") (pintype "bidirectional"))
      (node (ref "U1") (pin "D12") (pinfunction "PMIC_PGOOD_D12") (pintype "output"))
    )
    (net (code "133") (name "/PR1_PRU0_PRU_R30_6") (class "Default")
      (node (ref "U1") (pin "V17") (pinfunction "MCASP0_AXR1_V17") (pintype "bidirectional"))
      (node (ref "U40") (pin "6") (pinfunction "~{RE}_6") (pintype "passive"))
    )
    (net (code "134") (name "/PR1_PRU0_PRU_R30_7") (class "Default")
      (node (ref "U1") (pin "V16") (pinfunction "MCASP0_AHCLKX_V16") (pintype "bidirectional"))
      (node (ref "U40") (pin "7") (pinfunction "DE_7") (pintype "passive"))
    )
    (net (code "135") (name "/PR1_UART0_RXD") (class "Default")
      (node (ref "J450") (pin "1") (pinfunction "1_1") (pintype "bidirectional"))
      (node (ref "U1") (pin "W4") (pinfunction "SPI0_D1_W4") (pintype "bidirectional"))
    )
    (net (code "136") (name "/PR1_UART0_TXD") (class "Default")
      (node (ref "J450") (pin "2") (pinfunction "2_2") (pintype "bidirectional"))
      (node (ref "U1") (pin "Y4") (pinfunction "SPI0_CS0_Y4") (pintype "bidirectional"))
    )
    (net (code "137") (name "/PWR_BUT") (class "Default")
      (node (ref "S2") (pin "2") (pinfunction "2_2") (pintype "bidirectional"))
      (node (ref "S2") (pin "4") (pinfunction "4_4") (pintype "bidirectional"))
      (node (ref "U1") (pin "A18") (pinfunction "PMIC_PB_IN_A18") (pintype "bidirectional"))
    )
    (net (code "138") (name "/PWR_EN") (class "Default")
      (node (ref "TP21") (pin "TP") (pinfunction "TP_TP") (pintype "input"))
      (node (ref "U1") (pin "D10") (pinfunction "PMIC_PWR_EN_D10") (pintype "input"))
      (node (ref "U1") (pin "D9") (pinfunction "PMIC_POWER_EN_D9") (pintype "output"))
    )
    (net (code "139") (name "/RTC_RST") (class "Default")
      (node (ref "R163") (pin "1") (pinfunction "1_1") (pintype "passive"))
      (node (ref "RTC1") (pin "4") (pinfunction "RST_4") (pintype "bidirectional"))
      (node (ref "U1") (pin "K20") (pinfunction "GPMC_CSN0_K20") (pintype "bidirectional"))
    )
    (net (code "140") (name "/RXD0") (class "Default")
      (node (ref "ER113") (pin "1") (pinfunction "1_1") (pintype "passive"))
      (node (ref "ER98") (pin "2") (pinfunction "2_2") (pintype "passive"))
      (node (ref "U27") (pin "11") (pinfunction "RXD0/MODE0_11") (pintype "bidirectional"))
    )
    (net (code "141") (name "/RXD1") (class "Default")
      (node (ref "ER100") (pin "2") (pinfunction "2_2") (pintype "passive"))
      (node (ref "ER112") (pin "1") (pinfunction "1_1") (pintype "passive"))
      (node (ref "U27") (pin "10") (pinfunction "RXD1/MODE1_10") (pintype "bidirectional"))
    )
    (net (code "142") (name "/RXD2") (class "Default")
      (node (ref "ER103") (pin "1") (pinfunction "1_1") (pintype "passive"))
      (node (ref "ER111") (pin "1") (pinfunction "1_1") (pintype "passive"))
      (node (ref "U27") (pin "9") (pinfunction "RXD2/RMIISEL_9") (pintype "bidirectional"))
    )
    (net (code "143") (name "/RXD3") (class "Default")
      (node (ref "ER102") (pin "1") (pinfunction "1_1") (pintype "passive"))
      (node (ref "ER110") (pin "1") (pinfunction "1_1") (pintype "passive"))
      (node (ref "U27") (pin "8") (pinfunction "RXD3/PHYAD2_8") (pintype "bidirectional"))
    )
    (net (code "144") (name "/RX_CLK") (class "Default")
      (node (ref "ER104") (pin "1") (pinfunction "1_1") (pintype "passive"))
      (node (ref "ER116") (pin "1") (pinfunction "1_1") (pintype "passive"))
      (node (ref "U27") (pin "7") (pinfunction "RXCLK/PHYAD1_7") (pintype "bidirectional"))
    )
    (net (code "145") (name "/RX_DV") (class "Default")
      (node (ref "ER114") (pin "1") (pinfunction "1_1") (pintype "passive"))
      (node (ref "U27") (pin "26") (pinfunction "RXDV_26") (pintype "bidirectional"))
    )
    (net (code "146") (name "/RX_ERR") (class "Default")
      (node (ref "ER101") (pin "1") (pinfunction "1_1") (pintype "passive"))
      (node (ref "ER118") (pin "1") (pinfunction "1_1") (pintype "passive"))
      (node (ref "U27") (pin "13") (pinfunction "RXER/RXD4/PHYAD0_13") (pintype "bidirectional"))
    )
    (net (code "147") (name "/RX_N") (class "Default")
      (node (ref "EC37") (pin "1") (pinfunction "1_1") (pintype "passive"))
      (node (ref "ER107") (pin "2") (pinfunction "2_2") (pintype "passive"))
      (node (ref "U27") (pin "30") (pinfunction "RXN_30") (pintype "bidirectional"))
      (node (ref "X2") (pin "6") (pinfunction "RXN_6") (pintype "passive"))
    )
    (net (code "148") (name "/RX_P") (class "Default")
      (node (ref "EC36") (pin "1") (pinfunction "1_1") (pintype "passive"))
      (node (ref "ER106") (pin "2") (pinfunction "2_2") (pintype "passive"))
      (node (ref "U27") (pin "31") (pinfunction "RXP_31") (pintype "bidirectional"))
      (node (ref "X2") (pin "3") (pinfunction "RXP_3") (pintype "passive"))
    )
    (net (code "149") (name "/SPI1_CS0") (class "Default")
      (node (ref "IC4") (pin "1") (pinfunction "SH/~{LD}_1") (pintype "input"))
      (node (ref "IC5") (pin "1") (pinfunction "SH/~{LD}_1") (pintype "input"))
      (node (ref "U1") (pin "W17") (pinfunction "MCASP0_AHCLKR_W17") (pintype "bidirectional"))
    )
    (net (code "150") (name "/SPI1_D0") (class "Default")
      (node (ref "IC4") (pin "9") (pinfunction "QH_9") (pintype "output"))
      (node (ref "U1") (pin "Y16") (pinfunction "MCASP0_FSX_Y16") (pintype "bidirectional"))
    )
    (net (code "151") (name "/SPI1_D1") (class "Default")
      (node (ref "U1") (pin "W16") (pinfunction "MCASP0_AXR0_W16") (pintype "bidirectional"))
    )
    (net (code "152") (name "/SPI1_SCLK") (class "Default")
      (node (ref "IC4") (pin "2") (pinfunction "CLK_2") (pintype "input"))
      (node (ref "IC5") (pin "2") (pinfunction "CLK_2") (pintype "input"))
      (node (ref "U1") (pin "Y17") (pinfunction "MCASP0_ACLKX_Y17") (pintype "bidirectional"))
    )
    (net (code "153") (name "/SYS_RESETN") (class "Default")
      (node (ref "C14") (pin "1") (pinfunction "1_1") (pintype "passive"))
      (node (ref "R6") (pin "2") (pinfunction "2_2") (pintype "passive"))
      (node (ref "R8") (pin "1") (pinfunction "1_1") (pintype "passive"))
      (node (ref "TP31") (pin "TP") (pinfunction "TP_TP") (pintype "input"))
      (node (ref "U1") (pin "B17") (pinfunction "WARMRSTN_B17") (pintype "bidirectional"))
      (node (ref "U16") (pin "17") (pinfunction "LRESET#_17") (pintype "bidirectional"))
      (node (ref "U27") (pin "19") (pinfunction "~{RST}_19") (pintype "bidirectional"))
      (node (ref "X4") (pin "15") (pinfunction "SRST_15") (pintype "bidirectional"))
    )
    (net (code "154") (name "/TEMP_SENSE") (class "Default")
      (node (ref "TP7") (pin "P$1") (pinfunction "TP_P$1") (pintype "bidirectional"))
      (node (ref "U1") (pin "E20") (pinfunction "PMIC_TS_E20") (pintype "bidirectional"))
    )
    (net (code "155") (name "/TPM_GPIO0") (class "Default")
      (node (ref "U1") (pin "W15") (pinfunction "MCASP0_FSR_W15") (pintype "bidirectional"))
      (node (ref "U16") (pin "12") (pinfunction "GPIO_12") (pintype "bidirectional"))
    )
    (net (code "156") (name "/TPM_GPIO1") (class "Default")
      (node (ref "TP9") (pin "P$1") (pinfunction "TP_P$1") (pintype "bidirectional"))
      (node (ref "U1") (pin "V6") (pinfunction "UART0_CTSN_V6") (pintype "bidirectional"))
      (node (ref "U16") (pin "3") (pinfunction "GPIO-EXPRESS-00_3") (pintype "bidirectional"))
    )
    (net (code "157") (name "/TPM_GPIO2") (class "Default")
      (node (ref "TP10") (pin "P$1") (pinfunction "TP_P$1") (pintype "bidirectional"))
      (node (ref "U1") (pin "V5") (pinfunction "UART0_RTSN_V5") (pintype "bidirectional"))
      (node (ref "U16") (pin "4") (pinfunction "PP/GPIO_4") (pintype "bidirectional"))
    )
    (net (code "158") (name "/TX_CLK") (class "Default")
      (node (ref "ER119") (pin "1") (pinfunction "1_1") (pintype "passive"))
      (node (ref "U27") (pin "20") (pinfunction "TXCLK_20") (pintype "bidirectional"))
    )
    (net (code "159") (name "/TX_N") (class "Default")
      (node (ref "EC39") (pin "1") (pinfunction "1_1") (pintype "passive"))
      (node (ref "ER109") (pin "2") (pinfunction "2_2") (pintype "passive"))
      (node (ref "U27") (pin "28") (pinfunction "TXN_28") (pintype "bidirectional"))
      (node (ref "X2") (pin "2") (pinfunction "TXN_2") (pintype "passive"))
    )
    (net (code "160") (name "/TX_P") (class "Default")
      (node (ref "EC38") (pin "1") (pinfunction "1_1") (pintype "passive"))
      (node (ref "ER108") (pin "2") (pinfunction "2_2") (pintype "passive"))
      (node (ref "U27") (pin "29") (pinfunction "TXP_29") (pintype "bidirectional"))
      (node (ref "X2") (pin "1") (pinfunction "TXP_1") (pintype "passive"))
    )
    (net (code "161") (name "/UART0_RX") (class "Default")
      (node (ref "U1") (pin "Y6") (pinfunction "UART0_RXD_Y6") (pintype "bidirectional"))
      (node (ref "U6") (pin "6") (pinfunction "1Y_6") (pintype "output"))
    )
    (net (code "162") (name "/UART0_TX") (class "Default")
      (node (ref "U1") (pin "W6") (pinfunction "UART0_TXD_W6") (pintype "bidirectional"))
      (node (ref "U6") (pin "5") (pinfunction "2A_5") (pintype "input"))
    )
    (net (code "163") (name "/UART2_RXD") (class "Default")
      (node (ref "D302") (pin "2") (pinfunction "C_2") (pintype "passive"))
      (node (ref "U1") (pin "Y5") (pinfunction "SPI0_SCLK_Y5") (pintype "bidirectional"))
      (node (ref "U29") (pin "1") (pinfunction "RO_1") (pintype "output"))
    )
    (net (code "164") (name "/UART2_TXD") (class "Default")
      (node (ref "D301") (pin "2") (pinfunction "C_2") (pintype "passive"))
      (node (ref "U1") (pin "W5") (pinfunction "SPI0_D0_W5") (pintype "bidirectional"))
      (node (ref "U29") (pin "4") (pinfunction "DI_4") (pintype "input"))
    )
    (net (code "165") (name "/UART4_RXD") (class "Default")
      (node (ref "J454") (pin "1") (pinfunction "1_1") (pintype "bidirectional"))
      (node (ref "U1") (pin "B9") (pinfunction "GPMC_WAIT0_B9") (pintype "bidirectional"))
    )
    (net (code "166") (name "/UART4_TXD") (class "Default")
      (node (ref "J454") (pin "2") (pinfunction "2_2") (pintype "bidirectional"))
      (node (ref "U1") (pin "A9") (pinfunction "GPMC_WPN_A9") (pintype "bidirectional"))
    )
    (net (code "167") (name "/USB0_ID") (class "Default")
      (node (ref "U1") (pin "L1") (pinfunction "USB0_ID_L1") (pintype "bidirectional"))
      (node (ref "U2") (pin "3") (pinfunction "ID_3") (pintype "passive"))
      (node (ref "X1") (pin "ID") (pinfunction "ID_ID") (pintype "input"))
    )
    (net (code "168") (name "/USB0_N") (class "Default")
      (node (ref "U1") (pin "K2") (pinfunction "USB0_DM_K2") (pintype "bidirectional"))
      (node (ref "U2") (pin "1") (pinfunction "D-_1") (pintype "passive"))
      (node (ref "X1") (pin "D-") (pinfunction "D-_D-") (pintype "input"))
    )
    (net (code "169") (name "/USB0_P") (class "Default")
      (node (ref "U1") (pin "L2") (pinfunction "USB0_DP_L2") (pintype "bidirectional"))
      (node (ref "U2") (pin "2") (pinfunction "D+_2") (pintype "passive"))
      (node (ref "X1") (pin "D+") (pinfunction "D+_D+") (pintype "input"))
    )
    (net (code "170") (name "/USR0") (class "Default")
      (node (ref "D7") (pin "1") (pinfunction "A_1") (pintype "passive"))
      (node (ref "U1") (pin "C12") (pinfunction "GPMC_A5_C12") (pintype "bidirectional"))
    )
    (net (code "171") (name "/USR1") (class "Default")
      (node (ref "D6") (pin "1") (pinfunction "A_1") (pintype "passive"))
      (node (ref "U1") (pin "A11") (pinfunction "GPMC_A6_A11") (pintype "bidirectional"))
    )
    (net (code "172") (name "/USR2") (class "Default")
      (node (ref "D5") (pin "1") (pinfunction "A_1") (pintype "passive"))
      (node (ref "U1") (pin "B11") (pinfunction "GPMC_A7_B11") (pintype "bidirectional"))
    )
    (net (code "173") (name "/USR3") (class "Default")
      (node (ref "D4") (pin "1") (pinfunction "A_1") (pintype "passive"))
      (node (ref "U1") (pin "C11") (pinfunction "GPMC_A8_C11") (pintype "bidirectional"))
    )
    (net (code "174") (name "/VDDS_DDR") (class "Default")
      (node (ref "TP2") (pin "TP") (pinfunction "TP_TP") (pintype "input"))
      (node (ref "U1") (pin "U9") (pinfunction "VDDS_DDR_U9") (pintype "bidirectional"))
    )
    (net (code "175") (name "/VDDS_PLL") (class "Default")
      (node (ref "TP3") (pin "TP") (pinfunction "TP_TP") (pintype "input"))
      (node (ref "U1") (pin "U10") (pinfunction "VDDS_PLL_U10") (pintype "bidirectional"))
    )
    (net (code "176") (name "/VDD_CORE") (class "Default")
      (node (ref "TP4") (pin "TP") (pinfunction "TP_TP") (pintype "input"))
      (node (ref "U1") (pin "U13") (pinfunction "VDD_CORE_U13") (pintype "bidirectional"))
    )
    (net (code "177") (name "/VDD_MPU") (class "Default")
      (node (ref "TP1") (pin "TP") (pinfunction "TP_TP") (pintype "input"))
      (node (ref "U1") (pin "U6") (pinfunction "VDD_MPU_U6") (pintype "bidirectional"))
    )
    (net (code "178") (name "/VREFN") (class "Default")
      (node (ref "R25") (pin "1") (pinfunction "1_1") (pintype "passive"))
      (node (ref "U1") (pin "W9") (pinfunction "VREFN_W9") (pintype "bidirectional"))
    )
    (net (code "179") (name "/VREFP") (class "Default")
      (node (ref "C8") (pin "1") (pinfunction "1_1") (pintype "passive"))
      (node (ref "C9") (pin "1") (pinfunction "1_1") (pintype "passive"))
      (node (ref "R33") (pin "1") (pinfunction "1_1") (pintype "passive"))
      (node (ref "U1") (pin "W12") (pinfunction "VREFP_W12") (pintype "bidirectional"))
    )
    (net (code "180") (name "/XDMA_EVENT_INTR0") (class "Default")
      (node (ref "C1") (pin "2") (pinfunction "2_2") (pintype "passive"))
      (node (ref "R4") (pin "2") (pinfunction "2_2") (pintype "passive"))
      (node (ref "X4") (pin "17") (pinfunction "EMU2_17") (pintype "bidirectional"))
    )
    (net (code "181") (name "24VDC_AUX") (class "Default")
      (node (ref "C106") (pin "1") (pinfunction "1_1") (pintype "passive"))
      (node (ref "D19") (pin "1") (pinfunction "A_1") (pintype "passive"))
      (node (ref "D31") (pin "1") (pinfunction "A_1") (pintype "passive"))
      (node (ref "D32") (pin "1") (pinfunction "A_1") (pintype "passive"))
      (node (ref "D33") (pin "1") (pinfunction "A_1") (pintype "passive"))
      (node (ref "D34") (pin "1") (pinfunction "A_1") (pintype "passive"))
      (node (ref "IC2") (pin "9") (pinfunction "CD+_9") (pintype "passive"))
      (node (ref "J24") (pin "3") (pinfunction "3_3") (pintype "bidirectional"))
      (node (ref "K1") (pin "1") (pinfunction "1_1") (pintype "passive"))
      (node (ref "K2") (pin "1") (pinfunction "1_1") (pintype "passive"))
      (node (ref "K3") (pin "1") (pinfunction "1_1") (pintype "passive"))
      (node (ref "K4") (pin "1") (pinfunction "1_1") (pintype "passive"))
      (node (ref "VREG2") (pin "OUT") (pinfunction "OUT_OUT") (pintype "passive"))
      (node (ref "X31") (pin "4") (pinfunction "SK_4") (pintype "passive"))
      (node (ref "X8") (pin "11") (pinfunction "11_11") (pintype "bidirectional"))
      (node (ref "X8") (pin "19") (pinfunction "19_19") (pintype "bidirectional"))
    )
    (net (code "182") (name "AGND") (class "Default")
      (node (ref "C10") (pin "2") (pinfunction "2_2") (pintype "passive"))
      (node (ref "C111") (pin "2") (pinfunction "2_2") (pintype "passive"))
      (node (ref "C121") (pin "2") (pinfunction "2_2") (pintype "passive"))
      (node (ref "C131") (pin "2") (pinfunction "2_2") (pintype "passive"))
      (node (ref "C141") (pin "2") (pinfunction "2_2") (pintype "passive"))
      (node (ref "C151") (pin "2") (pinfunction "2_2") (pintype "passive"))
      (node (ref "C161") (pin "2") (pinfunction "2_2") (pintype "passive"))
      (node (ref "C8") (pin "2") (pinfunction "2_2") (pintype "passive"))
      (node (ref "C9") (pin "2") (pinfunction "2_2") (pintype "passive"))
      (node (ref "IC10") (pin "4") (pinfunction "V-_4") (pintype "power_in"))
      (node (ref "IC11") (pin "4") (pinfunction "V-_4") (pintype "power_in"))
      (node (ref "IC12") (pin "4") (pinfunction "V-_4") (pintype "power_in"))
      (node (ref "J7") (pin "1") (pinfunction "1_1") (pintype "bidirectional"))
      (node (ref "R181") (pin "2") (pinfunction "2_2") (pintype "passive"))
      (node (ref "R182") (pin "2") (pinfunction "2_2") (pintype "passive"))
      (node (ref "R183") (pin "2") (pinfunction "2_2") (pintype "passive"))
      (node (ref "R184") (pin "2") (pinfunction "2_2") (pintype "passive"))
      (node (ref "R185") (pin "2") (pinfunction "2_2") (pintype "passive"))
      (node (ref "R186") (pin "2") (pinfunction "2_2") (pintype "passive"))
      (node (ref "R211") (pin "1") (pinfunction "1_1") (pintype "passive"))
      (node (ref "R213") (pin "2") (pinfunction "2_2") (pintype "passive"))
      (node (ref "R215") (pin "2") (pinfunction "2_2") (pintype "passive"))
      (node (ref "R221") (pin "1") (pinfunction "1_1") (pintype "passive"))
      (node (ref "R223") (pin "2") (pinfunction "2_2") (pintype "passive"))
      (node (ref "R225") (pin "2") (pinfunction "2_2") (pintype "passive"))
      (node (ref "R231") (pin "1") (pinfunction "1_1") (pintype "passive"))
      (node (ref "R233") (pin "2") (pinfunction "2_2") (pintype "passive"))
      (node (ref "R235") (pin "2") (pinfunction "2_2") (pintype "passive"))
      (node (ref "R241") (pin "1") (pinfunction "1_1") (pintype "passive"))
      (node (ref "R243") (pin "2") (pinfunction "2_2") (pintype "passive"))
      (node (ref "R245") (pin "2") (pinfunction "2_2") (pintype "passive"))
      (node (ref "R25") (pin "2") (pinfunction "2_2") (pintype "passive"))
      (node (ref "R251") (pin "1") (pinfunction "1_1") (pintype "passive"))
      (node (ref "R253") (pin "2") (pinfunction "2_2") (pintype "passive"))
      (node (ref "R255") (pin "2") (pinfunction "2_2") (pintype "passive"))
      (node (ref "R261") (pin "1") (pinfunction "1_1") (pintype "passive"))
      (node (ref "R263") (pin "2") (pinfunction "2_2") (pintype "passive"))
      (node (ref "R265") (pin "2") (pinfunction "2_2") (pintype "passive"))
      (node (ref "U1") (pin "Y9") (pinfunction "AGND_ADC_Y9") (pintype "bidirectional"))
      (node (ref "X10") (pin "2") (pinfunction "SK_2") (pintype "passive"))
      (node (ref "X10") (pin "4") (pinfunction "SK_4") (pintype "passive"))
      (node (ref "X11") (pin "2") (pinfunction "SK_2") (pintype "passive"))
      (node (ref "X11") (pin "4") (pinfunction "SK_4") (pintype "passive"))
      (node (ref "X12") (pin "2") (pinfunction "SK_2") (pintype "passive"))
      (node (ref "X12") (pin "4") (pinfunction "SK_4") (pintype "passive"))
    )
    (net (code "183") (name "CGND") (class "Default")
      (node (ref "MTG1") (pin "B3,6") (pinfunction "MOUNT_B3,6") (pintype "passive"))
      (node (ref "MTG2") (pin "B3,6") (pinfunction "MOUNT_B3,6") (pintype "passive"))
      (node (ref "MTG3") (pin "B3,6") (pinfunction "MOUNT_B3,6") (pintype "passive"))
      (node (ref "MTG4") (pin "B3,6") (pinfunction "MOUNT_B3,6") (pintype "passive"))
      (node (ref "R34") (pin "2") (pinfunction "2_2") (pintype "passive"))
      (node (ref "X1") (pin "CGND1") (pinfunction "SGND1_CGND1") (pintype "bidirectional"))
      (node (ref "X1") (pin "CGND2") (pinfunction "SGND2_CGND2") (pintype "bidirectional"))
      (node (ref "X1") (pin "CGND3") (pinfunction "SGND3_CGND3") (pintype "bidirectional"))
      (node (ref "X1") (pin "CGND4") (pinfunction "SGND4_CGND4") (pintype "bidirectional"))
      (node (ref "X1") (pin "CGND5") (pinfunction "SGND5_CGND5") (pintype "bidirectional"))
      (node (ref "X1") (pin "CGND6") (pinfunction "SGND6_CGND6") (pintype "bidirectional"))
      (node (ref "X2") (pin "S1") (pinfunction "SHD1_S1") (pintype "passive"))
      (node (ref "X2") (pin "S2") (pinfunction "SHD2_S2") (pintype "passive"))
      (node (ref "X5") (pin "10") (pinfunction "GND_2_10") (pintype "bidirectional"))
      (node (ref "X5") (pin "11") (pinfunction "GND_3_11") (pintype "bidirectional"))
      (node (ref "X5") (pin "13") (pinfunction "GND_4_13") (pintype "bidirectional"))
      (node (ref "X5") (pin "9") (pinfunction "GND_1_9") (pintype "bidirectional"))
    )
    (net (code "184") (name "GND") (class "Default")
      (node (ref "C1") (pin "1") (pinfunction "1_1") (pintype "passive"))
      (node (ref "C100") (pin "2") (pinfunction "2_2") (pintype "passive"))
      (node (ref "C101") (pin "2") (pinfunction "2_2") (pintype "passive"))
      (node (ref "C102") (pin "2") (pinfunction "2_2") (pintype "passive"))
      (node (ref "C104") (pin "2") (pinfunction "2_2") (pintype "passive"))
      (node (ref "C105") (pin "2") (pinfunction "2_2") (pintype "passive"))
      (node (ref "C106") (pin "2") (pinfunction "2_2") (pintype "passive"))
      (node (ref "C11") (pin "-") (pinfunction "-_-") (pintype "passive"))
      (node (ref "C14") (pin "2") (pinfunction "2_2") (pintype "passive"))
      (node (ref "C15") (pin "2") (pinfunction "2_2") (pintype "passive"))
      (node (ref "C2") (pin "1") (pinfunction "1_1") (pintype "passive"))
      (node (ref "C21") (pin "2") (pinfunction "2_2") (pintype "passive"))
      (node (ref "C22") (pin "2") (pinfunction "2_2") (pintype "passive"))
      (node (ref "C3") (pin "2") (pinfunction "2_2") (pintype "passive"))
      (node (ref "C301") (pin "2") (pinfunction "2_2") (pintype "passive"))
      (node (ref "C4") (pin "2") (pinfunction "2_2") (pintype "passive"))
      (node (ref "C401") (pin "2") (pinfunction "2_2") (pintype "passive"))
      (node (ref "C404") (pin "2") (pinfunction "2_2") (pintype "passive"))
      (node (ref "C6") (pin "1") (pinfunction "1_1") (pintype "passive"))
      (node (ref "C79") (pin "2") (pinfunction "2_2") (pintype "passive"))
      (node (ref "C801") (pin "2") (pinfunction "2_2") (pintype "passive"))
      (node (ref "C802") (pin "2") (pinfunction "2_2") (pintype "passive"))
      (node (ref "C803") (pin "2") (pinfunction "2_2") (pintype "passive"))
      (node (ref "C85") (pin "2") (pinfunction "2_2") (pintype "passive"))
      (node (ref "C87") (pin "2") (pinfunction "2_2") (pintype "passive"))
      (node (ref "C88") (pin "2") (pinfunction "2_2") (pintype "passive"))
      (node (ref "C901") (pin "2") (pinfunction "2_2") (pintype "passive"))
      (node (ref "D18") (pin "A") (pinfunction "A_A") (pintype "passive"))
      (node (ref "D305") (pin "3") (pinfunction "3_3") (pintype "passive"))
      (node (ref "D805") (pin "3") (pinfunction "3_3") (pintype "passive"))
      (node (ref "EC30") (pin "2") (pinfunction "2_2") (pintype "passive"))
      (node (ref "EC31") (pin "2") (pinfunction "2_2") (pintype "passive"))
      (node (ref "EC32") (pin "2") (pinfunction "2_2") (pintype "passive"))
      (node (ref "EC33") (pin "2") (pinfunction "2_2") (pintype "passive"))
      (node (ref "EC34") (pin "2") (pinfunction "2_2") (pintype "passive"))
      (node (ref "EC35") (pin "2") (pinfunction "2_2") (pintype "passive"))
      (node (ref "EC36") (pin "2") (pinfunction "2_2") (pintype "passive"))
      (node (ref "EC37") (pin "2") (pinfunction "2_2") (pintype "passive"))
      (node (ref "EC38") (pin "2") (pinfunction "2_2") (pintype "passive"))
      (node (ref "EC39") (pin "2") (pinfunction "2_2") (pintype "passive"))
      (node (ref "EC40") (pin "2") (pinfunction "2_2") (pintype "passive"))
      (node (ref "EC41") (pin "2") (pinfunction "2_2") (pintype "passive"))
      (node (ref "EC42") (pin "2") (pinfunction "2_2") (pintype "passive"))
      (node (ref "ER101") (pin "2") (pinfunction "2_2") (pintype "passive"))
      (node (ref "ER102") (pin "2") (pinfunction "2_2") (pintype "passive"))
      (node (ref "ER103") (pin "2") (pinfunction "2_2") (pintype "passive"))
      (node (ref "ER104") (pin "2") (pinfunction "2_2") (pintype "passive"))
      (node (ref "ER115") (pin "1") (pinfunction "1_1") (pintype "passive"))
      (node (ref "ER117") (pin "1") (pinfunction "1_1") (pintype "passive"))
      (node (ref "ER120") (pin "1") (pinfunction "1_1") (pintype "passive"))
      (node (ref "ER128") (pin "1") (pinfunction "1_1") (pintype "passive"))
      (node (ref "ER129") (pin "2") (pinfunction "2_2") (pintype "passive"))
      (node (ref "G1") (pin "-") (pinfunction "-_-") (pintype "passive"))
      (node (ref "IC14") (pin "4") (pinfunction "V-_4") (pintype "power_in"))
      (node (ref "IC2") (pin "8") (pinfunction "GND_8") (pintype "power_in"))
      (node (ref "IC4") (pin "15") (pinfunction "INH_15") (pintype "input"))
      (node (ref "IC5") (pin "10") (pinfunction "SER_10") (pintype "input"))
      (node (ref "IC5") (pin "15") (pinfunction "INH_15") (pintype "input"))
      (node (ref "IC5") (pin "3") (pinfunction "E_3") (pintype "input"))
      (node (ref "IC5") (pin "4") (pinfunction "F_4") (pintype "input"))
      (node (ref "IC5") (pin "5") (pinfunction "G_5") (pintype "input"))
      (node (ref "IC5") (pin "6") (pinfunction "H_6") (pintype "input"))
      (node (ref "J1") (pin "2") (pinfunction "2_2") (pintype "bidirectional"))
      (node (ref "J3") (pin "2") (pinfunction "2_2") (pintype "bidirectional"))
      (node (ref "J7") (pin "2") (pinfunction "2_2") (pintype "bidirectional"))
      (node (ref "R168") (pin "2") (pinfunction "2_2") (pintype "passive"))
      (node (ref "R18") (pin "1") (pinfunction "1_1") (pintype "passive"))
      (node (ref "R26") (pin "2") (pinfunction "2_2") (pintype "passive"))
      (node (ref "R27") (pin "1") (pinfunction "1_1") (pintype "passive"))
      (node (ref "R281") (pin "1") (pinfunction "1_1") (pintype "bidirectional"))
      (node (ref "R281") (pin "2") (pinfunction "2_2") (pintype "bidirectional"))
      (node (ref "R281") (pin "3") (pinfunction "3_3") (pintype "bidirectional"))
      (node (ref "R281") (pin "4") (pinfunction "4_4") (pintype "bidirectional"))
      (node (ref "R282") (pin "1") (pinfunction "1_1") (pintype "bidirectional"))
      (node (ref "R282") (pin "2") (pinfunction "2_2") (pintype "bidirectional"))
      (node (ref "R282") (pin "3") (pinfunction "3_3") (pintype "bidirectional"))
      (node (ref "R282") (pin "4") (pinfunction "4_4") (pintype "bidirectional"))
      (node (ref "R291") (pin "1") (pinfunction "1_1") (pintype "bidirectional"))
      (node (ref "R291") (pin "2") (pinfunction "2_2") (pintype "bidirectional"))
      (node (ref "R291") (pin "3") (pinfunction "3_3") (pintype "bidirectional"))
      (node (ref "R291") (pin "4") (pinfunction "4_4") (pintype "bidirectional"))
      (node (ref "R304") (pin "1") (pinfunction "1_1") (pintype "passive"))
      (node (ref "R34") (pin "1") (pinfunction "1_1") (pintype "passive"))
      (node (ref "R35") (pin "1") (pinfunction "1_1") (pintype "bidirectional"))
      (node (ref "R35") (pin "2") (pinfunction "2_2") (pintype "bidirectional"))
      (node (ref "R35") (pin "3") (pinfunction "3_3") (pintype "bidirectional"))
      (node (ref "R35") (pin "4") (pinfunction "4_4") (pintype "bidirectional"))
      (node (ref "R39") (pin "1") (pinfunction "1_1") (pintype "passive"))
      (node (ref "R53") (pin "1") (pinfunction "1_1") (pintype "passive"))
      (node (ref "R54") (pin "1") (pinfunction "1_1") (pintype "passive"))
      (node (ref "R55") (pin "1") (pinfunction "1_1") (pintype "passive"))
      (node (ref "R56") (pin "1") (pinfunction "1_1") (pintype "passive"))
      (node (ref "R57") (pin "1") (pinfunction "1_1") (pintype "passive"))
      (node (ref "R58") (pin "1") (pinfunction "1_1") (pintype "passive"))
      (node (ref "R59") (pin "1") (pinfunction "1_1") (pintype "passive"))
      (node (ref "R6") (pin "1") (pinfunction "1_1") (pintype "passive"))
      (node (ref "R60") (pin "1") (pinfunction "1_1") (pintype "passive"))
      (node (ref "R61") (pin "1") (pinfunction "1_1") (pintype "passive"))
      (node (ref "R62") (pin "1") (pinfunction "1_1") (pintype "passive"))
      (node (ref "R63") (pin "1") (pinfunction "1_1") (pintype "passive"))
      (node (ref "R64") (pin "1") (pinfunction "1_1") (pintype "passive"))
      (node (ref "R65") (pin "1") (pinfunction "1_1") (pintype "passive"))
      (node (ref "R66") (pin "1") (pinfunction "1_1") (pintype "passive"))
      (node (ref "R67") (pin "1") (pinfunction "1_1") (pintype "passive"))
      (node (ref "R68") (pin "1") (pinfunction "1_1") (pintype "passive"))
      (node (ref "RTC1") (pin "5") (pinfunction "GND_5") (pintype "power_in"))
      (node (ref "S1") (pin "2") (pinfunction "2_2") (pintype "bidirectional"))
      (node (ref "S1") (pin "4") (pinfunction "4_4") (pintype "bidirectional"))
      (node (ref "S2") (pin "1") (pinfunction "1_1") (pintype "bidirectional"))
      (node (ref "S2") (pin "3") (pinfunction "3_3") (pintype "bidirectional"))
      (node (ref "TP8") (pin "P$1") (pinfunction "TP_P$1") (pintype "bidirectional"))
      (node (ref "U1") (pin "A1") (pinfunction "DGND_A1") (pintype "bidirectional"))
      (node (ref "U1") (pin "A20") (pinfunction "DGND_A20") (pintype "bidirectional"))
      (node (ref "U1") (pin "D15") (pinfunction "DGND_D15") (pintype "bidirectional"))
      (node (ref "U1") (pin "D16") (pinfunction "DGND_D16") (pintype "bidirectional"))
      (node (ref "U1") (pin "D17") (pinfunction "DGND_D17") (pintype "bidirectional"))
      (node (ref "U1") (pin "D4") (pinfunction "DGND_D4") (pintype "bidirectional"))
      (node (ref "U1") (pin "D5") (pinfunction "DGND_D5") (pintype "bidirectional"))
      (node (ref "U1") (pin "E10") (pinfunction "DGND_E10") (pintype "bidirectional"))
      (node (ref "U1") (pin "E11") (pinfunction "DGND_E11") (pintype "bidirectional"))
      (node (ref "U1") (pin "E12") (pinfunction "DGND_E12") (pintype "bidirectional"))
      (node (ref "U1") (pin "E13") (pinfunction "DGND_E13") (pintype "bidirectional"))
      (node (ref "U1") (pin "E14") (pinfunction "DGND_E14") (pintype "bidirectional"))
      (node (ref "U1") (pin "E15") (pinfunction "DGND_E15") (pintype "bidirectional"))
      (node (ref "U1") (pin "E16") (pinfunction "DGND_E16") (pintype "bidirectional"))
      (node (ref "U1") (pin "E17") (pinfunction "DGND_E17") (pintype "bidirectional"))
      (node (ref "U1") (pin "E4") (pinfunction "DGND_E4") (pintype "bidirectional"))
      (node (ref "U1") (pin "E5") (pinfunction "DGND_E5") (pintype "bidirectional"))
      (node (ref "U1") (pin "E6") (pinfunction "DGND_E6") (pintype "bidirectional"))
      (node (ref "U1") (pin "E7") (pinfunction "DGND_E7") (pintype "bidirectional"))
      (node (ref "U1") (pin "E8") (pinfunction "DGND_E8") (pintype "bidirectional"))
      (node (ref "U1") (pin "E9") (pinfunction "DGND_E9") (pintype "bidirectional"))
      (node (ref "U1") (pin "F10") (pinfunction "DGND_F10") (pintype "bidirectional"))
      (node (ref "U1") (pin "F11") (pinfunction "DGND_F11") (pintype "bidirectional"))
      (node (ref "U1") (pin "F16") (pinfunction "DGND_F16") (pintype "bidirectional"))
      (node (ref "U1") (pin "F17") (pinfunction "DGND_F17") (pintype "bidirectional"))
      (node (ref "U1") (pin "F5") (pinfunction "DGND_F5") (pintype "bidirectional"))
      (node (ref "U1") (pin "G16") (pinfunction "DGND_G16") (pintype "bidirectional"))
      (node (ref "U1") (pin "G5") (pinfunction "DGND_G5") (pintype "bidirectional"))
      (node (ref "U1") (pin "H16") (pinfunction "DGND_H16") (pintype "bidirectional"))
      (node (ref "U1") (pin "H5") (pinfunction "DGND_H5") (pintype "bidirectional"))
      (node (ref "U1") (pin "J10") (pinfunction "DGND_J10") (pintype "bidirectional"))
      (node (ref "U1") (pin "J11") (pinfunction "DGND_J11") (pintype "bidirectional"))
      (node (ref "U1") (pin "J12") (pinfunction "DGND_J12") (pintype "bidirectional"))
      (node (ref "U1") (pin "J13") (pinfunction "DGND_J13") (pintype "bidirectional"))
      (node (ref "U1") (pin "J16") (pinfunction "DGND_J16") (pintype "bidirectional"))
      (node (ref "U1") (pin "J5") (pinfunction "DGND_J5") (pintype "bidirectional"))
      (node (ref "U1") (pin "J9") (pinfunction "DGND_J9") (pintype "bidirectional"))
      (node (ref "U1") (pin "K12") (pinfunction "DGND_K12") (pintype "bidirectional"))
      (node (ref "U1") (pin "K15") (pinfunction "DGND_K15") (pintype "bidirectional"))
      (node (ref "U1") (pin "K16") (pinfunction "DGND_K16") (pintype "bidirectional"))
      (node (ref "U1") (pin "K5") (pinfunction "DGND_K5") (pintype "bidirectional"))
      (node (ref "U1") (pin "K6") (pinfunction "DGND_K6") (pintype "bidirectional"))
      (node (ref "U1") (pin "K7") (pinfunction "DGND_K7") (pintype "bidirectional"))
      (node (ref "U1") (pin "K8") (pinfunction "DGND_K8") (pintype "bidirectional"))
      (node (ref "U1") (pin "K9") (pinfunction "DGND_K9") (pintype "bidirectional"))
      (node (ref "U1") (pin "L15") (pinfunction "DGND_L15") (pintype "bidirectional"))
      (node (ref "U1") (pin "L16") (pinfunction "DGND_L16") (pintype "bidirectional"))
      (node (ref "U1") (pin "L5") (pinfunction "DGND_L5") (pintype "bidirectional"))
      (node (ref "U1") (pin "L6") (pinfunction "DGND_L6") (pintype "bidirectional"))
      (node (ref "U1") (pin "M15") (pinfunction "DGND_M15") (pintype "bidirectional"))
      (node (ref "U1") (pin "M16") (pinfunction "DGND_M16") (pintype "bidirectional"))
      (node (ref "U1") (pin "M5") (pinfunction "DGND_M5") (pintype "bidirectional"))
      (node (ref "U1") (pin "N15") (pinfunction "DGND_N15") (pintype "bidirectional"))
      (node (ref "U1") (pin "N16") (pinfunction "DGND_N16") (pintype "bidirectional"))
      (node (ref "U1") (pin "N5") (pinfunction "DGND_N5") (pintype "bidirectional"))
      (node (ref "U1") (pin "N6") (pinfunction "DGND_N6") (pintype "bidirectional"))
      (node (ref "U1") (pin "P12") (pinfunction "DGND_P12") (pintype "bidirectional"))
      (node (ref "U1") (pin "P13") (pinfunction "DGND_P13") (pintype "bidirectional"))
      (node (ref "U1") (pin "P14") (pinfunction "DGND_P14") (pintype "bidirectional"))
      (node (ref "U1") (pin "P15") (pinfunction "DGND_P15") (pintype "bidirectional"))
      (node (ref "U1") (pin "P16") (pinfunction "DGND_P16") (pintype "bidirectional"))
      (node (ref "U1") (pin "P5") (pinfunction "DGND_P5") (pintype "bidirectional"))
      (node (ref "U1") (pin "P6") (pinfunction "DGND_P6") (pintype "bidirectional"))
      (node (ref "U1") (pin "P7") (pinfunction "DGND_P7") (pintype "bidirectional"))
      (node (ref "U1") (pin "P8") (pinfunction "DGND_P8") (pintype "bidirectional"))
      (node (ref "U1") (pin "P9") (pinfunction "DGND_P9") (pintype "bidirectional"))
      (node (ref "U1") (pin "R10") (pinfunction "DGND_R10") (pintype "bidirectional"))
      (node (ref "U1") (pin "R11") (pinfunction "DGND_R11") (pintype "bidirectional"))
      (node (ref "U1") (pin "R12") (pinfunction "DGND_R12") (pintype "bidirectional"))
      (node (ref "U1") (pin "R16") (pinfunction "DGND_R16") (pintype "bidirectional"))
      (node (ref "U1") (pin "R5") (pinfunction "DGND_R5") (pintype "bidirectional"))
      (node (ref "U1") (pin "R9") (pinfunction "DGND_R9") (pintype "bidirectional"))
      (node (ref "U1") (pin "T10") (pinfunction "DGND_T10") (pintype "bidirectional"))
      (node (ref "U1") (pin "T11") (pinfunction "DGND_T11") (pintype "bidirectional"))
      (node (ref "U1") (pin "T12") (pinfunction "DGND_T12") (pintype "bidirectional"))
      (node (ref "U1") (pin "T13") (pinfunction "DGND_T13") (pintype "bidirectional"))
      (node (ref "U1") (pin "T14") (pinfunction "DGND_T14") (pintype "bidirectional"))
      (node (ref "U1") (pin "T15") (pinfunction "DGND_T15") (pintype "bidirectional"))
      (node (ref "U1") (pin "T16") (pinfunction "DGND_T16") (pintype "bidirectional"))
      (node (ref "U1") (pin "T17") (pinfunction "DGND_T17") (pintype "bidirectional"))
      (node (ref "U1") (pin "T4") (pinfunction "DGND_T4") (pintype "bidirectional"))
      (node (ref "U1") (pin "T5") (pinfunction "DGND_T5") (pintype "bidirectional"))
      (node (ref "U1") (pin "T6") (pinfunction "DGND_T6") (pintype "bidirectional"))
      (node (ref "U1") (pin "T7") (pinfunction "DGND_T7") (pintype "bidirectional"))
      (node (ref "U1") (pin "T8") (pinfunction "DGND_T8") (pintype "bidirectional"))
      (node (ref "U1") (pin "T9") (pinfunction "DGND_T9") (pintype "bidirectional"))
      (node (ref "U1") (pin "U15") (pinfunction "RTC_KALDO_ENN_U15") (pintype "bidirectional"))
      (node (ref "U1") (pin "U16") (pinfunction "DGND_U16") (pintype "bidirectional"))
      (node (ref "U1") (pin "U17") (pinfunction "DGND_U17") (pintype "bidirectional"))
      (node (ref "U1") (pin "U4") (pinfunction "DGND_U4") (pintype "bidirectional"))
      (node (ref "U1") (pin "U5") (pinfunction "DGND_U5") (pintype "bidirectional"))
      (node (ref "U1") (pin "W13") (pinfunction "OSC1_GND_W13") (pintype "bidirectional"))
      (node (ref "U1") (pin "Y1") (pinfunction "DGND_Y1") (pintype "bidirectional"))
      (node (ref "U1") (pin "Y20") (pinfunction "DGND_Y20") (pintype "bidirectional"))
      (node (ref "U16") (pin "18") (pinfunction "PIRQ#_18") (pintype "bidirectional"))
      (node (ref "U16") (pin "19") (pinfunction "ATEST_19") (pintype "bidirectional"))
      (node (ref "U16") (pin "2") (pinfunction "GND_2") (pintype "bidirectional"))
      (node (ref "U16") (pin "20") (pinfunction "TWI_WAKEUP#_20") (pintype "bidirectional"))
      (node (ref "U16") (pin "21") (pinfunction "ATEST_21") (pintype "bidirectional"))
      (node (ref "U16") (pin "23") (pinfunction "GND_23") (pintype "bidirectional"))
      (node (ref "U16") (pin "24") (pinfunction "ATEST_24") (pintype "bidirectional"))
      (node (ref "U16") (pin "32") (pinfunction "GND_32") (pintype "bidirectional"))
      (node (ref "U16") (pin "5") (pinfunction "TESTL_5") (pintype "bidirectional"))
      (node (ref "U16") (pin "6") (pinfunction "XTAMPER_6") (pintype "bidirectional"))
      (node (ref "U16") (pin "9") (pinfunction "GND_9") (pintype "bidirectional"))
      (node (ref "U2") (pin "4") (pinfunction "GND_4") (pintype "power_in"))
      (node (ref "U27") (pin "33") (pinfunction "GND_EP_33") (pintype "power_in"))
      (node (ref "U28") (pin "2") (pinfunction "GND_2") (pintype "power_in"))
      (node (ref "U29") (pin "5") (pinfunction "GND_5") (pintype "power_in"))
      (node (ref "U4") (pin "1") (pinfunction "GND_1") (pintype "bidirectional"))
      (node (ref "U40") (pin "3") (pinfunction "GND1_3") (pintype "power_in"))
      (node (ref "U6") (pin "1") (pinfunction "*1OE_1") (pintype "input"))
      (node (ref "U6") (pin "4") (pinfunction "GND_4") (pintype "power_in"))
      (node (ref "VREG1") (pin "3") (pinfunction "GND_3") (pintype "power_in"))
      (node (ref "VREG1") (pin "5") (pinfunction "EN_5") (pintype "input"))
      (node (ref "VREG1") (pin "6") (pinfunction "GND_6") (pintype "power_in"))
      (node (ref "VREG2") (pin "GND") (pinfunction "GND_GND") (pintype "input"))
      (node (ref "X1") (pin "GND") (pinfunction "GND_GND") (pintype "input"))
      (node (ref "X2") (pin "8") (pinfunction "D_GND_8") (pintype "passive"))
      (node (ref "X24") (pin "2") (pinfunction "1_2") (pintype "passive"))
      (node (ref "X3") (pin "1") (pinfunction "SK_1") (pintype "passive"))
      (node (ref "X31") (pin "1") (pinfunction "SK_1") (pintype "passive"))
      (node (ref "X4") (pin "10") (pinfunction "GND2_10") (pintype "bidirectional"))
      (node (ref "X4") (pin "12") (pinfunction "GND3_12") (pintype "bidirectional"))
      (node (ref "X4") (pin "16") (pinfunction "GND4_16") (pintype "bidirectional"))
      (node (ref "X4") (pin "20") (pinfunction "GND5_20") (pintype "bidirectional"))
      (node (ref "X4") (pin "4") (pinfunction "TDIS_4") (pintype "bidirectional"))
      (node (ref "X4") (pin "8") (pinfunction "GND1_8") (pintype "bidirectional"))
      (node (ref "X5") (pin "6") (pinfunction "VSS_6") (pintype "bidirectional"))
      (node (ref "X6") (pin "1") (pinfunction "1_1") (pintype "bidirectional"))
      (node (ref "X8") (pin "16") (pinfunction "16_16") (pintype "bidirectional"))
      (node (ref "X8") (pin "2") (pinfunction "2_2") (pintype "bidirectional"))
      (node (ref "X9") (pin "P$2") (pinfunction "2_P$2") (pintype "passive"))
    )
    (net (code "185") (name "ISO_GND") (class "Default")
      (node (ref "C402") (pin "2") (pinfunction "2_2") (pintype "passive"))
      (node (ref "C403") (pin "2") (pinfunction "2_2") (pintype "passive"))
      (node (ref "C405") (pin "2") (pinfunction "2_2") (pintype "passive"))
      (node (ref "C406") (pin "-") (pinfunction "-_-") (pintype "passive"))
      (node (ref "D405") (pin "3") (pinfunction "3_3") (pintype "passive"))
      (node (ref "GDT1") (pin "3") (pinfunction "3_3") (pintype "passive"))
      (node (ref "T4") (pin "P$6") (pinfunction "6_P$6") (pintype "passive"))
      (node (ref "T4") (pin "P$7") (pinfunction "7_P$7") (pintype "passive"))
      (node (ref "U40") (pin "15") (pinfunction "GND2_15") (pintype "power_in"))
      (node (ref "U40") (pin "9") (pinfunction "GND2_2_9") (pintype "power_in"))
      (node (ref "VREG4") (pin "2") (pinfunction "GND_2") (pintype "power_in"))
      (node (ref "X41") (pin "3") (pinfunction "1_3") (pintype "passive"))
    )
    (net (code "186") (name "Net-(C105-Pad1)") (class "Default")
      (node (ref "C105") (pin "1") (pinfunction "1_1") (pintype "passive"))
      (node (ref "J24") (pin "1") (pinfunction "1_1") (pintype "bidirectional"))
      (node (ref "VREG2") (pin "IN") (pinfunction "IN_IN") (pintype "input"))
    )
    (net (code "187") (name "Net-(D1-C)") (class "Default")
      (node (ref "D1") (pin "2") (pinfunction "C_2") (pintype "passive"))
      (node (ref "R26") (pin "1") (pinfunction "1_1") (pintype "passive"))
    )
    (net (code "188") (name "Net-(D4-C)") (class "Default")
      (node (ref "D4") (pin "2") (pinfunction "C_2") (pintype "passive"))
      (node (ref "R35") (pin "5") (pinfunction "5_5") (pintype "bidirectional"))
    )
    (net (code "189") (name "Net-(D5-C)") (class "Default")
      (node (ref "D5") (pin "2") (pinfunction "C_2") (pintype "passive"))
      (node (ref "R35") (pin "6") (pinfunction "6_6") (pintype "bidirectional"))
    )
    (net (code "190") (name "Net-(D6-C)") (class "Default")
      (node (ref "D6") (pin "2") (pinfunction "C_2") (pintype "passive"))
      (node (ref "R35") (pin "7") (pinfunction "7_7") (pintype "bidirectional"))
    )
    (net (code "191") (name "Net-(D7-C)") (class "Default")
      (node (ref "D7") (pin "2") (pinfunction "C_2") (pintype "passive"))
      (node (ref "R35") (pin "8") (pinfunction "8_8") (pintype "bidirectional"))
    )
    (net (code "192") (name "Net-(D19-C)") (class "Default")
      (node (ref "D19") (pin "2") (pinfunction "C_2") (pintype "passive"))
      (node (ref "R168") (pin "1") (pinfunction "1_1") (pintype "passive"))
    )
    (net (code "193") (name "Net-(D31-C)") (class "Default")
      (node (ref "D31") (pin "2") (pinfunction "C_2") (pintype "passive"))
      (node (ref "R171") (pin "1") (pinfunction "1_1") (pintype "passive"))
    )
    (net (code "194") (name "Net-(D32-C)") (class "Default")
      (node (ref "D32") (pin "2") (pinfunction "C_2") (pintype "passive"))
      (node (ref "R172") (pin "1") (pinfunction "1_1") (pintype "passive"))
    )
    (net (code "195") (name "Net-(D33-C)") (class "Default")
      (node (ref "D33") (pin "2") (pinfunction "C_2") (pintype "passive"))
      (node (ref "R173") (pin "1") (pinfunction "1_1") (pintype "passive"))
    )
    (net (code "196") (name "Net-(D34-C)") (class "Default")
      (node (ref "D34") (pin "2") (pinfunction "C_2") (pintype "passive"))
      (node (ref "R174") (pin "1") (pinfunction "1_1") (pintype "passive"))
    )
    (net (code "197") (name "Net-(D301-A)") (class "Default")
      (node (ref "D301") (pin "1") (pinfunction "A_1") (pintype "passive"))
      (node (ref "R301") (pin "2") (pinfunction "2_2") (pintype "passive"))
    )
    (net (code "198") (name "Net-(D302-A)") (class "Default")
      (node (ref "D302") (pin "1") (pinfunction "A_1") (pintype "passive"))
      (node (ref "R302") (pin "2") (pinfunction "2_2") (pintype "passive"))
    )
    (net (code "199") (name "Net-(D401-A)") (class "Default")
      (node (ref "D401") (pin "1") (pinfunction "A_1") (pintype "passive"))
      (node (ref "R401") (pin "2") (pinfunction "2_2") (pintype "passive"))
    )
    (net (code "200") (name "Net-(D402-A)") (class "Default")
      (node (ref "D402") (pin "1") (pinfunction "A_1") (pintype "passive"))
      (node (ref "R402") (pin "2") (pinfunction "2_2") (pintype "passive"))
    )
    (net (code "201") (name "Net-(D801-A)") (class "Default")
      (node (ref "D801") (pin "1") (pinfunction "A_1") (pintype "passive"))
      (node (ref "R801") (pin "2") (pinfunction "2_2") (pintype "passive"))
    )
    (net (code "202") (name "Net-(D802-A)") (class "Default")
      (node (ref "D802") (pin "1") (pinfunction "A_1") (pintype "passive"))
      (node (ref "R802") (pin "2") (pinfunction "2_2") (pintype "passive"))
    )
    (net (code "203") (name "Net-(F1-1)") (class "Default")
      (node (ref "F1") (pin "P$1") (pinfunction "1_P$1") (pintype "bidirectional"))
      (node (ref "X24") (pin "1") (pinfunction "1_1") (pintype "passive"))
      (node (ref "X3") (pin "4") (pinfunction "SK_4") (pintype "passive"))
    )
    (net (code "204") (name "Net-(F1-2)") (class "Default")
      (node (ref "D3") (pin "A") (pinfunction "A_A") (pintype "passive"))
      (node (ref "F1") (pin "P$2") (pinfunction "2_P$2") (pintype "bidirectional"))
    )
    (net (code "205") (name "Net-(IC4A-A)") (class "Default")
      (node (ref "IC4") (pin "11") (pinfunction "A_11") (pintype "input"))
      (node (ref "R281") (pin "8") (pinfunction "8_8") (pintype "bidirectional"))
      (node (ref "S11") (pin "1") (pinfunction "1_1") (pintype "passive"))
    )
    (net (code "206") (name "Net-(IC4A-B)") (class "Default")
      (node (ref "IC4") (pin "12") (pinfunction "B_12") (pintype "input"))
      (node (ref "R281") (pin "7") (pinfunction "7_7") (pintype "bidirectional"))
      (node (ref "S11") (pin "2") (pinfunction "2_2") (pintype "passive"))
    )
    (net (code "207") (name "Net-(IC4A-C)") (class "Default")
      (node (ref "IC4") (pin "13") (pinfunction "C_13") (pintype "input"))
      (node (ref "R281") (pin "6") (pinfunction "6_6") (pintype "bidirectional"))
      (node (ref "S11") (pin "4") (pinfunction "4_4") (pintype "passive"))
    )
    (net (code "208") (name "Net-(IC4A-D)") (class "Default")
      (node (ref "IC4") (pin "14") (pinfunction "D_14") (pintype "input"))
      (node (ref "R281") (pin "5") (pinfunction "5_5") (pintype "bidirectional"))
      (node (ref "S11") (pin "8") (pinfunction "8_8") (pintype "passive"))
    )
    (net (code "209") (name "Net-(IC4A-E)") (class "Default")
      (node (ref "IC4") (pin "3") (pinfunction "E_3") (pintype "input"))
      (node (ref "R282") (pin "8") (pinfunction "8_8") (pintype "bidirectional"))
      (node (ref "S12") (pin "1") (pinfunction "1_1") (pintype "passive"))
    )
    (net (code "210") (name "Net-(IC4A-F)") (class "Default")
      (node (ref "IC4") (pin "4") (pinfunction "F_4") (pintype "input"))
      (node (ref "R282") (pin "7") (pinfunction "7_7") (pintype "bidirectional"))
      (node (ref "S12") (pin "2") (pinfunction "2_2") (pintype "passive"))
    )
    (net (code "211") (name "Net-(IC4A-G)") (class "Default")
      (node (ref "IC4") (pin "5") (pinfunction "G_5") (pintype "input"))
      (node (ref "R282") (pin "6") (pinfunction "6_6") (pintype "bidirectional"))
      (node (ref "S12") (pin "4") (pinfunction "4_4") (pintype "passive"))
    )
    (net (code "212") (name "Net-(IC4A-H)") (class "Default")
      (node (ref "IC4") (pin "6") (pinfunction "H_6") (pintype "input"))
      (node (ref "R282") (pin "5") (pinfunction "5_5") (pintype "bidirectional"))
      (node (ref "S12") (pin "8") (pinfunction "8_8") (pintype "passive"))
    )
    (net (code "213") (name "Net-(IC4A-SER)") (class "Default")
      (node (ref "IC4") (pin "10") (pinfunction "SER_10") (pintype "input"))
      (node (ref "IC5") (pin "9") (pinfunction "QH_9") (pintype "output"))
    )
    (net (code "214") (name "Net-(IC5A-A)") (class "Default")
      (node (ref "IC5") (pin "11") (pinfunction "A_11") (pintype "input"))
      (node (ref "R291") (pin "8") (pinfunction "8_8") (pintype "bidirectional"))
      (node (ref "S13") (pin "8") (pinfunction "8_8") (pintype "passive"))
    )
    (net (code "215") (name "Net-(IC5A-B)") (class "Default")
      (node (ref "IC5") (pin "12") (pinfunction "B_12") (pintype "input"))
      (node (ref "R291") (pin "7") (pinfunction "7_7") (pintype "bidirectional"))
      (node (ref "S13") (pin "7") (pinfunction "7_7") (pintype "passive"))
    )
    (net (code "216") (name "Net-(IC5A-C)") (class "Default")
      (node (ref "IC5") (pin "13") (pinfunction "C_13") (pintype "input"))
      (node (ref "R291") (pin "6") (pinfunction "6_6") (pintype "bidirectional"))
      (node (ref "S13") (pin "6") (pinfunction "6_6") (pintype "passive"))
    )
    (net (code "217") (name "Net-(IC5A-D)") (class "Default")
      (node (ref "IC5") (pin "14") (pinfunction "D_14") (pintype "input"))
      (node (ref "R291") (pin "5") (pinfunction "5_5") (pintype "bidirectional"))
      (node (ref "S13") (pin "5") (pinfunction "5_5") (pintype "passive"))
    )
    (net (code "218") (name "Net-(IC10A-+IN)") (class "Default")
      (node (ref "C111") (pin "1") (pinfunction "1_1") (pintype "passive"))
      (node (ref "IC10") (pin "3") (pinfunction "+IN_3") (pintype "input"))
      (node (ref "J13") (pin "1") (pinfunction "1_1") (pintype "bidirectional"))
      (node (ref "R214") (pin "2") (pinfunction "2_2") (pintype "passive"))
    )
    (net (code "219") (name "Net-(IC10B-+IN)") (class "Default")
      (node (ref "C121") (pin "1") (pinfunction "1_1") (pintype "passive"))
      (node (ref "IC10") (pin "5") (pinfunction "+IN_5") (pintype "input"))
      (node (ref "J23") (pin "1") (pinfunction "1_1") (pintype "bidirectional"))
      (node (ref "R224") (pin "2") (pinfunction "2_2") (pintype "passive"))
    )
    (net (code "220") (name "Net-(IC11A-+IN)") (class "Default")
      (node (ref "C131") (pin "1") (pinfunction "1_1") (pintype "passive"))
      (node (ref "IC11") (pin "3") (pinfunction "+IN_3") (pintype "input"))
      (node (ref "J33") (pin "1") (pinfunction "1_1") (pintype "bidirectional"))
      (node (ref "R234") (pin "2") (pinfunction "2_2") (pintype "passive"))
    )
    (net (code "221") (name "Net-(IC11B-+IN)") (class "Default")
      (node (ref "C141") (pin "1") (pinfunction "1_1") (pintype "passive"))
      (node (ref "IC11") (pin "5") (pinfunction "+IN_5") (pintype "input"))
      (node (ref "J43") (pin "1") (pinfunction "1_1") (pintype "bidirectional"))
      (node (ref "R244") (pin "2") (pinfunction "2_2") (pintype "passive"))
    )
    (net (code "222") (name "Net-(IC12A-+IN)") (class "Default")
      (node (ref "C151") (pin "1") (pinfunction "1_1") (pintype "passive"))
      (node (ref "IC12") (pin "3") (pinfunction "+IN_3") (pintype "input"))
      (node (ref "J53") (pin "1") (pinfunction "1_1") (pintype "bidirectional"))
      (node (ref "R254") (pin "2") (pinfunction "2_2") (pintype "passive"))
    )
    (net (code "223") (name "Net-(IC12B-+IN)") (class "Default")
      (node (ref "C161") (pin "1") (pinfunction "1_1") (pintype "passive"))
      (node (ref "IC12") (pin "5") (pinfunction "+IN_5") (pintype "input"))
      (node (ref "J63") (pin "1") (pinfunction "1_1") (pintype "bidirectional"))
      (node (ref "R264") (pin "2") (pinfunction "2_2") (pintype "passive"))
    )
    (net (code "224") (name "Net-(J3-Pad1)") (class "Default")
      (node (ref "J3") (pin "1") (pinfunction "1_1") (pintype "bidirectional"))
      (node (ref "R69") (pin "2") (pinfunction "2_2") (pintype "passive"))
    )
    (net (code "225") (name "Net-(J11-Pad2)") (class "Default")
      (node (ref "J11") (pin "2") (pinfunction "2_2") (pintype "bidirectional"))
      (node (ref "R211") (pin "2") (pinfunction "2_2") (pintype "passive"))
    )
    (net (code "226") (name "Net-(J12-Pad2)") (class "Default")
      (node (ref "J12") (pin "2") (pinfunction "2_2") (pintype "bidirectional"))
      (node (ref "R212") (pin "1") (pinfunction "1_1") (pintype "passive"))
    )
    (net (code "227") (name "Net-(J13-Pad2)") (class "Default")
      (node (ref "J13") (pin "2") (pinfunction "2_2") (pintype "bidirectional"))
      (node (ref "R213") (pin "1") (pinfunction "1_1") (pintype "passive"))
    )
    (net (code "228") (name "Net-(J21-Pad2)") (class "Default")
      (node (ref "J21") (pin "2") (pinfunction "2_2") (pintype "bidirectional"))
      (node (ref "R221") (pin "2") (pinfunction "2_2") (pintype "passive"))
    )
    (net (code "229") (name "Net-(J22-Pad2)") (class "Default")
      (node (ref "J22") (pin "2") (pinfunction "2_2") (pintype "bidirectional"))
      (node (ref "R222") (pin "1") (pinfunction "1_1") (pintype "passive"))
    )
    (net (code "230") (name "Net-(J23-Pad2)") (class "Default")
      (node (ref "J23") (pin "2") (pinfunction "2_2") (pintype "bidirectional"))
      (node (ref "R223") (pin "1") (pinfunction "1_1") (pintype "passive"))
    )
    (net (code "231") (name "Net-(J31-Pad2)") (class "Default")
      (node (ref "J31") (pin "2") (pinfunction "2_2") (pintype "bidirectional"))
      (node (ref "R231") (pin "2") (pinfunction "2_2") (pintype "passive"))
    )
    (net (code "232") (name "Net-(J32-Pad2)") (class "Default")
      (node (ref "J32") (pin "2") (pinfunction "2_2") (pintype "bidirectional"))
      (node (ref "R232") (pin "1") (pinfunction "1_1") (pintype "passive"))
    )
    (net (code "233") (name "Net-(J33-Pad2)") (class "Default")
      (node (ref "J33") (pin "2") (pinfunction "2_2") (pintype "bidirectional"))
      (node (ref "R233") (pin "1") (pinfunction "1_1") (pintype "passive"))
    )
    (net (code "234") (name "Net-(J41-Pad2)") (class "Default")
      (node (ref "J41") (pin "2") (pinfunction "2_2") (pintype "bidirectional"))
      (node (ref "R241") (pin "2") (pinfunction "2_2") (pintype "passive"))
    )
    (net (code "235") (name "Net-(J42-Pad2)") (class "Default")
      (node (ref "J42") (pin "2") (pinfunction "2_2") (pintype "bidirectional"))
      (node (ref "R242") (pin "1") (pinfunction "1_1") (pintype "passive"))
    )
    (net (code "236") (name "Net-(J43-Pad2)") (class "Default")
      (node (ref "J43") (pin "2") (pinfunction "2_2") (pintype "bidirectional"))
      (node (ref "R243") (pin "1") (pinfunction "1_1") (pintype "passive"))
    )
    (net (code "237") (name "Net-(J51-Pad2)") (class "Default")
      (node (ref "J51") (pin "2") (pinfunction "2_2") (pintype "bidirectional"))
      (node (ref "R251") (pin "2") (pinfunction "2_2") (pintype "passive"))
    )
    (net (code "238") (name "Net-(J52-Pad2)") (class "Default")
      (node (ref "J52") (pin "2") (pinfunction "2_2") (pintype "bidirectional"))
      (node (ref "R252") (pin "1") (pinfunction "1_1") (pintype "passive"))
    )
    (net (code "239") (name "Net-(J53-Pad2)") (class "Default")
      (node (ref "J53") (pin "2") (pinfunction "2_2") (pintype "bidirectional"))
      (node (ref "R253") (pin "1") (pinfunction "1_1") (pintype "passive"))
    )
    (net (code "240") (name "Net-(J61-Pad2)") (class "Default")
      (node (ref "J61") (pin "2") (pinfunction "2_2") (pintype "bidirectional"))
      (node (ref "R261") (pin "2") (pinfunction "2_2") (pintype "passive"))
    )
    (net (code "241") (name "Net-(J62-Pad2)") (class "Default")
      (node (ref "J62") (pin "2") (pinfunction "2_2") (pintype "bidirectional"))
      (node (ref "R262") (pin "1") (pinfunction "1_1") (pintype "passive"))
    )
    (net (code "242") (name "Net-(J63-Pad2)") (class "Default")
      (node (ref "J63") (pin "2") (pinfunction "2_2") (pintype "bidirectional"))
      (node (ref "R263") (pin "1") (pinfunction "1_1") (pintype "passive"))
    )
    (net (code "243") (name "Net-(R10-Pad1)") (class "Default")
      (node (ref "R10") (pin "1") (pinfunction "1_1") (pintype "passive"))
      (node (ref "X1") (pin "VBUS") (pinfunction "VBUS_VBUS") (pintype "input"))
    )
    (net (code "244") (name "Net-(R11-Pad1)") (class "Default")
      (node (ref "R11") (pin "1") (pinfunction "1_1") (pintype "passive"))
      (node (ref "S1") (pin "1") (pinfunction "1_1") (pintype "bidirectional"))
      (node (ref "S1") (pin "3") (pinfunction "3_3") (pintype "bidirectional"))
    )
    (net (code "245") (name "Net-(RTC1-VBAT)") (class "Default")
      (node (ref "G1") (pin "+") (pinfunction "+_+") (pintype "passive"))
      (node (ref "RTC1") (pin "6") (pinfunction "VBAT_6") (pintype "power_in"))
    )
    (net (code "246") (name "Net-(T4-1)") (class "Default")
      (node (ref "T4") (pin "P$1") (pinfunction "1_P$1") (pintype "passive"))
      (node (ref "U40") (pin "1") (pinfunction "D1_1") (pintype "passive"))
    )
    (net (code "247") (name "Net-(T4-4)") (class "Default")
      (node (ref "T4") (pin "P$4") (pinfunction "4_P$4") (pintype "passive"))
      (node (ref "U40") (pin "2") (pinfunction "D2_2") (pintype "passive"))
    )
    (net (code "248") (name "Net-(T4-5)") (class "Default")
      (node (ref "D404") (pin "A") (pinfunction "A_A") (pintype "passive"))
      (node (ref "T4") (pin "P$5") (pinfunction "5_P$5") (pintype "passive"))
    )
    (net (code "249") (name "Net-(T4-8)") (class "Default")
      (node (ref "D403") (pin "A") (pinfunction "A_A") (pintype "passive"))
      (node (ref "T4") (pin "P$8") (pinfunction "8_P$8") (pintype "passive"))
    )
    (net (code "250") (name "Net-(U1A-EEPROM_WP)") (class "Default")
      (node (ref "J1") (pin "1") (pinfunction "1_1") (pintype "bidirectional"))
      (node (ref "U1") (pin "M2") (pinfunction "EEPROM_WP_M2") (pintype "bidirectional"))
    )
    (net (code "251") (name "Net-(U1A-PWRONRSTN_OD)") (class "Default")
      (node (ref "R5") (pin "1") (pinfunction "1_1") (pintype "passive"))
      (node (ref "U1") (pin "C17") (pinfunction "PWRONRSTN_OD_C17") (pintype "bidirectional"))
    )
    (net (code "252") (name "Net-(U1A-SYS_VDD1_CTL)") (class "Default")
      (node (ref "TP33") (pin "TP") (pinfunction "TP_TP") (pintype "input"))
      (node (ref "U1") (pin "F18") (pinfunction "SYS_VDD1_CTL_F18") (pintype "bidirectional"))
    )
    (net (code "253") (name "Net-(U1C-XDMA_EVENT_INTR0)") (class "Default")
      (node (ref "R4") (pin "1") (pinfunction "1_1") (pintype "passive"))
      (node (ref "U1") (pin "W14") (pinfunction "XDMA_EVENT_INTR0_W14") (pintype "bidirectional"))
    )
    (net (code "254") (name "Net-(U1C-XDMA_EVENT_INTR1)") (class "Default")
      (node (ref "R3") (pin "1") (pinfunction "1_1") (pintype "passive"))
      (node (ref "U1") (pin "V14") (pinfunction "XDMA_EVENT_INTR1_V14") (pintype "bidirectional"))
    )
    (net (code "255") (name "Net-(U1D-LCD_AC_BIAS_EN)") (class "Default")
      (node (ref "R28") (pin "1") (pinfunction "1_1") (pintype "passive"))
      (node (ref "U1") (pin "V20") (pinfunction "LCD_AC_BIAS_EN_V20") (pintype "bidirectional"))
    )
    (net (code "256") (name "Net-(U1D-LCD_HSYNC)") (class "Default")
      (node (ref "R29") (pin "1") (pinfunction "1_1") (pintype "passive"))
      (node (ref "U1") (pin "U19") (pinfunction "LCD_HSYNC_U19") (pintype "bidirectional"))
    )
    (net (code "257") (name "Net-(U1D-LCD_PCLK)") (class "Default")
      (node (ref "R31") (pin "1") (pinfunction "1_1") (pintype "passive"))
      (node (ref "U1") (pin "U20") (pinfunction "LCD_PCLK_U20") (pintype "bidirectional"))
    )
    (net (code "258") (name "Net-(U1D-LCD_VSYNC)") (class "Default")
      (node (ref "R30") (pin "1") (pinfunction "1_1") (pintype "passive"))
      (node (ref "U1") (pin "U18") (pinfunction "LCD_VSYNC_U18") (pintype "bidirectional"))
    )
    (net (code "259") (name "Net-(U4-MR#)") (class "Default")
      (node (ref "R11") (pin "2") (pinfunction "2_2") (pintype "passive"))
      (node (ref "R5") (pin "2") (pinfunction "2_2") (pintype "passive"))
      (node (ref "U4") (pin "3") (pinfunction "MR#_3") (pintype "bidirectional"))
    )
    (net (code "260") (name "Net-(U4-RESET#)") (class "Default")
      (node (ref "R8") (pin "2") (pinfunction "2_2") (pintype "passive"))
      (node (ref "U4") (pin "2") (pinfunction "RESET#_2") (pintype "bidirectional"))
    )
    (net (code "261") (name "Net-(U5-CATHODE)") (class "Default")
      (node (ref "Q1") (pin "B") (pinfunction "B_B") (pintype "passive"))
      (node (ref "R21") (pin "1") (pinfunction "1_1") (pintype "passive"))
      (node (ref "U5") (pin "2") (pinfunction "CATHODE_2") (pintype "bidirectional"))
    )
    (net (code "262") (name "Net-(U5-REF)") (class "Default")
      (node (ref "R15") (pin "2") (pinfunction "2_2") (pintype "passive"))
      (node (ref "R20") (pin "1") (pinfunction "1_1") (pintype "passive"))
      (node (ref "U5") (pin "1") (pinfunction "REF_1") (pintype "bidirectional"))
    )
    (net (code "263") (name "Net-(U27-NINT{slash}TXER{slash}TXD4)") (class "Default")
      (node (ref "ER129") (pin "1") (pinfunction "1_1") (pintype "passive"))
      (node (ref "U27") (pin "18") (pinfunction "NINT/TXER/TXD4_18") (pintype "bidirectional"))
    )
    (net (code "264") (name "Net-(U27-RBIAS)") (class "Default")
      (node (ref "ER128") (pin "2") (pinfunction "2_2") (pintype "passive"))
      (node (ref "U27") (pin "32") (pinfunction "RBIAS_32") (pintype "passive"))
    )
    (net (code "265") (name "Net-(U27-VDDCR)") (class "Default")
      (node (ref "EC33") (pin "1") (pinfunction "1_1") (pintype "passive"))
      (node (ref "EC35") (pin "1") (pinfunction "1_1") (pintype "passive"))
      (node (ref "U27") (pin "6") (pinfunction "VDDCR_6") (pintype "power_in"))
    )
    (net (code "266") (name "Net-(U27-XTAL1{slash}CLKIN)") (class "Default")
      (node (ref "ER126") (pin "1") (pinfunction "1_1") (pintype "passive"))
      (node (ref "U27") (pin "5") (pinfunction "XTAL1/CLKIN_5") (pintype "input"))
    )
    (net (code "267") (name "Net-(U27-XTAL2)") (class "Default")
      (node (ref "ER125") (pin "1") (pinfunction "1_1") (pintype "passive"))
      (node (ref "ER127") (pin "1") (pinfunction "1_1") (pintype "passive"))
      (node (ref "U27") (pin "4") (pinfunction "XTAL2_4") (pintype "input"))
    )
    (net (code "268") (name "Net-(VREG1-IN)") (class "Default")
      (node (ref "C100") (pin "1") (pinfunction "1_1") (pintype "passive"))
      (node (ref "C101") (pin "1") (pinfunction "1_1") (pintype "passive"))
      (node (ref "D3") (pin "C") (pinfunction "C_C") (pintype "passive"))
      (node (ref "J24") (pin "2") (pinfunction "2_2") (pintype "bidirectional"))
      (node (ref "VREG1") (pin "1") (pinfunction "IN_1") (pintype "input"))
    )
    (net (code "269") (name "Net-(X2-GRNC)") (class "Default")
      (node (ref "ER117") (pin "2") (pinfunction "2_2") (pintype "passive"))
      (node (ref "X2") (pin "10") (pinfunction "GRNC_10") (pintype "passive"))
    )
    (net (code "270") (name "Net-(X2-RCT)") (class "Default")
      (node (ref "EC40") (pin "1") (pinfunction "1_1") (pintype "passive"))
      (node (ref "ER122") (pin "2") (pinfunction "2_2") (pintype "passive"))
      (node (ref "X2") (pin "4") (pinfunction "TCT_4") (pintype "passive"))
      (node (ref "X2") (pin "5") (pinfunction "RCT_5") (pintype "passive"))
    )
    (net (code "271") (name "Net-(X2-YELC)") (class "Default")
      (node (ref "ER115") (pin "2") (pinfunction "2_2") (pintype "passive"))
      (node (ref "X2") (pin "11") (pinfunction "YELC_11") (pintype "passive"))
    )
    (net (code "272") (name "Net-(X10A-SK)") (class "Default")
      (node (ref "J11") (pin "1") (pinfunction "1_1") (pintype "bidirectional"))
      (node (ref "J12") (pin "1") (pinfunction "1_1") (pintype "bidirectional"))
      (node (ref "R181") (pin "1") (pinfunction "1_1") (pintype "passive"))
      (node (ref "R214") (pin "1") (pinfunction "1_1") (pintype "passive"))
      (node (ref "X10") (pin "1") (pinfunction "SK_1") (pintype "passive"))
    )
    (net (code "273") (name "Net-(X10C-SK)") (class "Default")
      (node (ref "J21") (pin "1") (pinfunction "1_1") (pintype "bidirectional"))
      (node (ref "J22") (pin "1") (pinfunction "1_1") (pintype "bidirectional"))
      (node (ref "R182") (pin "1") (pinfunction "1_1") (pintype "passive"))
      (node (ref "R224") (pin "1") (pinfunction "1_1") (pintype "passive"))
      (node (ref "X10") (pin "3") (pinfunction "SK_3") (pintype "passive"))
    )
    (net (code "274") (name "Net-(X11A-SK)") (class "Default")
      (node (ref "J31") (pin "1") (pinfunction "1_1") (pintype "bidirectional"))
      (node (ref "J32") (pin "1") (pinfunction "1_1") (pintype "bidirectional"))
      (node (ref "R183") (pin "1") (pinfunction "1_1") (pintype "passive"))
      (node (ref "R234") (pin "1") (pinfunction "1_1") (pintype "passive"))
      (node (ref "X11") (pin "1") (pinfunction "SK_1") (pintype "passive"))
    )
    (net (code "275") (name "Net-(X11C-SK)") (class "Default")
      (node (ref "J41") (pin "1") (pinfunction "1_1") (pintype "bidirectional"))
      (node (ref "J42") (pin "1") (pinfunction "1_1") (pintype "bidirectional"))
      (node (ref "R184") (pin "1") (pinfunction "1_1") (pintype "passive"))
      (node (ref "R244") (pin "1") (pinfunction "1_1") (pintype "passive"))
      (node (ref "X11") (pin "3") (pinfunction "SK_3") (pintype "passive"))
    )
    (net (code "276") (name "Net-(X12A-SK)") (class "Default")
      (node (ref "J51") (pin "1") (pinfunction "1_1") (pintype "bidirectional"))
      (node (ref "J52") (pin "1") (pinfunction "1_1") (pintype "bidirectional"))
      (node (ref "R185") (pin "1") (pinfunction "1_1") (pintype "passive"))
      (node (ref "R254") (pin "1") (pinfunction "1_1") (pintype "passive"))
      (node (ref "X12") (pin "1") (pinfunction "SK_1") (pintype "passive"))
    )
    (net (code "277") (name "Net-(X12C-SK)") (class "Default")
      (node (ref "J61") (pin "1") (pinfunction "1_1") (pintype "bidirectional"))
      (node (ref "J62") (pin "1") (pinfunction "1_1") (pintype "bidirectional"))
      (node (ref "R186") (pin "1") (pinfunction "1_1") (pintype "passive"))
      (node (ref "R264") (pin "1") (pinfunction "1_1") (pintype "passive"))
      (node (ref "X12") (pin "3") (pinfunction "SK_3") (pintype "passive"))
    )
    (net (code "278") (name "Net-(Y7-1)") (class "Default")
      (node (ref "EC41") (pin "1") (pinfunction "1_1") (pintype "passive"))
      (node (ref "ER127") (pin "2") (pinfunction "2_2") (pintype "passive"))
      (node (ref "Y7") (pin "P$1") (pinfunction "1_P$1") (pintype "passive"))
    )
    (net (code "279") (name "Net-(Y7-2)") (class "Default")
      (node (ref "EC42") (pin "1") (pinfunction "1_1") (pintype "passive"))
      (node (ref "ER125") (pin "2") (pinfunction "2_2") (pintype "passive"))
      (node (ref "ER126") (pin "2") (pinfunction "2_2") (pintype "passive"))
      (node (ref "Y7") (pin "P$2") (pinfunction "2_P$2") (pintype "passive"))
    )
    (net (code "280") (name "SYS_ADC_1P8V") (class "Default")
      (node (ref "C10") (pin "1") (pinfunction "1_1") (pintype "passive"))
      (node (ref "IC14") (pin "3") (pinfunction "+IN_3") (pintype "input"))
      (node (ref "IC14") (pin "5") (pinfunction "+IN_5") (pintype "input"))
      (node (ref "R33") (pin "2") (pinfunction "2_2") (pintype "passive"))
      (node (ref "U1") (pin "Y12") (pinfunction "SYS_ADC_1P8V_Y12") (pintype "bidirectional"))
    )
    (net (code "281") (name "SYS_RTC_1P8V") (class "Default")
      (node (ref "Q1") (pin "C") (pinfunction "C_C") (pintype "passive"))
      (node (ref "R15") (pin "1") (pinfunction "1_1") (pintype "passive"))
      (node (ref "TP14") (pin "TP") (pinfunction "TP_TP") (pintype "input"))
      (node (ref "U1") (pin "K13") (pinfunction "SYS_RTC_1P8V_K13") (pintype "power_in"))
      (node (ref "U1") (pin "K14") (pinfunction "SYS_RTC_1P8V_K14") (pintype "power_in"))
      (node (ref "U1") (pin "L13") (pinfunction "SYS_RTC_1P8V_L13") (pintype "power_in"))
      (node (ref "U1") (pin "L14") (pinfunction "SYS_RTC_1P8V_L14") (pintype "power_in"))
      (node (ref "U1") (pin "M13") (pinfunction "VDDS_RTC_M13") (pintype "bidirectional"))
      (node (ref "U1") (pin "M14") (pinfunction "VDDS_M14") (pintype "bidirectional"))
      (node (ref "U5") (pin "3") (pinfunction "ANODE_3") (pintype "bidirectional"))
    )
    (net (code "282") (name "SYS_VDD1_3P3V") (class "Default")
      (node (ref "C104") (pin "1") (pinfunction "1_1") (pintype "passive"))
      (node (ref "C15") (pin "1") (pinfunction "1_1") (pintype "passive"))
      (node (ref "C21") (pin "1") (pinfunction "1_1") (pintype "passive"))
      (node (ref "C22") (pin "1") (pinfunction "1_1") (pintype "passive"))
      (node (ref "C301") (pin "1") (pinfunction "1_1") (pintype "passive"))
      (node (ref "C401") (pin "1") (pinfunction "1_1") (pintype "passive"))
      (node (ref "C404") (pin "1") (pinfunction "1_1") (pintype "passive"))
      (node (ref "C6") (pin "2") (pinfunction "2_2") (pintype "passive"))
      (node (ref "C79") (pin "1") (pinfunction "1_1") (pintype "passive"))
      (node (ref "C802") (pin "1") (pinfunction "1_1") (pintype "passive"))
      (node (ref "C85") (pin "1") (pinfunction "1_1") (pintype "passive"))
      (node (ref "C87") (pin "1") (pinfunction "1_1") (pintype "passive"))
      (node (ref "C88") (pin "1") (pinfunction "1_1") (pintype "passive"))
      (node (ref "C901") (pin "1") (pinfunction "1_1") (pintype "passive"))
      (node (ref "EC34") (pin "1") (pinfunction "1_1") (pintype "passive"))
      (node (ref "ER100") (pin "1") (pinfunction "1_1") (pintype "passive"))
      (node (ref "ER105") (pin "1") (pinfunction "1_1") (pintype "passive"))
      (node (ref "ER98") (pin "1") (pinfunction "1_1") (pintype "passive"))
      (node (ref "ER99") (pin "1") (pinfunction "1_1") (pintype "passive"))
      (node (ref "FB7") (pin "1") (pinfunction "1_1") (pintype "passive"))
      (node (ref "IC14") (pin "8") (pinfunction "V+_8") (pintype "power_in"))
      (node (ref "R12") (pin "2") (pinfunction "2_2") (pintype "passive"))
      (node (ref "R13") (pin "2") (pinfunction "2_2") (pintype "passive"))
      (node (ref "R163") (pin "2") (pinfunction "2_2") (pintype "passive"))
      (node (ref "R164") (pin "1") (pinfunction "1_1") (pintype "passive"))
      (node (ref "R169") (pin "2") (pinfunction "2_2") (pintype "passive"))
      (node (ref "R170") (pin "2") (pinfunction "2_2") (pintype "passive"))
      (node (ref "R22") (pin "2") (pinfunction "2_2") (pintype "passive"))
      (node (ref "R301") (pin "1") (pinfunction "1_1") (pintype "passive"))
      (node (ref "R302") (pin "1") (pinfunction "1_1") (pintype "passive"))
      (node (ref "R303") (pin "2") (pinfunction "2_2") (pintype "passive"))
      (node (ref "R40") (pin "2") (pinfunction "2_2") (pintype "passive"))
      (node (ref "R401") (pin "1") (pinfunction "1_1") (pintype "passive"))
      (node (ref "R402") (pin "1") (pinfunction "1_1") (pintype "passive"))
      (node (ref "R41") (pin "2") (pinfunction "2_2") (pintype "passive"))
      (node (ref "R70") (pin "2") (pinfunction "2_2") (pintype "passive"))
      (node (ref "R71") (pin "2") (pinfunction "2_2") (pintype "passive"))
      (node (ref "R72") (pin "2") (pinfunction "2_2") (pintype "passive"))
      (node (ref "R73") (pin "2") (pinfunction "2_2") (pintype "passive"))
      (node (ref "R74") (pin "2") (pinfunction "2_2") (pintype "passive"))
      (node (ref "R75") (pin "2") (pinfunction "2_2") (pintype "passive"))
      (node (ref "R76") (pin "2") (pinfunction "2_2") (pintype "passive"))
      (node (ref "R77") (pin "2") (pinfunction "2_2") (pintype "passive"))
      (node (ref "R78") (pin "2") (pinfunction "2_2") (pintype "passive"))
      (node (ref "R79") (pin "2") (pinfunction "2_2") (pintype "passive"))
      (node (ref "R80") (pin "2") (pinfunction "2_2") (pintype "passive"))
      (node (ref "R801") (pin "1") (pinfunction "1_1") (pintype "passive"))
      (node (ref "R802") (pin "1") (pinfunction "1_1") (pintype "passive"))
      (node (ref "R81") (pin "2") (pinfunction "2_2") (pintype "passive"))
      (node (ref "R82") (pin "2") (pinfunction "2_2") (pintype "passive"))
      (node (ref "R83") (pin "2") (pinfunction "2_2") (pintype "passive"))
      (node (ref "R84") (pin "2") (pinfunction "2_2") (pintype "passive"))
      (node (ref "R85") (pin "2") (pinfunction "2_2") (pintype "passive"))
      (node (ref "R86") (pin "2") (pinfunction "2_2") (pintype "passive"))
      (node (ref "R87") (pin "2") (pinfunction "2_2") (pintype "passive"))
      (node (ref "R88") (pin "2") (pinfunction "2_2") (pintype "passive"))
      (node (ref "R89") (pin "2") (pinfunction "2_2") (pintype "passive"))
      (node (ref "R90") (pin "2") (pinfunction "2_2") (pintype "passive"))
      (node (ref "R901") (pin "2") (pinfunction "2_2") (pintype "passive"))
      (node (ref "R902") (pin "2") (pinfunction "2_2") (pintype "passive"))
      (node (ref "R91") (pin "2") (pinfunction "2_2") (pintype "passive"))
      (node (ref "R92") (pin "2") (pinfunction "2_2") (pintype "passive"))
      (node (ref "RTC1") (pin "2") (pinfunction "VCC_2") (pintype "power_in"))
      (node (ref "S11") (pin "C") (pinfunction "C_C") (pintype "passive"))
      (node (ref "S12") (pin "C") (pinfunction "C_C") (pintype "passive"))
      (node (ref "S13") (pin "1") (pinfunction "1_1") (pintype "passive"))
      (node (ref "S13") (pin "2") (pinfunction "2_2") (pintype "passive"))
      (node (ref "S13") (pin "3") (pinfunction "3_3") (pintype "passive"))
      (node (ref "S13") (pin "4") (pinfunction "4_4") (pintype "passive"))
      (node (ref "T4") (pin "P$2") (pinfunction "2_P$2") (pintype "passive"))
      (node (ref "T4") (pin "P$3") (pinfunction "3_P$3") (pintype "passive"))
      (node (ref "TP12") (pin "TP") (pinfunction "TP_TP") (pintype "input"))
      (node (ref "U1") (pin "F8") (pinfunction "EMMC_VCC_F8") (pintype "bidirectional"))
      (node (ref "U1") (pin "F9") (pinfunction "EMMC_VCC_F9") (pintype "bidirectional"))
      (node (ref "U1") (pin "G8") (pinfunction "EMMC_VCC_G8") (pintype "bidirectional"))
      (node (ref "U1") (pin "G9") (pinfunction "EMMC_VCC_G9") (pintype "bidirectional"))
      (node (ref "U1") (pin "H14") (pinfunction "SYS_VDD1_3P3V_H14") (pintype "power_in"))
      (node (ref "U1") (pin "H15") (pinfunction "SYS_VDD1_3P3V_H15") (pintype "power_in"))
      (node (ref "U1") (pin "H7") (pinfunction "EMMC_VCCQ_H7") (pintype "bidirectional"))
      (node (ref "U1") (pin "H8") (pinfunction "EMMC_VCCQ_H8") (pintype "bidirectional"))
      (node (ref "U1") (pin "J14") (pinfunction "SYS_VDD1_3P3V_J14") (pintype "power_in"))
      (node (ref "U1") (pin "J15") (pinfunction "SYS_VDD1_3P3V_J15") (pintype "power_in"))
      (node (ref "U1") (pin "J7") (pinfunction "EMMC_VCCQ_J7") (pintype "bidirectional"))
      (node (ref "U1") (pin "J8") (pinfunction "EMMC_VCCQ_J8") (pintype "bidirectional"))
      (node (ref "U16") (pin "1") (pinfunction "VCC_1") (pintype "bidirectional"))
      (node (ref "U16") (pin "22") (pinfunction "VCC_22") (pintype "bidirectional"))
      (node (ref "U16") (pin "8") (pinfunction "VCC_8") (pintype "bidirectional"))
      (node (ref "U27") (pin "12") (pinfunction "VDDIO_12") (pintype "power_in"))
      (node (ref "U28") (pin "5") (pinfunction "VIO_5") (pintype "power_in"))
      (node (ref "U29") (pin "8") (pinfunction "VCC_8") (pintype "power_in"))
      (node (ref "U4") (pin "4") (pinfunction "VCC_4") (pintype "bidirectional"))
      (node (ref "U40") (pin "4") (pinfunction "VCC1_4") (pintype "power_in"))
      (node (ref "U6") (pin "7") (pinfunction "2OE_7") (pintype "input"))
      (node (ref "U6") (pin "8") (pinfunction "VCC_8") (pintype "power_in"))
      (node (ref "X4") (pin "5") (pinfunction "TVDD_5") (pintype "bidirectional"))
      (node (ref "X5") (pin "4") (pinfunction "VDD_4") (pintype "bidirectional"))
      (node (ref "X9") (pin "P$3") (pinfunction "3_P$3") (pintype "passive"))
    )
    (net (code "283") (name "SYS_VDD2_3P3V") (class "Default")
      (node (ref "D1") (pin "1") (pinfunction "A_1") (pintype "passive"))
      (node (ref "TP13") (pin "TP") (pinfunction "TP_TP") (pintype "input"))
      (node (ref "U1") (pin "F12") (pinfunction "SYS_VDD2_3P3V_F12") (pintype "power_in"))
      (node (ref "U1") (pin "F13") (pinfunction "SYS_VDD2_3P3V_F13") (pintype "power_in"))
      (node (ref "U1") (pin "G12") (pinfunction "SYS_VDD2_3P3V_G12") (pintype "power_in"))
      (node (ref "U1") (pin "G13") (pinfunction "SYS_VDD2_3P3V_G13") (pintype "power_in"))
    )
    (net (code "284") (name "SYS_VDD3_3P3V") (class "Default")
      (node (ref "Q1") (pin "E") (pinfunction "E_E") (pintype "passive"))
      (node (ref "R20") (pin "2") (pinfunction "2_2") (pintype "passive"))
      (node (ref "R21") (pin "2") (pinfunction "2_2") (pintype "passive"))
      (node (ref "TP16") (pin "TP") (pinfunction "TP_TP") (pintype "input"))
      (node (ref "U1") (pin "K10") (pinfunction "SYS_VDD3_3P3V_K10") (pintype "power_in"))
      (node (ref "U1") (pin "K11") (pinfunction "SYS_VDD3_3P3V_K11") (pintype "power_in"))
      (node (ref "U1") (pin "L10") (pinfunction "SYS_VDD3_3P3V_L10") (pintype "power_in"))
      (node (ref "U1") (pin "L11") (pinfunction "SYS_VDD3_3P3V_L11") (pintype "power_in"))
      (node (ref "U1") (pin "L12") (pinfunction "SYS_VDD3_3P3V_L12") (pintype "power_in"))
      (node (ref "U1") (pin "L7") (pinfunction "SYS_VDD3_3P3V_L7") (pintype "power_in"))
      (node (ref "U1") (pin "L8") (pinfunction "SYS_VDD3_3P3V_L8") (pintype "power_in"))
      (node (ref "U1") (pin "L9") (pinfunction "SYS_VDD3_3P3V_L9") (pintype "power_in"))
      (node (ref "U1") (pin "M10") (pinfunction "VDDSHV2_M10") (pintype "power_in"))
      (node (ref "U1") (pin "M11") (pinfunction "VDDSHV1_M11") (pintype "power_in"))
      (node (ref "U1") (pin "M12") (pinfunction "VDDSHV6_M12") (pintype "power_in"))
      (node (ref "U1") (pin "M7") (pinfunction "VDDSHV4_M7") (pintype "power_in"))
      (node (ref "U1") (pin "M8") (pinfunction "VDDSHV5_M8") (pintype "power_in"))
      (node (ref "U1") (pin "M9") (pinfunction "VDDSHV3_M9") (pintype "power_in"))
    )
    (net (code "285") (name "SYS_VDD_1P8V") (class "Default")
      (node (ref "TP15") (pin "TP") (pinfunction "TP_TP") (pintype "input"))
      (node (ref "U1") (pin "N10") (pinfunction "SYS_VDD_1P8V_N10") (pintype "power_in"))
      (node (ref "U1") (pin "N11") (pinfunction "SYS_VDD_1P8V_N11") (pintype "power_in"))
      (node (ref "U1") (pin "N12") (pinfunction "SYS_VDD_1P8V_N12") (pintype "power_in"))
      (node (ref "U1") (pin "N13") (pinfunction "SYS_VDD_1P8V_N13") (pintype "power_in"))
      (node (ref "U1") (pin "N14") (pinfunction "SYS_VDD_1P8V_N14") (pintype "power_in"))
      (node (ref "U1") (pin "N7") (pinfunction "SYS_VDD_1P8V_N7") (pintype "power_in"))
      (node (ref "U1") (pin "N8") (pinfunction "SYS_VDD_1P8V_N8") (pintype "power_in"))
      (node (ref "U1") (pin "N9") (pinfunction "SYS_VDD_1P8V_N9") (pintype "power_in"))
      (node (ref "U1") (pin "P10") (pinfunction "SYS_VDD_1P8V_P10") (pintype "power_in"))
      (node (ref "U1") (pin "P11") (pinfunction "SYS_VDD_1P8V_P11") (pintype "power_in"))
    )
    (net (code "286") (name "SYS_VOUT") (class "Default")
      (node (ref "C4") (pin "1") (pinfunction "1_1") (pintype "passive"))
      (node (ref "TP11") (pin "TP") (pinfunction "TP_TP") (pintype "input"))
      (node (ref "U1") (pin "F14") (pinfunction "SYS_VOUT_F14") (pintype "power_in"))
      (node (ref "U1") (pin "F15") (pinfunction "SYS_VOUT_F15") (pintype "power_in"))
      (node (ref "U1") (pin "G14") (pinfunction "SYS_VOUT_G14") (pintype "power_in"))
      (node (ref "U1") (pin "G15") (pinfunction "SYS_VOUT_G15") (pintype "power_in"))
    )
    (net (code "287") (name "VDD_5V") (class "Default")
      (node (ref "C102") (pin "1") (pinfunction "1_1") (pintype "passive"))
      (node (ref "C11") (pin "+") (pinfunction "+_+") (pintype "passive"))
      (node (ref "C801") (pin "1") (pinfunction "1_1") (pintype "passive"))
      (node (ref "C803") (pin "1") (pinfunction "1_1") (pintype "passive"))
      (node (ref "L2") (pin "2") (pinfunction "2_2") (pintype "passive"))
      (node (ref "U1") (pin "C18") (pinfunction "VIN_AC_C18") (pintype "power_in"))
      (node (ref "U1") (pin "C19") (pinfunction "VIN_AC_C19") (pintype "power_in"))
      (node (ref "U1") (pin "C20") (pinfunction "VIN_AC_C20") (pintype "power_in"))
      (node (ref "U28") (pin "3") (pinfunction "VCC_3") (pintype "power_in"))
      (node (ref "VREG1") (pin "4") (pinfunction "FB_4") (pintype "input"))
    )
    (net (code "288") (name "VDD_BAT") (class "Default")
      (node (ref "TP5") (pin "P$1") (pinfunction "TP_P$1") (pintype "bidirectional"))
      (node (ref "U1") (pin "D18") (pinfunction "VIN_BAT_D18") (pintype "power_in"))
      (node (ref "U1") (pin "D19") (pinfunction "VIN_BAT_D19") (pintype "power_in"))
      (node (ref "U1") (pin "D20") (pinfunction "VIN_BAT_D20") (pintype "power_in"))
    )
    (net (code "289") (name "VDD_ETH_PHY") (class "Default")
      (node (ref "EC30") (pin "1") (pinfunction "1_1") (pintype "passive"))
      (node (ref "EC31") (pin "1") (pinfunction "1_1") (pintype "passive"))
      (node (ref "EC32") (pin "1") (pinfunction "1_1") (pintype "passive"))
      (node (ref "ER106") (pin "1") (pinfunction "1_1") (pintype "passive"))
      (node (ref "ER107") (pin "1") (pinfunction "1_1") (pintype "passive"))
      (node (ref "ER108") (pin "1") (pinfunction "1_1") (pintype "passive"))
      (node (ref "ER109") (pin "1") (pinfunction "1_1") (pintype "passive"))
      (node (ref "ER122") (pin "1") (pinfunction "1_1") (pintype "passive"))
      (node (ref "FB7") (pin "2") (pinfunction "2_2") (pintype "passive"))
      (node (ref "U27") (pin "1") (pinfunction "VDD2A_1") (pintype "power_in"))
      (node (ref "U27") (pin "27") (pinfunction "VDD1A_27") (pintype "power_in"))
    )
    (net (code "290") (name "VDD_USB_5V") (class "Default")
      (node (ref "C3") (pin "1") (pinfunction "1_1") (pintype "passive"))
      (node (ref "R10") (pin "2") (pinfunction "2_2") (pintype "passive"))
      (node (ref "U1") (pin "B18") (pinfunction "VIN_USB_B18") (pintype "power_in"))
      (node (ref "U1") (pin "B19") (pinfunction "VIN_USB_B19") (pintype "power_in"))
      (node (ref "U1") (pin "B20") (pinfunction "VIN_USB_B20") (pintype "power_in"))
      (node (ref "U1") (pin "K1") (pinfunction "USB0_VBUS_K1") (pintype "bidirectional"))
      (node (ref "U2") (pin "6") (pinfunction "VBUS_6") (pintype "passive"))
    )
    (net (code "291") (name "unconnected-(F401-Pad2)") (class "Default")
      (node (ref "F401") (pin "2") (pinfunction "2_2") (pintype "passive"))
    )
    (net (code "292") (name "unconnected-(F402-Pad2)") (class "Default")
      (node (ref "F402") (pin "2") (pinfunction "2_2") (pintype "passive"))
    )
    (net (code "293") (name "unconnected-(FUD1-PadP$1)") (class "Default")
      (node (ref "FUD1") (pin "P$1") (pinfunction "P$1_P$1") (pintype "no_connect"))
    )
    (net (code "294") (name "unconnected-(FUD2-PadP$1)") (class "Default")
      (node (ref "FUD2") (pin "P$1") (pinfunction "P$1_P$1") (pintype "no_connect"))
    )
    (net (code "295") (name "unconnected-(FUD3-PadP$1)") (class "Default")
      (node (ref "FUD3") (pin "P$1") (pinfunction "P$1_P$1") (pintype "no_connect"))
    )
    (net (code "296") (name "unconnected-(FUD4-PadP$1)") (class "Default")
      (node (ref "FUD4") (pin "P$1") (pinfunction "P$1_P$1") (pintype "no_connect"))
    )
    (net (code "297") (name "unconnected-(FUD5-PadP$1)") (class "Default")
      (node (ref "FUD5") (pin "P$1") (pinfunction "P$1_P$1") (pintype "no_connect"))
    )
    (net (code "298") (name "unconnected-(FUD6-PadP$1)") (class "Default")
      (node (ref "FUD6") (pin "P$1") (pinfunction "P$1_P$1") (pintype "no_connect"))
    )
    (net (code "299") (name "unconnected-(G1-+-Pad+@1)") (class "Default")
      (node (ref "G1") (pin "+@1") (pinfunction "+_+@1") (pintype "passive"))
    )
    (net (code "300") (name "unconnected-(IC2-I7-Pad7)") (class "Default")
      (node (ref "IC2") (pin "7") (pinfunction "I7_7") (pintype "input"))
    )
    (net (code "301") (name "unconnected-(IC2-O7-Pad10)") (class "Default")
      (node (ref "IC2") (pin "10") (pinfunction "O7_10") (pintype "open_collector"))
    )
    (net (code "302") (name "unconnected-(IC4A-~{QH}-Pad7)") (class "Default")
      (node (ref "IC4") (pin "7") (pinfunction "~{QH}_7") (pintype "output"))
    )
    (net (code "303") (name "unconnected-(IC5A-~{QH}-Pad7)") (class "Default")
      (node (ref "IC5") (pin "7") (pinfunction "~{QH}_7") (pintype "output"))
    )
    (net (code "304") (name "unconnected-(RTC1-SQW-Pad3)") (class "Default")
      (node (ref "RTC1") (pin "3") (pinfunction "SQW_3") (pintype "output"))
    )
    (net (code "305") (name "unconnected-(U1A-VDDS_RTC-PadU14)") (class "Default")
      (node (ref "U1") (pin "U14") (pinfunction "VDDS_RTC_U14") (pintype "bidirectional"))
    )
    (net (code "306") (name "unconnected-(U1B-USB0_CE-PadL3)") (class "Default")
      (node (ref "U1") (pin "L3") (pinfunction "USB0_CE_L3") (pintype "bidirectional"))
    )
    (net (code "307") (name "unconnected-(U1B-USB1_CE-PadJ3)") (class "Default")
      (node (ref "U1") (pin "J3") (pinfunction "USB1_CE_J3") (pintype "bidirectional"))
    )
    (net (code "308") (name "unconnected-(U1B-USB1_DM-PadH2)") (class "Default")
      (node (ref "U1") (pin "H2") (pinfunction "USB1_DM_H2") (pintype "bidirectional"))
    )
    (net (code "309") (name "unconnected-(U1B-USB1_DP-PadJ2)") (class "Default")
      (node (ref "U1") (pin "J2") (pinfunction "USB1_DP_J2") (pintype "bidirectional"))
    )
    (net (code "310") (name "unconnected-(U1B-USB1_DRVVBUS-PadH3)") (class "Default")
      (node (ref "U1") (pin "H3") (pinfunction "USB1_DRVVBUS_H3") (pintype "bidirectional"))
    )
    (net (code "311") (name "unconnected-(U1B-USB1_ID-PadJ1)") (class "Default")
      (node (ref "U1") (pin "J1") (pinfunction "USB1_ID_J1") (pintype "bidirectional"))
    )
    (net (code "312") (name "unconnected-(U1B-USB1_VBUS-PadH1)") (class "Default")
      (node (ref "U1") (pin "H1") (pinfunction "USB1_VBUS_H1") (pintype "bidirectional"))
    )
    (net (code "313") (name "unconnected-(U1C-EMMC_RSTN-PadA4)") (class "Default")
      (node (ref "U1") (pin "A4") (pinfunction "EMMC_RSTN_A4") (pintype "bidirectional"))
    )
    (net (code "314") (name "unconnected-(U1C-GPMC_A4-PadB12)") (class "Default")
      (node (ref "U1") (pin "B12") (pinfunction "GPMC_A4_B12") (pintype "bidirectional"))
    )
    (net (code "315") (name "unconnected-(U1C-GPMC_A9-PadA10)") (class "Default")
      (node (ref "U1") (pin "A10") (pinfunction "GPMC_A9_A10") (pintype "bidirectional"))
    )
    (net (code "316") (name "unconnected-(U1C-GPMC_A10-PadB10)") (class "Default")
      (node (ref "U1") (pin "B10") (pinfunction "GPMC_A10_B10") (pintype "bidirectional"))
    )
    (net (code "317") (name "unconnected-(U1C-GPMC_A11-PadC10)") (class "Default")
      (node (ref "U1") (pin "C10") (pinfunction "GPMC_A11_C10") (pintype "bidirectional"))
    )
    (net (code "318") (name "unconnected-(U1C-GPMC_AD10-PadB16)") (class "Default")
      (node (ref "U1") (pin "B16") (pinfunction "GPMC_AD10_B16") (pintype "bidirectional"))
    )
    (net (code "319") (name "unconnected-(U1C-GPMC_AD11-PadA16)") (class "Default")
      (node (ref "U1") (pin "A16") (pinfunction "GPMC_AD11_A16") (pintype "bidirectional"))
    )
    (net (code "320") (name "unconnected-(U1C-GPMC_ADVN_ALE-PadL19)") (class "Default")
      (node (ref "U1") (pin "L19") (pinfunction "GPMC_ADVN_ALE_L19") (pintype "bidirectional"))
    )
    (net (code "321") (name "unconnected-(U1C-GPMC_BEN0_CLE-PadL20)") (class "Default")
      (node (ref "U1") (pin "L20") (pinfunction "GPMC_BEN0_CLE_L20") (pintype "bidirectional"))
    )
    (net (code "322") (name "unconnected-(U1C-GPMC_CLK-PadA14)") (class "Default")
      (node (ref "U1") (pin "A14") (pinfunction "GPMC_CLK_A14") (pintype "bidirectional"))
    )
    (net (code "323") (name "unconnected-(U1C-GPMC_CSN3-PadB14)") (class "Default")
      (node (ref "U1") (pin "B14") (pinfunction "GPMC_CSN3_B14") (pintype "bidirectional"))
    )
    (net (code "324") (name "unconnected-(U1C-GPMC_OEN_REN-PadK19)") (class "Default")
      (node (ref "U1") (pin "K19") (pinfunction "GPMC_OEN_REN_K19") (pintype "bidirectional"))
    )
    (net (code "325") (name "unconnected-(U1C-GPMC_WEN-PadK18)") (class "Default")
      (node (ref "U1") (pin "K18") (pinfunction "GPMC_WEN_K18") (pintype "bidirectional"))
    )
    (net (code "326") (name "unconnected-(U1C-MCASP0_ACLKR-PadY15)") (class "Default")
      (node (ref "U1") (pin "Y15") (pinfunction "MCASP0_ACLKR_Y15") (pintype "bidirectional"))
    )
    (net (code "327") (name "unconnected-(U1D-RMII1_REF_CLK-PadM3)") (class "Default")
      (node (ref "U1") (pin "M3") (pinfunction "RMII1_REF_CLK_M3") (pintype "bidirectional"))
    )
    (net (code "328") (name "unconnected-(U1F-CAP_VDD_RTC-PadV13)") (class "Default")
      (node (ref "U1") (pin "V13") (pinfunction "CAP_VDD_RTC_V13") (pintype "bidirectional"))
    )
    (net (code "329") (name "unconnected-(U1G-NC-PadA2)") (class "Default")
      (node (ref "U1") (pin "A2") (pinfunction "NC_A2") (pintype "bidirectional"))
    )
    (net (code "330") (name "unconnected-(U1G-NC-PadA3)") (class "Default")
      (node (ref "U1") (pin "A3") (pinfunction "NC_A3") (pintype "bidirectional"))
    )
    (net (code "331") (name "unconnected-(U1G-NC-PadA5)") (class "Default")
      (node (ref "U1") (pin "A5") (pinfunction "NC_A5") (pintype "bidirectional"))
    )
    (net (code "332") (name "unconnected-(U1G-NC-PadA6)") (class "Default")
      (node (ref "U1") (pin "A6") (pinfunction "NC_A6") (pintype "bidirectional"))
    )
    (net (code "333") (name "unconnected-(U1G-NC-PadA7)") (class "Default")
      (node (ref "U1") (pin "A7") (pinfunction "NC_A7") (pintype "bidirectional"))
    )
    (net (code "334") (name "unconnected-(U1G-NC-PadA8)") (class "Default")
      (node (ref "U1") (pin "A8") (pinfunction "NC_A8") (pintype "bidirectional"))
    )
    (net (code "335") (name "unconnected-(U1G-NC-PadB1)") (class "Default")
      (node (ref "U1") (pin "B1") (pinfunction "NC_B1") (pintype "bidirectional"))
    )
    (net (code "336") (name "unconnected-(U1G-NC-PadB2)") (class "Default")
      (node (ref "U1") (pin "B2") (pinfunction "NC_B2") (pintype "bidirectional"))
    )
    (net (code "337") (name "unconnected-(U1G-NC-PadB3)") (class "Default")
      (node (ref "U1") (pin "B3") (pinfunction "NC_B3") (pintype "bidirectional"))
    )
    (net (code "338") (name "unconnected-(U1G-NC-PadB4)") (class "Default")
      (node (ref "U1") (pin "B4") (pinfunction "NC_B4") (pintype "bidirectional"))
    )
    (net (code "339") (name "unconnected-(U1G-NC-PadB5)") (class "Default")
      (node (ref "U1") (pin "B5") (pinfunction "NC_B5") (pintype "bidirectional"))
    )
    (net (code "340") (name "unconnected-(U1G-NC-PadB6)") (class "Default")
      (node (ref "U1") (pin "B6") (pinfunction "NC_B6") (pintype "bidirectional"))
    )
    (net (code "341") (name "unconnected-(U1G-NC-PadB7)") (class "Default")
      (node (ref "U1") (pin "B7") (pinfunction "NC_B7") (pintype "bidirectional"))
    )
    (net (code "342") (name "unconnected-(U1G-NC-PadB8)") (class "Default")
      (node (ref "U1") (pin "B8") (pinfunction "NC_B8") (pintype "bidirectional"))
    )
    (net (code "343") (name "unconnected-(U1G-NC-PadC1)") (class "Default")
      (node (ref "U1") (pin "C1") (pinfunction "NC_C1") (pintype "bidirectional"))
    )
    (net (code "344") (name "unconnected-(U1G-NC-PadC2)") (class "Default")
      (node (ref "U1") (pin "C2") (pinfunction "NC_C2") (pintype "bidirectional"))
    )
    (net (code "345") (name "unconnected-(U1G-NC-PadC3)") (class "Default")
      (node (ref "U1") (pin "C3") (pinfunction "NC_C3") (pintype "bidirectional"))
    )
    (net (code "346") (name "unconnected-(U1G-NC-PadC4)") (class "Default")
      (node (ref "U1") (pin "C4") (pinfunction "NC_C4") (pintype "bidirectional"))
    )
    (net (code "347") (name "unconnected-(U1G-NC-PadC5)") (class "Default")
      (node (ref "U1") (pin "C5") (pinfunction "NC_C5") (pintype "bidirectional"))
    )
    (net (code "348") (name "unconnected-(U1G-NC-PadC6)") (class "Default")
      (node (ref "U1") (pin "C6") (pinfunction "NC_C6") (pintype "bidirectional"))
    )
    (net (code "349") (name "unconnected-(U1G-NC-PadC7)") (class "Default")
      (node (ref "U1") (pin "C7") (pinfunction "NC_C7") (pintype "bidirectional"))
    )
    (net (code "350") (name "unconnected-(U1G-NC-PadC8)") (class "Default")
      (node (ref "U1") (pin "C8") (pinfunction "NC_C8") (pintype "bidirectional"))
    )
    (net (code "351") (name "unconnected-(U1G-NC-PadD1)") (class "Default")
      (node (ref "U1") (pin "D1") (pinfunction "NC_D1") (pintype "bidirectional"))
    )
    (net (code "352") (name "unconnected-(U1G-NC-PadD2)") (class "Default")
      (node (ref "U1") (pin "D2") (pinfunction "NC_D2") (pintype "bidirectional"))
    )
    (net (code "353") (name "unconnected-(U1G-NC-PadD3)") (class "Default")
      (node (ref "U1") (pin "D3") (pinfunction "NC_D3") (pintype "bidirectional"))
    )
    (net (code "354") (name "unconnected-(U1G-NC-PadD6)") (class "Default")
      (node (ref "U1") (pin "D6") (pinfunction "NC_D6") (pintype "bidirectional"))
    )
    (net (code "355") (name "unconnected-(U1G-NC-PadD7)") (class "Default")
      (node (ref "U1") (pin "D7") (pinfunction "NC_D7") (pintype "bidirectional"))
    )
    (net (code "356") (name "unconnected-(U1G-NC-PadD8)") (class "Default")
      (node (ref "U1") (pin "D8") (pinfunction "NC_D8") (pintype "bidirectional"))
    )
    (net (code "357") (name "unconnected-(U1G-NC-PadE1)") (class "Default")
      (node (ref "U1") (pin "E1") (pinfunction "NC_E1") (pintype "bidirectional"))
    )
    (net (code "358") (name "unconnected-(U1G-NC-PadE2)") (class "Default")
      (node (ref "U1") (pin "E2") (pinfunction "NC_E2") (pintype "bidirectional"))
    )
    (net (code "359") (name "unconnected-(U1G-NC-PadE3)") (class "Default")
      (node (ref "U1") (pin "E3") (pinfunction "NC_E3") (pintype "bidirectional"))
    )
    (net (code "360") (name "unconnected-(U1G-NC-PadE18)") (class "Default")
      (node (ref "U1") (pin "E18") (pinfunction "NC_E18") (pintype "bidirectional"))
    )
    (net (code "361") (name "unconnected-(U1G-NC-PadF1)") (class "Default")
      (node (ref "U1") (pin "F1") (pinfunction "NC_F1") (pintype "bidirectional"))
    )
    (net (code "362") (name "unconnected-(U1G-NC-PadF2)") (class "Default")
      (node (ref "U1") (pin "F2") (pinfunction "NC_F2") (pintype "bidirectional"))
    )
    (net (code "363") (name "unconnected-(U1G-NC-PadF3)") (class "Default")
      (node (ref "U1") (pin "F3") (pinfunction "NC_F3") (pintype "bidirectional"))
    )
    (net (code "364") (name "unconnected-(U1G-NC-PadF4)") (class "Default")
      (node (ref "U1") (pin "F4") (pinfunction "NC_F4") (pintype "bidirectional"))
    )
    (net (code "365") (name "unconnected-(U1G-NC-PadF6)") (class "Default")
      (node (ref "U1") (pin "F6") (pinfunction "NC_F6") (pintype "bidirectional"))
    )
    (net (code "366") (name "unconnected-(U1G-NC-PadF7)") (class "Default")
      (node (ref "U1") (pin "F7") (pinfunction "NC_F7") (pintype "bidirectional"))
    )
    (net (code "367") (name "unconnected-(U1G-NC-PadF20)") (class "Default")
      (node (ref "U1") (pin "F20") (pinfunction "NC_F20") (pintype "bidirectional"))
    )
    (net (code "368") (name "unconnected-(U1G-NC-PadG1)") (class "Default")
      (node (ref "U1") (pin "G1") (pinfunction "NC_G1") (pintype "bidirectional"))
    )
    (net (code "369") (name "unconnected-(U1G-NC-PadG2)") (class "Default")
      (node (ref "U1") (pin "G2") (pinfunction "NC_G2") (pintype "bidirectional"))
    )
    (net (code "370") (name "unconnected-(U1G-NC-PadG3)") (class "Default")
      (node (ref "U1") (pin "G3") (pinfunction "NC_G3") (pintype "bidirectional"))
    )
    (net (code "371") (name "unconnected-(U1G-NC-PadG4)") (class "Default")
      (node (ref "U1") (pin "G4") (pinfunction "NC_G4") (pintype "bidirectional"))
    )
    (net (code "372") (name "unconnected-(U1G-NC-PadG6)") (class "Default")
      (node (ref "U1") (pin "G6") (pinfunction "NC_G6") (pintype "bidirectional"))
    )
    (net (code "373") (name "unconnected-(U1G-NC-PadG7)") (class "Default")
      (node (ref "U1") (pin "G7") (pinfunction "NC_G7") (pintype "bidirectional"))
    )
    (net (code "374") (name "unconnected-(U1G-NC-PadG10)") (class "Default")
      (node (ref "U1") (pin "G10") (pinfunction "NC_G10") (pintype "bidirectional"))
    )
    (net (code "375") (name "unconnected-(U1G-NC-PadG11)") (class "Default")
      (node (ref "U1") (pin "G11") (pinfunction "NC_G11") (pintype "bidirectional"))
    )
    (net (code "376") (name "unconnected-(U1G-NC-PadG18)") (class "Default")
      (node (ref "U1") (pin "G18") (pinfunction "NC_G18") (pintype "bidirectional"))
    )
    (net (code "377") (name "unconnected-(U1G-NC-PadG19)") (class "Default")
      (node (ref "U1") (pin "G19") (pinfunction "NC_G19") (pintype "bidirectional"))
    )
    (net (code "378") (name "unconnected-(U1G-NC-PadG20)") (class "Default")
      (node (ref "U1") (pin "G20") (pinfunction "NC_G20") (pintype "bidirectional"))
    )
    (net (code "379") (name "unconnected-(U1G-NC-PadH4)") (class "Default")
      (node (ref "U1") (pin "H4") (pinfunction "NC_H4") (pintype "bidirectional"))
    )
    (net (code "380") (name "unconnected-(U1G-NC-PadH6)") (class "Default")
      (node (ref "U1") (pin "H6") (pinfunction "NC_H6") (pintype "bidirectional"))
    )
    (net (code "381") (name "unconnected-(U1G-NC-PadH9)") (class "Default")
      (node (ref "U1") (pin "H9") (pinfunction "NC_H9") (pintype "bidirectional"))
    )
    (net (code "382") (name "unconnected-(U1G-NC-PadH10)") (class "Default")
      (node (ref "U1") (pin "H10") (pinfunction "NC_H10") (pintype "bidirectional"))
    )
    (net (code "383") (name "unconnected-(U1G-NC-PadH11)") (class "Default")
      (node (ref "U1") (pin "H11") (pinfunction "NC_H11") (pintype "bidirectional"))
    )
    (net (code "384") (name "unconnected-(U1G-NC-PadH12)") (class "Default")
      (node (ref "U1") (pin "H12") (pinfunction "NC_H12") (pintype "bidirectional"))
    )
    (net (code "385") (name "unconnected-(U1G-NC-PadH13)") (class "Default")
      (node (ref "U1") (pin "H13") (pinfunction "NC_H13") (pintype "bidirectional"))
    )
    (net (code "386") (name "unconnected-(U1G-NC-PadH18)") (class "Default")
      (node (ref "U1") (pin "H18") (pinfunction "NC_H18") (pintype "bidirectional"))
    )
    (net (code "387") (name "unconnected-(U1G-NC-PadH19)") (class "Default")
      (node (ref "U1") (pin "H19") (pinfunction "NC_H19") (pintype "bidirectional"))
    )
    (net (code "388") (name "unconnected-(U1G-NC-PadH20)") (class "Default")
      (node (ref "U1") (pin "H20") (pinfunction "NC_H20") (pintype "bidirectional"))
    )
    (net (code "389") (name "unconnected-(U1G-NC-PadJ4)") (class "Default")
      (node (ref "U1") (pin "J4") (pinfunction "NC_J4") (pintype "bidirectional"))
    )
    (net (code "390") (name "unconnected-(U1G-NC-PadJ6)") (class "Default")
      (node (ref "U1") (pin "J6") (pinfunction "NC_J6") (pintype "bidirectional"))
    )
    (net (code "391") (name "unconnected-(U1G-NC-PadJ18)") (class "Default")
      (node (ref "U1") (pin "J18") (pinfunction "NC_J18") (pintype "bidirectional"))
    )
    (net (code "392") (name "unconnected-(U1G-NC-PadJ19)") (class "Default")
      (node (ref "U1") (pin "J19") (pinfunction "NC_J19") (pintype "bidirectional"))
    )
    (net (code "393") (name "unconnected-(U1G-NC-PadJ20)") (class "Default")
      (node (ref "U1") (pin "J20") (pinfunction "NC_J20") (pintype "bidirectional"))
    )
    (net (code "394") (name "unconnected-(U1G-NC-PadK4)") (class "Default")
      (node (ref "U1") (pin "K4") (pinfunction "NC_K4") (pintype "bidirectional"))
    )
    (net (code "395") (name "unconnected-(U1G-NC-PadL4)") (class "Default")
      (node (ref "U1") (pin "L4") (pinfunction "NC_L4") (pintype "bidirectional"))
    )
    (net (code "396") (name "unconnected-(U1G-NC-PadL17)") (class "Default")
      (node (ref "U1") (pin "L17") (pinfunction "NC_L17") (pintype "bidirectional"))
    )
    (net (code "397") (name "unconnected-(U1G-NC-PadM4)") (class "Default")
      (node (ref "U1") (pin "M4") (pinfunction "NC_M4") (pintype "bidirectional"))
    )
    (net (code "398") (name "unconnected-(U1G-NC-PadM6)") (class "Default")
      (node (ref "U1") (pin "M6") (pinfunction "NC_M6") (pintype "bidirectional"))
    )
    (net (code "399") (name "unconnected-(U1G-NC-PadM17)") (class "Default")
      (node (ref "U1") (pin "M17") (pinfunction "NC_M17") (pintype "bidirectional"))
    )
    (net (code "400") (name "unconnected-(U1G-NC-PadN4)") (class "Default")
      (node (ref "U1") (pin "N4") (pinfunction "NC_N4") (pintype "bidirectional"))
    )
    (net (code "401") (name "unconnected-(U1G-NC-PadN17)") (class "Default")
      (node (ref "U1") (pin "N17") (pinfunction "NC_N17") (pintype "bidirectional"))
    )
    (net (code "402") (name "unconnected-(U1G-NC-PadP4)") (class "Default")
      (node (ref "U1") (pin "P4") (pinfunction "NC_P4") (pintype "bidirectional"))
    )
    (net (code "403") (name "unconnected-(U1G-NC-PadP17)") (class "Default")
      (node (ref "U1") (pin "P17") (pinfunction "NC_P17") (pintype "bidirectional"))
    )
    (net (code "404") (name "unconnected-(U1G-NC-PadR4)") (class "Default")
      (node (ref "U1") (pin "R4") (pinfunction "NC_R4") (pintype "bidirectional"))
    )
    (net (code "405") (name "unconnected-(U1G-NC-PadR6)") (class "Default")
      (node (ref "U1") (pin "R6") (pinfunction "NC_R6") (pintype "bidirectional"))
    )
    (net (code "406") (name "unconnected-(U1G-NC-PadR7)") (class "Default")
      (node (ref "U1") (pin "R7") (pinfunction "NC_R7") (pintype "bidirectional"))
    )
    (net (code "407") (name "unconnected-(U1G-NC-PadR8)") (class "Default")
      (node (ref "U1") (pin "R8") (pinfunction "NC_R8") (pintype "bidirectional"))
    )
    (net (code "408") (name "unconnected-(U1G-NC-PadR13)") (class "Default")
      (node (ref "U1") (pin "R13") (pinfunction "NC_R13") (pintype "bidirectional"))
    )
    (net (code "409") (name "unconnected-(U1G-NC-PadR14)") (class "Default")
      (node (ref "U1") (pin "R14") (pinfunction "NC_R14") (pintype "bidirectional"))
    )
    (net (code "410") (name "unconnected-(U1G-NC-PadR15)") (class "Default")
      (node (ref "U1") (pin "R15") (pinfunction "NC_R15") (pintype "bidirectional"))
    )
    (net (code "411") (name "unconnected-(U1G-NC-PadR17)") (class "Default")
      (node (ref "U1") (pin "R17") (pinfunction "NC_R17") (pintype "bidirectional"))
    )
    (net (code "412") (name "unconnected-(U1G-NC-PadU11)") (class "Default")
      (node (ref "U1") (pin "U11") (pinfunction "NC_U11") (pintype "bidirectional"))
    )
    (net (code "413") (name "unconnected-(U2-N.C.-Pad5)") (class "Default")
      (node (ref "U2") (pin "5") (pinfunction "N.C._5") (pintype "no_connect"))
    )
    (net (code "414") (name "unconnected-(U16-NC-Pad7)") (class "Default")
      (node (ref "U16") (pin "7") (pinfunction "NC_7") (pintype "bidirectional"))
    )
    (net (code "415") (name "unconnected-(U16-NC-Pad10)") (class "Default")
      (node (ref "U16") (pin "10") (pinfunction "NC_10") (pintype "bidirectional"))
    )
    (net (code "416") (name "unconnected-(U16-NC-Pad11)") (class "Default")
      (node (ref "U16") (pin "11") (pinfunction "NC_11") (pintype "bidirectional"))
    )
    (net (code "417") (name "unconnected-(U16-NC-Pad13)") (class "Default")
      (node (ref "U16") (pin "13") (pinfunction "NC_13") (pintype "bidirectional"))
    )
    (net (code "418") (name "unconnected-(U16-NC-Pad14)") (class "Default")
      (node (ref "U16") (pin "14") (pinfunction "NC_14") (pintype "bidirectional"))
    )
    (net (code "419") (name "unconnected-(U16-NC-Pad15)") (class "Default")
      (node (ref "U16") (pin "15") (pinfunction "NC_15") (pintype "bidirectional"))
    )
    (net (code "420") (name "unconnected-(U16-NC-Pad16)") (class "Default")
      (node (ref "U16") (pin "16") (pinfunction "NC_16") (pintype "bidirectional"))
    )
    (net (code "421") (name "unconnected-(U16-NC-Pad25)") (class "Default")
      (node (ref "U16") (pin "25") (pinfunction "NC_25") (pintype "bidirectional"))
    )
    (net (code "422") (name "unconnected-(U16-NC-Pad26)") (class "Default")
      (node (ref "U16") (pin "26") (pinfunction "NC_26") (pintype "bidirectional"))
    )
    (net (code "423") (name "unconnected-(U16-NC-Pad27)") (class "Default")
      (node (ref "U16") (pin "27") (pinfunction "NC_27") (pintype "bidirectional"))
    )
    (net (code "424") (name "unconnected-(U16-NC-Pad28)") (class "Default")
      (node (ref "U16") (pin "28") (pinfunction "NC_28") (pintype "bidirectional"))
    )
    (net (code "425") (name "unconnected-(U16-NC-Pad31)") (class "Default")
      (node (ref "U16") (pin "31") (pinfunction "NC_31") (pintype "bidirectional"))
    )
    (net (code "426") (name "unconnected-(U16-PAD-Pad33)") (class "Default")
      (node (ref "U16") (pin "33") (pinfunction "PAD_33") (pintype "bidirectional"))
    )
    (net (code "427") (name "unconnected-(U28-S-Pad8)") (class "Default")
      (node (ref "U28") (pin "8") (pinfunction "S_8") (pintype "input"))
    )
    (net (code "428") (name "unconnected-(U40-NC-Pad10)") (class "Default")
      (node (ref "U40") (pin "10") (pinfunction "NC_10") (pintype "passive"))
    )
    (net (code "429") (name "unconnected-(VREG4-BYPASS-Pad4)") (class "Default")
      (node (ref "VREG4") (pin "4") (pinfunction "BYPASS_4") (pintype "passive"))
    )
    (net (code "430") (name "unconnected-(X2-NC-Pad7)") (class "Default")
      (node (ref "X2") (pin "7") (pinfunction "NC_7") (pintype "passive"))
    )
    (net (code "431") (name "unconnected-(X4-NC-Pad6)") (class "Default")
      (node (ref "X4") (pin "6") (pinfunction "NC_6") (pintype "bidirectional"))
    )
    (net (code "432") (name "unconnected-(X6-Pad2)") (class "Default")
      (node (ref "X6") (pin "2") (pinfunction "2_2") (pintype "bidirectional"))
    )
    (net (code "433") (name "unconnected-(X6-Pad3)") (class "Default")
      (node (ref "X6") (pin "3") (pinfunction "3_3") (pintype "bidirectional"))
    )
    (net (code "434") (name "unconnected-(X6-Pad6)") (class "Default")
      (node (ref "X6") (pin "6") (pinfunction "6_6") (pintype "bidirectional"))
    )
    (net (code "435") (name "unconnected-(X8-Pad17)") (class "Default")
      (node (ref "X8") (pin "17") (pinfunction "17_17") (pintype "bidirectional"))
    )
    (net (code "436") (name "unconnected-(X8-Pad20)") (class "Default")
      (node (ref "X8") (pin "20") (pinfunction "20_20") (pintype "bidirectional"))
    )
    (net (code "437") (name "unconnected-(X9-5-PadP$5)") (class "Default")
      (node (ref "X9") (pin "P$5") (pinfunction "5_P$5") (pintype "no_connect"))
    )
    (net (code "438") (name "unconnected-(X9-6-PadP$6)") (class "Default")
      (node (ref "X9") (pin "P$6") (pinfunction "6_P$6") (pintype "no_connect"))
    )
  )
)
